# SCH_Full_BMS_2022-05-24.net
KiCad netlist of a schematic drawn in EasyEDA
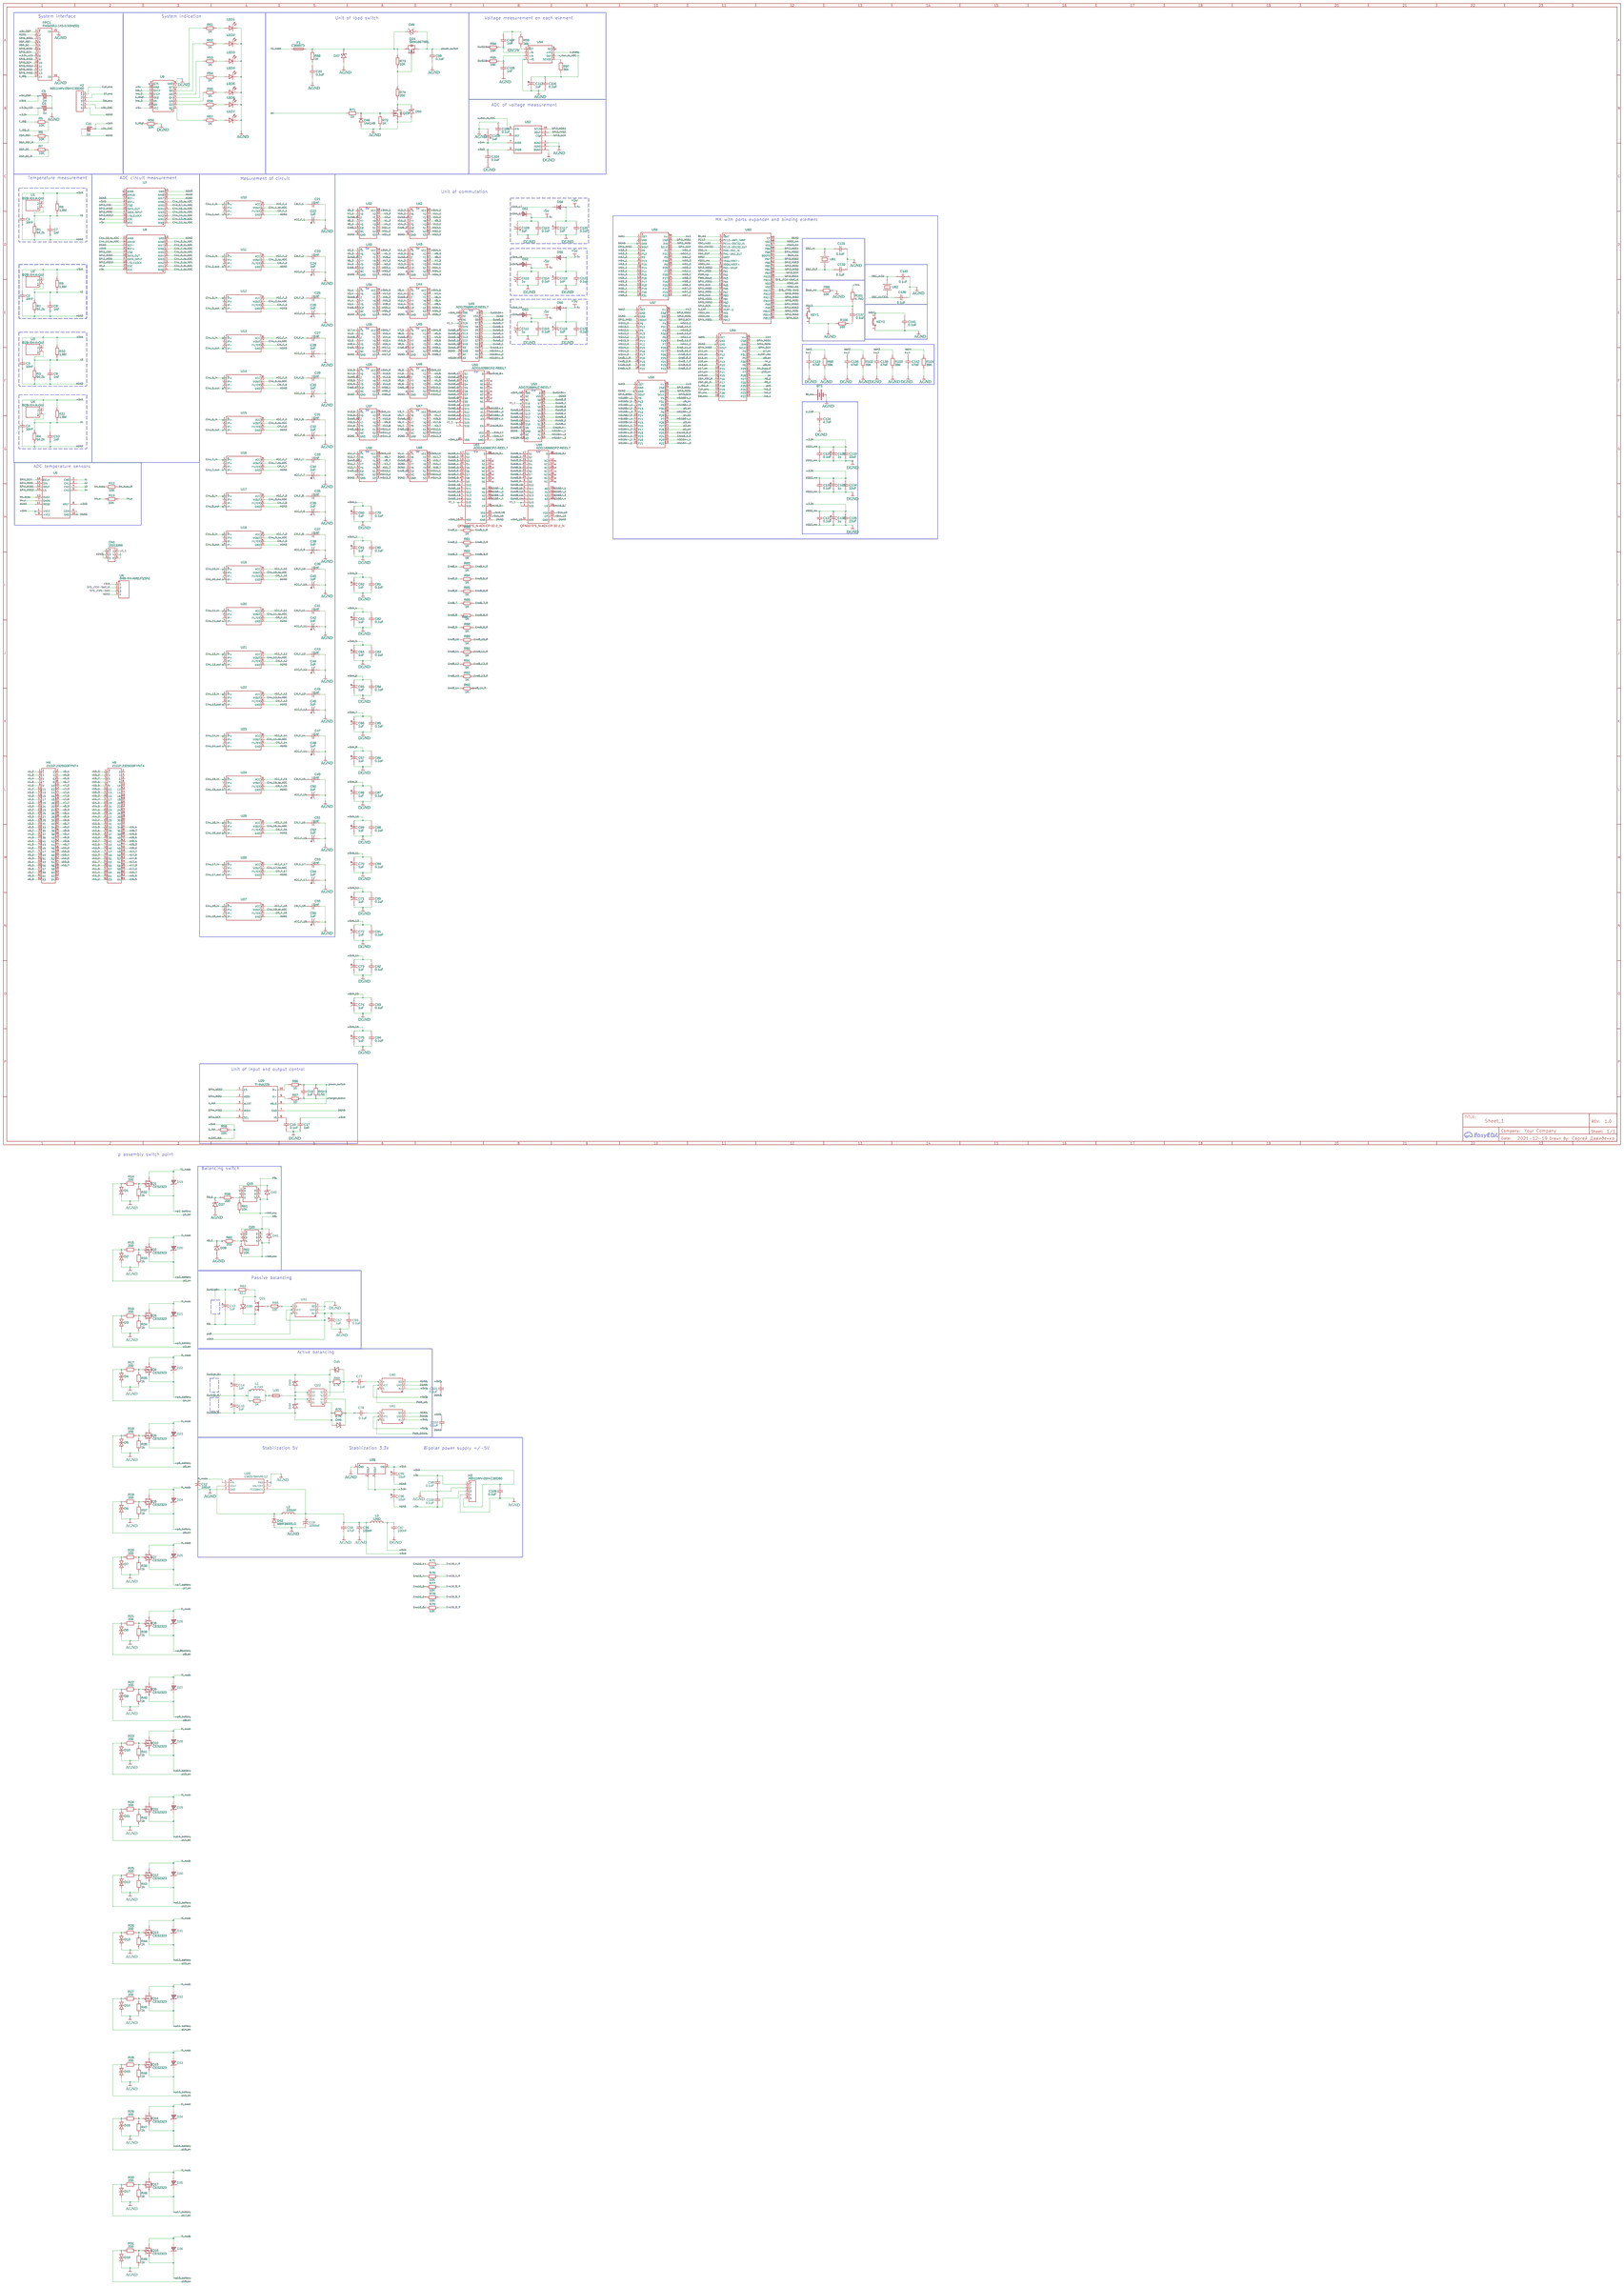
[diagram p0: schematic sheet]

(export (version "E")
  (design (tool "Eeschema 10.0.6"))
  (components
    (comp (ref "BT1")
      (value "1025")
      (fields (field (name "BOM_Supplier Part") "C238060"))
      (libsource (lib "") (part "1025"))
    )
    (comp (ref "C1")
      (value "10nF")
      (fields
        (field (name "BOM_Manufacturer Part") "GRM033R71A103KA01D")
        (field (name "BOM_Supplier Part") "C76941")
      )
      (libsource (lib "") (part "GRM033R71A103KA01D"))
    )
    (comp (ref "C2")
      (value "10nF")
      (fields
        (field (name "BOM_Manufacturer Part") "GRM033R71A103KA01D")
        (field (name "BOM_Supplier Part") "C76941")
      )
      (libsource (lib "") (part "GRM033R71A103KA01D"))
    )
    (comp (ref "C3")
      (value "10nF")
      (fields
        (field (name "BOM_Manufacturer Part") "GRM033R71A103KA01D")
        (field (name "BOM_Supplier Part") "C76941")
      )
      (libsource (lib "") (part "GRM033R71A103KA01D"))
    )
    (comp (ref "C4")
      (value "10nF")
      (fields
        (field (name "BOM_Manufacturer Part") "GRM033R71A103KA01D")
        (field (name "BOM_Supplier Part") "C76941")
      )
      (libsource (lib "") (part "GRM033R71A103KA01D"))
    )
    (comp (ref "C5") (value "1u") (libsource (lib "") (part "C_Tan_SMD_A_EU_1")))
    (comp (ref "C6") (value "1u") (libsource (lib "") (part "C_Tan_SMD_A_EU_2")))
    (comp (ref "C7")
      (value "1nF")
      (fields
        (field (name "BOM_Manufacturer Part") "GRM033R71A103KA01D")
        (field (name "BOM_Supplier Part") "C76941")
      )
      (libsource (lib "") (part "GRM033R71A103KA01D"))
    )
    (comp (ref "C8")
      (value "1nF")
      (fields
        (field (name "BOM_Manufacturer Part") "GRM033R71A103KA01D")
        (field (name "BOM_Supplier Part") "C76941")
      )
      (libsource (lib "") (part "GRM033R71A103KA01D"))
    )
    (comp (ref "C9")
      (value "1nF")
      (fields
        (field (name "BOM_Manufacturer Part") "GRM033R71A103KA01D")
        (field (name "BOM_Supplier Part") "C76941")
      )
      (libsource (lib "") (part "GRM033R71A103KA01D"))
    )
    (comp (ref "C10")
      (value "1nF")
      (fields
        (field (name "BOM_Manufacturer Part") "GRM033R71A103KA01D")
        (field (name "BOM_Supplier Part") "C76941")
      )
      (libsource (lib "") (part "GRM033R71A103KA01D"))
    )
    (comp (ref "C11") (value "1u") (libsource (lib "") (part "C_Tan_SMD_A_EU")))
    (comp (ref "C12")
      (value "100uF")
      (fields
        (field (name "BOM_Manufacturer Part") "HV101M035E077R")
        (field (name "BOM_Supplier Part") "C59934")
      )
      (libsource (lib "") (part "HV101M035E077R"))
    )
    (comp (ref "C13")
      (value "1uF")
      (fields
        (field (name "BOM_Manufacturer Part") "VE-010M1C0405-TRO")
        (field (name "BOM_Supplier Part") "C249445")
      )
      (libsource (lib "") (part "VE-010M1C0405-TRO_4"))
    )
    (comp (ref "C14")
      (value "1uF")
      (fields
        (field (name "BOM_Manufacturer Part") "VE-010M1C0405-TRO")
        (field (name "BOM_Supplier Part") "C249445")
      )
      (libsource (lib "") (part "VE-010M1C0405-TRO_4"))
    )
    (comp (ref "C15")
      (value "1uF")
      (fields
        (field (name "BOM_Manufacturer Part") "VE-010M1C0405-TRO")
        (field (name "BOM_Supplier Part") "C249445")
      )
      (libsource (lib "") (part "VE-010M1C0405-TRO_4"))
    )
    (comp (ref "C16")
      (value "0.1uF")
      (fields
        (field (name "BOM_Manufacturer Part") "0402BB104K160NGT")
        (field (name "BOM_Supplier Part") "C2173076")
      )
      (libsource (lib "") (part "0402BB104K160NGT_1"))
    )
    (comp (ref "C17")
      (value "1uF")
      (fields
        (field (name "BOM_Manufacturer Part") "CL10F105ZP8NNNC")
        (field (name "BOM_Supplier Part") "C84710")
      )
      (libsource (lib "") (part "CL10F105ZP8NNNC"))
    )
    (comp (ref "C18")
      (value "1uF")
      (fields
        (field (name "BOM_Manufacturer Part") "CL10F105ZP8NNNC")
        (field (name "BOM_Supplier Part") "C84710")
      )
      (libsource (lib "") (part "CL10F105ZP8NNNC"))
    )
    (comp (ref "C19")
      (value "1000uF")
      (fields
        (field (name "BOM_Manufacturer Part") "RVT1C102M1010")
        (field (name "BOM_Supplier Part") "C72470")
      )
      (libsource (lib "") (part "RVT1C102M1010"))
    )
    (comp (ref "C20")
      (value "0.1uF")
      (fields
        (field (name "BOM_Manufacturer Part") "0603BB104K500NGT")
        (field (name "BOM_Supplier Part") "C2168571")
      )
      (libsource (lib "") (part "0603BB104K500NGT"))
    )
    (comp (ref "C21")
      (value "1nF")
      (fields
        (field (name "BOM_Manufacturer Part") "0201B102J500CT")
        (field (name "BOM_Supplier Part") "C458605")
      )
      (libsource (lib "") (part "0201B102J500CT"))
    )
    (comp (ref "C22")
      (value "1uF")
      (fields
        (field (name "BOM_Manufacturer Part") "CA45-A-16V-1uF-K")
        (field (name "BOM_Supplier Part") "C140386")
      )
      (libsource (lib "") (part "CA45-A-16V-1UF-K"))
    )
    (comp (ref "C23")
      (value "1nF")
      (fields
        (field (name "BOM_Manufacturer Part") "0201B102J500CT")
        (field (name "BOM_Supplier Part") "C458605")
      )
      (libsource (lib "") (part "0201B102J500CT"))
    )
    (comp (ref "C24")
      (value "1uF")
      (fields
        (field (name "BOM_Manufacturer Part") "CA45-A-16V-1uF-K")
        (field (name "BOM_Supplier Part") "C140386")
      )
      (libsource (lib "") (part "CA45-A-16V-1UF-K_1"))
    )
    (comp (ref "C25")
      (value "1nF")
      (fields
        (field (name "BOM_Manufacturer Part") "0201B102J500CT")
        (field (name "BOM_Supplier Part") "C458605")
      )
      (libsource (lib "") (part "0201B102J500CT"))
    )
    (comp (ref "C26")
      (value "1uF")
      (fields
        (field (name "BOM_Manufacturer Part") "CA45-A-16V-1uF-K")
        (field (name "BOM_Supplier Part") "C140386")
      )
      (libsource (lib "") (part "CA45-A-16V-1UF-K"))
    )
    (comp (ref "C27")
      (value "1nF")
      (fields
        (field (name "BOM_Manufacturer Part") "0201B102J500CT")
        (field (name "BOM_Supplier Part") "C458605")
      )
      (libsource (lib "") (part "0201B102J500CT"))
    )
    (comp (ref "C28")
      (value "1uF")
      (fields
        (field (name "BOM_Manufacturer Part") "CA45-A-16V-1uF-K")
        (field (name "BOM_Supplier Part") "C140386")
      )
      (libsource (lib "") (part "CA45-A-16V-1UF-K"))
    )
    (comp (ref "C29")
      (value "1nF")
      (fields
        (field (name "BOM_Manufacturer Part") "0201B102J500CT")
        (field (name "BOM_Supplier Part") "C458605")
      )
      (libsource (lib "") (part "0201B102J500CT"))
    )
    (comp (ref "C30")
      (value "1uF")
      (fields
        (field (name "BOM_Manufacturer Part") "CA45-A-16V-1uF-K")
        (field (name "BOM_Supplier Part") "C140386")
      )
      (libsource (lib "") (part "CA45-A-16V-1UF-K_1"))
    )
    (comp (ref "C31")
      (value "1nF")
      (fields
        (field (name "BOM_Manufacturer Part") "0201B102J500CT")
        (field (name "BOM_Supplier Part") "C458605")
      )
      (libsource (lib "") (part "0201B102J500CT"))
    )
    (comp (ref "C32")
      (value "1uF")
      (fields
        (field (name "BOM_Manufacturer Part") "CA45-A-16V-1uF-K")
        (field (name "BOM_Supplier Part") "C140386")
      )
      (libsource (lib "") (part "CA45-A-16V-1UF-K_1"))
    )
    (comp (ref "C33")
      (value "1nF")
      (fields
        (field (name "BOM_Manufacturer Part") "0201B102J500CT")
        (field (name "BOM_Supplier Part") "C458605")
      )
      (libsource (lib "") (part "0201B102J500CT"))
    )
    (comp (ref "C34")
      (value "1uF")
      (fields
        (field (name "BOM_Manufacturer Part") "CA45-A-16V-1uF-K")
        (field (name "BOM_Supplier Part") "C140386")
      )
      (libsource (lib "") (part "CA45-A-16V-1UF-K_1"))
    )
    (comp (ref "C35")
      (value "1nF")
      (fields
        (field (name "BOM_Manufacturer Part") "0201B102J500CT")
        (field (name "BOM_Supplier Part") "C458605")
      )
      (libsource (lib "") (part "0201B102J500CT"))
    )
    (comp (ref "C36")
      (value "1uF")
      (fields
        (field (name "BOM_Manufacturer Part") "CA45-A-16V-1uF-K")
        (field (name "BOM_Supplier Part") "C140386")
      )
      (libsource (lib "") (part "CA45-A-16V-1UF-K_1"))
    )
    (comp (ref "C37")
      (value "1nF")
      (fields
        (field (name "BOM_Manufacturer Part") "0201B102J500CT")
        (field (name "BOM_Supplier Part") "C458605")
      )
      (libsource (lib "") (part "0201B102J500CT"))
    )
    (comp (ref "C38")
      (value "1uF")
      (fields
        (field (name "BOM_Manufacturer Part") "CA45-A-16V-1uF-K")
        (field (name "BOM_Supplier Part") "C140386")
      )
      (libsource (lib "") (part "CA45-A-16V-1UF-K_1"))
    )
    (comp (ref "C39")
      (value "1nF")
      (fields
        (field (name "BOM_Manufacturer Part") "0201B102J500CT")
        (field (name "BOM_Supplier Part") "C458605")
      )
      (libsource (lib "") (part "0201B102J500CT"))
    )
    (comp (ref "C40")
      (value "1uF")
      (fields
        (field (name "BOM_Manufacturer Part") "CA45-A-16V-1uF-K")
        (field (name "BOM_Supplier Part") "C140386")
      )
      (libsource (lib "") (part "CA45-A-16V-1UF-K_1"))
    )
    (comp (ref "C41")
      (value "1nF")
      (fields
        (field (name "BOM_Manufacturer Part") "0201B102J500CT")
        (field (name "BOM_Supplier Part") "C458605")
      )
      (libsource (lib "") (part "0201B102J500CT"))
    )
    (comp (ref "C42")
      (value "1uF")
      (fields
        (field (name "BOM_Manufacturer Part") "CA45-A-16V-1uF-K")
        (field (name "BOM_Supplier Part") "C140386")
      )
      (libsource (lib "") (part "CA45-A-16V-1UF-K_1"))
    )
    (comp (ref "C43")
      (value "1nF")
      (fields
        (field (name "BOM_Manufacturer Part") "0201B102J500CT")
        (field (name "BOM_Supplier Part") "C458605")
      )
      (libsource (lib "") (part "0201B102J500CT"))
    )
    (comp (ref "C44")
      (value "1uF")
      (fields
        (field (name "BOM_Manufacturer Part") "CA45-A-16V-1uF-K")
        (field (name "BOM_Supplier Part") "C140386")
      )
      (libsource (lib "") (part "CA45-A-16V-1UF-K"))
    )
    (comp (ref "C45")
      (value "1nF")
      (fields
        (field (name "BOM_Manufacturer Part") "0201B102J500CT")
        (field (name "BOM_Supplier Part") "C458605")
      )
      (libsource (lib "") (part "0201B102J500CT"))
    )
    (comp (ref "C46")
      (value "1uF")
      (fields
        (field (name "BOM_Manufacturer Part") "CA45-A-16V-1uF-K")
        (field (name "BOM_Supplier Part") "C140386")
      )
      (libsource (lib "") (part "CA45-A-16V-1UF-K"))
    )
    (comp (ref "C47")
      (value "1nF")
      (fields
        (field (name "BOM_Manufacturer Part") "0201B102J500CT")
        (field (name "BOM_Supplier Part") "C458605")
      )
      (libsource (lib "") (part "0201B102J500CT"))
    )
    (comp (ref "C48")
      (value "1uF")
      (fields
        (field (name "BOM_Manufacturer Part") "CA45-A-16V-1uF-K")
        (field (name "BOM_Supplier Part") "C140386")
      )
      (libsource (lib "") (part "CA45-A-16V-1UF-K"))
    )
    (comp (ref "C49")
      (value "1nF")
      (fields
        (field (name "BOM_Manufacturer Part") "0201B102J500CT")
        (field (name "BOM_Supplier Part") "C458605")
      )
      (libsource (lib "") (part "0201B102J500CT"))
    )
    (comp (ref "C50")
      (value "1uF")
      (fields
        (field (name "BOM_Manufacturer Part") "CA45-A-16V-1uF-K")
        (field (name "BOM_Supplier Part") "C140386")
      )
      (libsource (lib "") (part "CA45-A-16V-1UF-K"))
    )
    (comp (ref "C51")
      (value "1nF")
      (fields
        (field (name "BOM_Manufacturer Part") "0201B102J500CT")
        (field (name "BOM_Supplier Part") "C458605")
      )
      (libsource (lib "") (part "0201B102J500CT"))
    )
    (comp (ref "C52")
      (value "1uF")
      (fields
        (field (name "BOM_Manufacturer Part") "CA45-A-16V-1uF-K")
        (field (name "BOM_Supplier Part") "C140386")
      )
      (libsource (lib "") (part "CA45-A-16V-1UF-K"))
    )
    (comp (ref "C53")
      (value "1nF")
      (fields
        (field (name "BOM_Manufacturer Part") "0201B102J500CT")
        (field (name "BOM_Supplier Part") "C458605")
      )
      (libsource (lib "") (part "0201B102J500CT"))
    )
    (comp (ref "C54")
      (value "1uF")
      (fields
        (field (name "BOM_Manufacturer Part") "CA45-A-16V-1uF-K")
        (field (name "BOM_Supplier Part") "C140386")
      )
      (libsource (lib "") (part "CA45-A-16V-1UF-K"))
    )
    (comp (ref "C55")
      (value "1nF")
      (fields
        (field (name "BOM_Manufacturer Part") "0201B102J500CT")
        (field (name "BOM_Supplier Part") "C458605")
      )
      (libsource (lib "") (part "0201B102J500CT"))
    )
    (comp (ref "C56")
      (value "1uF")
      (fields
        (field (name "BOM_Manufacturer Part") "CA45-A-16V-1uF-K")
        (field (name "BOM_Supplier Part") "C140386")
      )
      (libsource (lib "") (part "CA45-A-16V-1UF-K"))
    )
    (comp (ref "C57")
      (value "1uF")
      (fields
        (field (name "BOM_Manufacturer Part") "VE-010M1C0405-TRO")
        (field (name "BOM_Supplier Part") "C249445")
      )
      (libsource (lib "") (part "VE-010M1C0405-TRO_4"))
    )
    (comp (ref "C58")
      (value "47uF")
      (fields
        (field (name "BOM_Manufacturer Part") "0805X476M6R3")
        (field (name "BOM_Supplier Part") "C98821")
      )
      (libsource (lib "") (part "0805X476M6R3"))
    )
    (comp (ref "C59")
      (value "0.1uF")
      (fields
        (field (name "BOM_Manufacturer Part") "0402BB104K160NGT")
        (field (name "BOM_Supplier Part") "C2173076")
      )
      (libsource (lib "") (part "0402BB104K160NGT_1"))
    )
    (comp (ref "C60")
      (value "1uF")
      (fields
        (field (name "BOM_Manufacturer Part") "VE-010M1C0405-TRO")
        (field (name "BOM_Supplier Part") "C249445")
      )
      (libsource (lib "") (part "VE-010M1C0405-TRO_3"))
    )
    (comp (ref "C61")
      (value "1uF")
      (fields
        (field (name "BOM_Manufacturer Part") "VE-010M1C0405-TRO")
        (field (name "BOM_Supplier Part") "C249445")
      )
      (libsource (lib "") (part "VE-010M1C0405-TRO_3"))
    )
    (comp (ref "C62")
      (value "1uF")
      (fields
        (field (name "BOM_Manufacturer Part") "VE-010M1C0405-TRO")
        (field (name "BOM_Supplier Part") "C249445")
      )
      (libsource (lib "") (part "VE-010M1C0405-TRO_3"))
    )
    (comp (ref "C63")
      (value "1uF")
      (fields
        (field (name "BOM_Manufacturer Part") "VE-010M1C0405-TRO")
        (field (name "BOM_Supplier Part") "C249445")
      )
      (libsource (lib "") (part "VE-010M1C0405-TRO_3"))
    )
    (comp (ref "C64")
      (value "1uF")
      (fields
        (field (name "BOM_Manufacturer Part") "VE-010M1C0405-TRO")
        (field (name "BOM_Supplier Part") "C249445")
      )
      (libsource (lib "") (part "VE-010M1C0405-TRO"))
    )
    (comp (ref "C65")
      (value "1uF")
      (fields
        (field (name "BOM_Manufacturer Part") "VE-010M1C0405-TRO")
        (field (name "BOM_Supplier Part") "C249445")
      )
      (libsource (lib "") (part "VE-010M1C0405-TRO"))
    )
    (comp (ref "C66")
      (value "1uF")
      (fields
        (field (name "BOM_Manufacturer Part") "VE-010M1C0405-TRO")
        (field (name "BOM_Supplier Part") "C249445")
      )
      (libsource (lib "") (part "VE-010M1C0405-TRO"))
    )
    (comp (ref "C67")
      (value "1uF")
      (fields
        (field (name "BOM_Manufacturer Part") "VE-010M1C0405-TRO")
        (field (name "BOM_Supplier Part") "C249445")
      )
      (libsource (lib "") (part "VE-010M1C0405-TRO"))
    )
    (comp (ref "C68")
      (value "1uF")
      (fields
        (field (name "BOM_Manufacturer Part") "VE-010M1C0405-TRO")
        (field (name "BOM_Supplier Part") "C249445")
      )
      (libsource (lib "") (part "VE-010M1C0405-TRO"))
    )
    (comp (ref "C69")
      (value "1uF")
      (fields
        (field (name "BOM_Manufacturer Part") "VE-010M1C0405-TRO")
        (field (name "BOM_Supplier Part") "C249445")
      )
      (libsource (lib "") (part "VE-010M1C0405-TRO"))
    )
    (comp (ref "C70")
      (value "1uF")
      (fields
        (field (name "BOM_Manufacturer Part") "VE-010M1C0405-TRO")
        (field (name "BOM_Supplier Part") "C249445")
      )
      (libsource (lib "") (part "VE-010M1C0405-TRO"))
    )
    (comp (ref "C71")
      (value "1uF")
      (fields
        (field (name "BOM_Manufacturer Part") "VE-010M1C0405-TRO")
        (field (name "BOM_Supplier Part") "C249445")
      )
      (libsource (lib "") (part "VE-010M1C0405-TRO"))
    )
    (comp (ref "C72")
      (value "1uF")
      (fields
        (field (name "BOM_Manufacturer Part") "VE-010M1C0405-TRO")
        (field (name "BOM_Supplier Part") "C249445")
      )
      (libsource (lib "") (part "VE-010M1C0405-TRO"))
    )
    (comp (ref "C73")
      (value "1uF")
      (fields
        (field (name "BOM_Manufacturer Part") "VE-010M1C0405-TRO")
        (field (name "BOM_Supplier Part") "C249445")
      )
      (libsource (lib "") (part "VE-010M1C0405-TRO"))
    )
    (comp (ref "C74")
      (value "1uF")
      (fields
        (field (name "BOM_Manufacturer Part") "VE-010M1C0405-TRO")
        (field (name "BOM_Supplier Part") "C249445")
      )
      (libsource (lib "") (part "VE-010M1C0405-TRO"))
    )
    (comp (ref "C75")
      (value "1uF")
      (fields
        (field (name "BOM_Manufacturer Part") "VE-010M1C0405-TRO")
        (field (name "BOM_Supplier Part") "C249445")
      )
      (libsource (lib "") (part "VE-010M1C0405-TRO"))
    )
    (comp (ref "C76")
      (value "100nF")
      (fields
        (field (name "BOM_Manufacturer Part") "C0201X6S104K6R3NTA")
        (field (name "BOM_Supplier Part") "C357757")
      )
      (libsource (lib "") (part "C0201X6S104K6R3NTA"))
    )
    (comp (ref "C77")
      (value "0.1uF")
      (fields
        (field (name "BOM_Manufacturer Part") "0402BB104K160NGT")
        (field (name "BOM_Supplier Part") "C2173076")
      )
      (libsource (lib "") (part "0402BB104K160NGT_2"))
    )
    (comp (ref "C78")
      (value "0.1uF")
      (fields
        (field (name "BOM_Manufacturer Part") "0402BB104K160NGT")
        (field (name "BOM_Supplier Part") "C2173076")
      )
      (libsource (lib "") (part "0402BB104K160NGT_2"))
    )
    (comp (ref "C79")
      (value "0.1uF")
      (fields
        (field (name "BOM_Manufacturer Part") "0402BB104K160NGT")
        (field (name "BOM_Supplier Part") "C2173076")
      )
      (libsource (lib "") (part "0402BB104K160NGT_1"))
    )
    (comp (ref "C80")
      (value "0.1uF")
      (fields
        (field (name "BOM_Manufacturer Part") "0402BB104K160NGT")
        (field (name "BOM_Supplier Part") "C2173076")
      )
      (libsource (lib "") (part "0402BB104K160NGT_1"))
    )
    (comp (ref "C81")
      (value "0.1uF")
      (fields
        (field (name "BOM_Manufacturer Part") "0402BB104K160NGT")
        (field (name "BOM_Supplier Part") "C2173076")
      )
      (libsource (lib "") (part "0402BB104K160NGT_1"))
    )
    (comp (ref "C82")
      (value "0.1uF")
      (fields
        (field (name "BOM_Manufacturer Part") "0402BB104K160NGT")
        (field (name "BOM_Supplier Part") "C2173076")
      )
      (libsource (lib "") (part "0402BB104K160NGT_1"))
    )
    (comp (ref "C83")
      (value "0.1uF")
      (fields
        (field (name "BOM_Manufacturer Part") "0402BB104K160NGT")
        (field (name "BOM_Supplier Part") "C2173076")
      )
      (libsource (lib "") (part "0402BB104K160NGT_1"))
    )
    (comp (ref "C84")
      (value "0.1uF")
      (fields
        (field (name "BOM_Manufacturer Part") "0402BB104K160NGT")
        (field (name "BOM_Supplier Part") "C2173076")
      )
      (libsource (lib "") (part "0402BB104K160NGT_1"))
    )
    (comp (ref "C85")
      (value "0.1uF")
      (fields
        (field (name "BOM_Manufacturer Part") "0402BB104K160NGT")
        (field (name "BOM_Supplier Part") "C2173076")
      )
      (libsource (lib "") (part "0402BB104K160NGT_1"))
    )
    (comp (ref "C86")
      (value "0.1uF")
      (fields
        (field (name "BOM_Manufacturer Part") "0402BB104K160NGT")
        (field (name "BOM_Supplier Part") "C2173076")
      )
      (libsource (lib "") (part "0402BB104K160NGT_1"))
    )
    (comp (ref "C87")
      (value "0.1uF")
      (fields
        (field (name "BOM_Manufacturer Part") "0402BB104K160NGT")
        (field (name "BOM_Supplier Part") "C2173076")
      )
      (libsource (lib "") (part "0402BB104K160NGT_1"))
    )
    (comp (ref "C88")
      (value "0.1uF")
      (fields
        (field (name "BOM_Manufacturer Part") "0402BB104K160NGT")
        (field (name "BOM_Supplier Part") "C2173076")
      )
      (libsource (lib "") (part "0402BB104K160NGT_1"))
    )
    (comp (ref "C89")
      (value "0.1uF")
      (fields
        (field (name "BOM_Manufacturer Part") "0402BB104K160NGT")
        (field (name "BOM_Supplier Part") "C2173076")
      )
      (libsource (lib "") (part "0402BB104K160NGT_1"))
    )
    (comp (ref "C90")
      (value "0.1uF")
      (fields
        (field (name "BOM_Manufacturer Part") "0402BB104K160NGT")
        (field (name "BOM_Supplier Part") "C2173076")
      )
      (libsource (lib "") (part "0402BB104K160NGT_1"))
    )
    (comp (ref "C91")
      (value "0.1uF")
      (fields
        (field (name "BOM_Manufacturer Part") "0402BB104K160NGT")
        (field (name "BOM_Supplier Part") "C2173076")
      )
      (libsource (lib "") (part "0402BB104K160NGT_1"))
    )
    (comp (ref "C92")
      (value "0.1uF")
      (fields
        (field (name "BOM_Manufacturer Part") "0402BB104K160NGT")
        (field (name "BOM_Supplier Part") "C2173076")
      )
      (libsource (lib "") (part "0402BB104K160NGT_1"))
    )
    (comp (ref "C93")
      (value "0.1uF")
      (fields
        (field (name "BOM_Manufacturer Part") "0402BB104K160NGT")
        (field (name "BOM_Supplier Part") "C2173076")
      )
      (libsource (lib "") (part "0402BB104K160NGT_1"))
    )
    (comp (ref "C94")
      (value "0.1uF")
      (fields
        (field (name "BOM_Manufacturer Part") "0402BB104K160NGT")
        (field (name "BOM_Supplier Part") "C2173076")
      )
      (libsource (lib "") (part "0402BB104K160NGT_1"))
    )
    (comp (ref "C95")
      (value "10uF")
      (fields
        (field (name "BOM_Manufacturer Part") "VE-100M0J0305-TRO")
        (field (name "BOM_Supplier Part") "C249448")
      )
      (libsource (lib "") (part "VE-100M0J0305-TRO"))
    )
    (comp (ref "C96")
      (value "10uF")
      (fields
        (field (name "BOM_Manufacturer Part") "VE-100M0J0305-TRO")
        (field (name "BOM_Supplier Part") "C249448")
      )
      (libsource (lib "") (part "VE-100M0J0305-TRO"))
    )
    (comp (ref "C97")
      (value "100nF")
      (fields
        (field (name "BOM_Manufacturer Part") "C0201X6S104K6R3NTA")
        (field (name "BOM_Supplier Part") "C357757")
      )
      (libsource (lib "") (part "C0201X6S104K6R3NTA"))
    )
    (comp (ref "C98")
      (value "0.1uF")
      (fields
        (field (name "BOM_Manufacturer Part") "0603BB104K500NGT")
        (field (name "BOM_Supplier Part") "C2168571")
      )
      (libsource (lib "") (part "0603BB104K500NGT"))
    )
    (comp (ref "C99")
      (value "0.1uF")
      (fields
        (field (name "BOM_Manufacturer Part") "0402BB104K160NGT")
        (field (name "BOM_Supplier Part") "C2173076")
      )
      (libsource (lib "") (part "0402BB104K160NGT_3"))
    )
    (comp (ref "C100")
      (value "0.1uF")
      (fields
        (field (name "BOM_Manufacturer Part") "0402BB104K160NGT")
        (field (name "BOM_Supplier Part") "C2173076")
      )
      (libsource (lib "") (part "0402BB104K160NGT_3"))
    )
    (comp (ref "C101")
      (value "0.1uF")
      (fields
        (field (name "BOM_Manufacturer Part") "0402BB104K160NGT")
        (field (name "BOM_Supplier Part") "C2173076")
      )
      (libsource (lib "") (part "0402BB104K160NGT_3"))
    )
    (comp (ref "C102")
      (value "0.1uF")
      (fields
        (field (name "BOM_Manufacturer Part") "0402BB104K160NGT")
        (field (name "BOM_Supplier Part") "C2173076")
      )
      (libsource (lib "") (part "0402BB104K160NGT_3"))
    )
    (comp (ref "C103")
      (value "1uF")
      (fields
        (field (name "BOM_Manufacturer Part") "VE-010M1C0405-TRO")
        (field (name "BOM_Supplier Part") "C249445")
      )
      (libsource (lib "") (part "VE-010M1C0405-TRO_5"))
    )
    (comp (ref "C104")
      (value "0.1uF")
      (fields
        (field (name "BOM_Manufacturer Part") "0402BB104K160NGT")
        (field (name "BOM_Supplier Part") "C2173076")
      )
      (libsource (lib "") (part "0402BB104K160NGT_1"))
    )
    (comp (ref "C105")
      (value "0.1uF")
      (fields
        (field (name "BOM_Manufacturer Part") "0402BB104K160NGT")
        (field (name "BOM_Supplier Part") "C2173076")
      )
      (libsource (lib "") (part "0402BB104K160NGT_1"))
    )
    (comp (ref "C106")
      (value "0.1uF")
      (fields
        (field (name "BOM_Manufacturer Part") "0402BB104K160NGT")
        (field (name "BOM_Supplier Part") "C2173076")
      )
      (libsource (lib "") (part "0402BB104K160NGT_3"))
    )
    (comp (ref "C107")
      (value "1nF")
      (fields
        (field (name "BOM_Manufacturer Part") "0201B102J500CT")
        (field (name "BOM_Supplier Part") "C458605")
      )
      (libsource (lib "") (part "0201B102J500CT_1"))
    )
    (comp (ref "C108")
      (value "1nF")
      (fields
        (field (name "BOM_Manufacturer Part") "0201B102J500CT")
        (field (name "BOM_Supplier Part") "C458605")
      )
      (libsource (lib "") (part "0201B102J500CT_1"))
    )
    (comp (ref "C109")
      (value "1uF")
      (fields
        (field (name "BOM_Manufacturer Part") "VE-010M1C0405-TRO")
        (field (name "BOM_Supplier Part") "C249445")
      )
      (libsource (lib "") (part "VE-010M1C0405-TRO_6"))
    )
    (comp (ref "C110") (value "1u") (libsource (lib "") (part "C_Tan_SMD_A_US")))
    (comp (ref "C111") (value "1u") (libsource (lib "") (part "C_Tan_SMD_A_US")))
    (comp (ref "C112")
      (value "1uF")
      (fields
        (field (name "BOM_Manufacturer Part") "VE-010M1C0405-TRO")
        (field (name "BOM_Supplier Part") "C249445")
      )
      (libsource (lib "") (part "VE-010M1C0405-TRO_1"))
    )
    (comp (ref "C113")
      (value "0.1uF")
      (fields
        (field (name "BOM_Manufacturer Part") "0402BB104K160NGT")
        (field (name "BOM_Supplier Part") "C2173076")
      )
      (libsource (lib "") (part "0402BB104K160NGT_1"))
    )
    (comp (ref "C114")
      (value "0.1uF")
      (fields
        (field (name "BOM_Manufacturer Part") "0402BB104K160NGT")
        (field (name "BOM_Supplier Part") "C2173076")
      )
      (libsource (lib "") (part "0402BB104K160NGT_1"))
    )
    (comp (ref "C115")
      (value "0.1uF")
      (fields
        (field (name "BOM_Manufacturer Part") "0402BB104K160NGT")
        (field (name "BOM_Supplier Part") "C2173076")
      )
      (libsource (lib "") (part "0402BB104K160NGT_1"))
    )
    (comp (ref "C116")
      (value "0.1uF")
      (fields
        (field (name "BOM_Manufacturer Part") "0402BB104K160NGT")
        (field (name "BOM_Supplier Part") "C2173076")
      )
      (libsource (lib "") (part "0402BB104K160NGT_1"))
    )
    (comp (ref "C117")
      (value "1uF")
      (fields
        (field (name "BOM_Manufacturer Part") "VE-010M1C0405-TRO")
        (field (name "BOM_Supplier Part") "C249445")
      )
      (libsource (lib "") (part "VE-010M1C0405-TRO_2"))
    )
    (comp (ref "C118")
      (value "1uF")
      (fields
        (field (name "BOM_Manufacturer Part") "VE-010M1C0405-TRO")
        (field (name "BOM_Supplier Part") "C249445")
      )
      (libsource (lib "") (part "VE-010M1C0405-TRO_1"))
    )
    (comp (ref "C119")
      (value "1uF")
      (fields
        (field (name "BOM_Manufacturer Part") "VE-010M1C0405-TRO")
        (field (name "BOM_Supplier Part") "C249445")
      )
      (libsource (lib "") (part "VE-010M1C0405-TRO_2"))
    )
    (comp (ref "C120")
      (value "0.1uF")
      (fields
        (field (name "BOM_Manufacturer Part") "0402BB104K160NGT")
        (field (name "BOM_Supplier Part") "C2173076")
      )
      (libsource (lib "") (part "0402BB104K160NGT_1"))
    )
    (comp (ref "C121")
      (value "0.1uF")
      (fields
        (field (name "BOM_Manufacturer Part") "0402BB104K160NGT")
        (field (name "BOM_Supplier Part") "C2173076")
      )
      (libsource (lib "") (part "0402BB104K160NGT_1"))
    )
    (comp (ref "C122")
      (value "0.1uF")
      (fields
        (field (name "BOM_Manufacturer Part") "0402BB104K160NGT")
        (field (name "BOM_Supplier Part") "C2173076")
      )
      (libsource (lib "") (part "0402BB104K160NGT_1"))
    )
    (comp (ref "C123")
      (value "47nF")
      (fields
        (field (name "BOM_Manufacturer Part") "GRT033R60J473KE01D")
        (field (name "BOM_Supplier Part") "C126621")
      )
      (libsource (lib "") (part "GRT033R60J473KE01D"))
    )
    (comp (ref "C124")
      (value "4.7nF")
      (fields
        (field (name "BOM_Manufacturer Part") "CC0201KRX7R5BB472")
        (field (name "BOM_Supplier Part") "C526949")
      )
      (libsource (lib "") (part "CC0201KRX7R5BB472"))
    )
    (comp (ref "C125")
      (value "0.1uF")
      (fields
        (field (name "BOM_Manufacturer Part") "0402BB104K160NGT")
        (field (name "BOM_Supplier Part") "C2173076")
      )
      (libsource (lib "") (part "0402BB104K160NGT_1"))
    )
    (comp (ref "C126")
      (value "0.1uF")
      (fields
        (field (name "BOM_Manufacturer Part") "0402BB104K160NGT")
        (field (name "BOM_Supplier Part") "C2173076")
      )
      (libsource (lib "") (part "0402BB104K160NGT_1"))
    )
    (comp (ref "C127")
      (value "0.1uF")
      (fields
        (field (name "BOM_Manufacturer Part") "0402BB104K160NGT")
        (field (name "BOM_Supplier Part") "C2173076")
      )
      (libsource (lib "") (part "0402BB104K160NGT_1"))
    )
    (comp (ref "C128")
      (value "1u")
      (fields
        (field (name "BOM_Manufacturer Part") "16SVP180MX")
        (field (name "BOM_Supplier Part") "C236288")
      )
      (libsource (lib "") (part "16SVP180MX"))
    )
    (comp (ref "C129")
      (value "1u")
      (fields
        (field (name "BOM_Manufacturer Part") "16SVP180MX")
        (field (name "BOM_Supplier Part") "C236288")
      )
      (libsource (lib "") (part "16SVP180MX"))
    )
    (comp (ref "C130")
      (value "1u")
      (fields
        (field (name "BOM_Manufacturer Part") "16SVP180MX")
        (field (name "BOM_Supplier Part") "C236288")
      )
      (libsource (lib "") (part "16SVP180MX"))
    )
    (comp (ref "C131")
      (value "0.1uF")
      (fields
        (field (name "BOM_Manufacturer Part") "0402BB104K160NGT")
        (field (name "BOM_Supplier Part") "C2173076")
      )
      (libsource (lib "") (part "0402BB104K160NGT"))
    )
    (comp (ref "C132")
      (value "0.1uF")
      (fields
        (field (name "BOM_Manufacturer Part") "0402BB104K160NGT")
        (field (name "BOM_Supplier Part") "C2173076")
      )
      (libsource (lib "") (part "0402BB104K160NGT"))
    )
    (comp (ref "C133")
      (value "22uF")
      (fields
        (field (name "BOM_Manufacturer Part") "GRM188B30J226MEA0D")
        (field (name "BOM_Supplier Part") "C15500")
      )
      (libsource (lib "") (part "GRM188B30J226MEA0D"))
    )
    (comp (ref "C134")
      (value "22uF")
      (fields
        (field (name "BOM_Manufacturer Part") "GRM188B30J226MEA0D")
        (field (name "BOM_Supplier Part") "C15500")
      )
      (libsource (lib "") (part "GRM188B30J226MEA0D"))
    )
    (comp (ref "C135")
      (value "22uF")
      (fields
        (field (name "BOM_Manufacturer Part") "GRM188B30J226MEA0D")
        (field (name "BOM_Supplier Part") "C15500")
      )
      (libsource (lib "") (part "GRM188B30J226MEA0D"))
    )
    (comp (ref "C136")
      (value "47nF")
      (fields
        (field (name "BOM_Manufacturer Part") "GRT033R60J473KE01D")
        (field (name "BOM_Supplier Part") "C126621")
      )
      (libsource (lib "") (part "GRT033R60J473KE01D"))
    )
    (comp (ref "C137")
      (value "0.1uF")
      (fields
        (field (name "BOM_Manufacturer Part") "0402BB104K160NGT")
        (field (name "BOM_Supplier Part") "C2173076")
      )
      (libsource (lib "") (part "0402BB104K160NGT_1"))
    )
    (comp (ref "C138")
      (value "47nF")
      (fields
        (field (name "BOM_Manufacturer Part") "GRT033R60J473KE01D")
        (field (name "BOM_Supplier Part") "C126621")
      )
      (libsource (lib "") (part "GRT033R60J473KE01D"))
    )
    (comp (ref "C139")
      (value "0.1uF")
      (fields
        (field (name "BOM_Manufacturer Part") "0402BB104K160NGT")
        (field (name "BOM_Supplier Part") "C2173076")
      )
      (libsource (lib "") (part "0402BB104K160NGT"))
    )
    (comp (ref "C140")
      (value "0.1uF")
      (fields
        (field (name "BOM_Manufacturer Part") "0402BB104K160NGT")
        (field (name "BOM_Supplier Part") "C2173076")
      )
      (libsource (lib "") (part "0402BB104K160NGT"))
    )
    (comp (ref "C141")
      (value "0.1uF")
      (fields
        (field (name "BOM_Manufacturer Part") "0402BB104K160NGT")
        (field (name "BOM_Supplier Part") "C2173076")
      )
      (libsource (lib "") (part "0402BB104K160NGT_1"))
    )
    (comp (ref "C142")
      (value "47nF")
      (fields
        (field (name "BOM_Manufacturer Part") "GRT033R60J473KE01D")
        (field (name "BOM_Supplier Part") "C126621")
      )
      (libsource (lib "") (part "GRT033R60J473KE01D"))
    )
    (comp (ref "CN1")
      (value "15311066")
      (fields (field (name "BOM_Supplier Part") "C585772"))
      (libsource (lib "") (part "15311066"))
    )
    (comp (ref "D1")
      (value "UCLAMP0541Z.TFT")
      (fields (field (name "BOM_Supplier Part") "C193630"))
      (libsource (lib "") (part "UCLAMP0541Z.TFT"))
    )
    (comp (ref "D2")
      (value "UCLAMP0541Z.TFT")
      (fields (field (name "BOM_Supplier Part") "C193630"))
      (libsource (lib "") (part "UCLAMP0541Z.TFT"))
    )
    (comp (ref "D3")
      (value "UCLAMP0541Z.TFT")
      (fields (field (name "BOM_Supplier Part") "C193630"))
      (libsource (lib "") (part "UCLAMP0541Z.TFT"))
    )
    (comp (ref "D4")
      (value "UCLAMP0541Z.TFT")
      (fields (field (name "BOM_Supplier Part") "C193630"))
      (libsource (lib "") (part "UCLAMP0541Z.TFT"))
    )
    (comp (ref "D5")
      (value "UCLAMP0541Z.TFT")
      (fields (field (name "BOM_Supplier Part") "C193630"))
      (libsource (lib "") (part "UCLAMP0541Z.TFT"))
    )
    (comp (ref "D6")
      (value "UCLAMP0541Z.TFT")
      (fields (field (name "BOM_Supplier Part") "C193630"))
      (libsource (lib "") (part "UCLAMP0541Z.TFT"))
    )
    (comp (ref "D7")
      (value "UCLAMP0541Z.TFT")
      (fields (field (name "BOM_Supplier Part") "C193630"))
      (libsource (lib "") (part "UCLAMP0541Z.TFT"))
    )
    (comp (ref "D8")
      (value "UCLAMP0541Z.TFT")
      (fields (field (name "BOM_Supplier Part") "C193630"))
      (libsource (lib "") (part "UCLAMP0541Z.TFT"))
    )
    (comp (ref "D9")
      (value "UCLAMP0541Z.TFT")
      (fields (field (name "BOM_Supplier Part") "C193630"))
      (libsource (lib "") (part "UCLAMP0541Z.TFT"))
    )
    (comp (ref "D10")
      (value "UCLAMP0541Z.TFT")
      (fields (field (name "BOM_Supplier Part") "C193630"))
      (libsource (lib "") (part "UCLAMP0541Z.TFT"))
    )
    (comp (ref "D11")
      (value "UCLAMP0541Z.TFT")
      (fields (field (name "BOM_Supplier Part") "C193630"))
      (libsource (lib "") (part "UCLAMP0541Z.TFT"))
    )
    (comp (ref "D12")
      (value "UCLAMP0541Z.TFT")
      (fields (field (name "BOM_Supplier Part") "C193630"))
      (libsource (lib "") (part "UCLAMP0541Z.TFT"))
    )
    (comp (ref "D13")
      (value "UCLAMP0541Z.TFT")
      (fields (field (name "BOM_Supplier Part") "C193630"))
      (libsource (lib "") (part "UCLAMP0541Z.TFT"))
    )
    (comp (ref "D14")
      (value "UCLAMP0541Z.TFT")
      (fields (field (name "BOM_Supplier Part") "C193630"))
      (libsource (lib "") (part "UCLAMP0541Z.TFT"))
    )
    (comp (ref "D15")
      (value "UCLAMP0541Z.TFT")
      (fields (field (name "BOM_Supplier Part") "C193630"))
      (libsource (lib "") (part "UCLAMP0541Z.TFT"))
    )
    (comp (ref "D16")
      (value "UCLAMP0541Z.TFT")
      (fields (field (name "BOM_Supplier Part") "C193630"))
      (libsource (lib "") (part "UCLAMP0541Z.TFT"))
    )
    (comp (ref "D17")
      (value "UCLAMP0541Z.TFT")
      (fields (field (name "BOM_Supplier Part") "C193630"))
      (libsource (lib "") (part "UCLAMP0541Z.TFT"))
    )
    (comp (ref "D18")
      (value "UCLAMP0541Z.TFT")
      (fields (field (name "BOM_Supplier Part") "C193630"))
      (libsource (lib "") (part "UCLAMP0541Z.TFT"))
    )
    (comp (ref "D19")
      (value "1.0SMBJ30A")
      (fields
        (field (name "BOM_Manufacturer Part") "1.0SMBJ20A")
        (field (name "BOM_Supplier Part") "C501367")
      )
      (libsource (lib "") (part "1.0SMBJ20A"))
    )
    (comp (ref "D20")
      (value "1.0SMBJ30A")
      (fields
        (field (name "BOM_Manufacturer Part") "1.0SMBJ20A")
        (field (name "BOM_Supplier Part") "C501367")
      )
      (libsource (lib "") (part "1.0SMBJ20A"))
    )
    (comp (ref "D21")
      (value "1.0SMBJ30A")
      (fields
        (field (name "BOM_Manufacturer Part") "1.0SMBJ20A")
        (field (name "BOM_Supplier Part") "C501367")
      )
      (libsource (lib "") (part "1.0SMBJ20A"))
    )
    (comp (ref "D22")
      (value "1.0SMBJ30A")
      (fields
        (field (name "BOM_Manufacturer Part") "1.0SMBJ20A")
        (field (name "BOM_Supplier Part") "C501367")
      )
      (libsource (lib "") (part "1.0SMBJ20A"))
    )
    (comp (ref "D23")
      (value "1.0SMBJ30A")
      (fields
        (field (name "BOM_Manufacturer Part") "1.0SMBJ20A")
        (field (name "BOM_Supplier Part") "C501367")
      )
      (libsource (lib "") (part "1.0SMBJ20A"))
    )
    (comp (ref "D24")
      (value "1.0SMBJ30A")
      (fields
        (field (name "BOM_Manufacturer Part") "1.0SMBJ20A")
        (field (name "BOM_Supplier Part") "C501367")
      )
      (libsource (lib "") (part "1.0SMBJ20A"))
    )
    (comp (ref "D25")
      (value "1.0SMBJ30A")
      (fields
        (field (name "BOM_Manufacturer Part") "1.0SMBJ20A")
        (field (name "BOM_Supplier Part") "C501367")
      )
      (libsource (lib "") (part "1.0SMBJ20A"))
    )
    (comp (ref "D26")
      (value "1.0SMBJ30A")
      (fields
        (field (name "BOM_Manufacturer Part") "1.0SMBJ20A")
        (field (name "BOM_Supplier Part") "C501367")
      )
      (libsource (lib "") (part "1.0SMBJ20A"))
    )
    (comp (ref "D27")
      (value "1.0SMBJ30A")
      (fields
        (field (name "BOM_Manufacturer Part") "1.0SMBJ20A")
        (field (name "BOM_Supplier Part") "C501367")
      )
      (libsource (lib "") (part "1.0SMBJ20A"))
    )
    (comp (ref "D28")
      (value "1.0SMBJ30A")
      (fields
        (field (name "BOM_Manufacturer Part") "1.0SMBJ20A")
        (field (name "BOM_Supplier Part") "C501367")
      )
      (libsource (lib "") (part "1.0SMBJ20A"))
    )
    (comp (ref "D29")
      (value "1.0SMBJ30A")
      (fields
        (field (name "BOM_Manufacturer Part") "1.0SMBJ20A")
        (field (name "BOM_Supplier Part") "C501367")
      )
      (libsource (lib "") (part "1.0SMBJ20A"))
    )
    (comp (ref "D30")
      (value "1.0SMBJ30A")
      (fields
        (field (name "BOM_Manufacturer Part") "1.0SMBJ20A")
        (field (name "BOM_Supplier Part") "C501367")
      )
      (libsource (lib "") (part "1.0SMBJ20A"))
    )
    (comp (ref "D31")
      (value "1.0SMBJ30A")
      (fields
        (field (name "BOM_Manufacturer Part") "1.0SMBJ20A")
        (field (name "BOM_Supplier Part") "C501367")
      )
      (libsource (lib "") (part "1.0SMBJ20A"))
    )
    (comp (ref "D32")
      (value "1.0SMBJ30A")
      (fields
        (field (name "BOM_Manufacturer Part") "1.0SMBJ20A")
        (field (name "BOM_Supplier Part") "C501367")
      )
      (libsource (lib "") (part "1.0SMBJ20A"))
    )
    (comp (ref "D33")
      (value "1.0SMBJ30A")
      (fields
        (field (name "BOM_Manufacturer Part") "1.0SMBJ20A")
        (field (name "BOM_Supplier Part") "C501367")
      )
      (libsource (lib "") (part "1.0SMBJ20A"))
    )
    (comp (ref "D34")
      (value "1.0SMBJ30A")
      (fields
        (field (name "BOM_Manufacturer Part") "1.0SMBJ20A")
        (field (name "BOM_Supplier Part") "C501367")
      )
      (libsource (lib "") (part "1.0SMBJ20A"))
    )
    (comp (ref "D35")
      (value "1.0SMBJ30A")
      (fields
        (field (name "BOM_Manufacturer Part") "1.0SMBJ20A")
        (field (name "BOM_Supplier Part") "C501367")
      )
      (libsource (lib "") (part "1.0SMBJ20A"))
    )
    (comp (ref "D36")
      (value "1.0SMBJ30A")
      (fields
        (field (name "BOM_Manufacturer Part") "1.0SMBJ20A")
        (field (name "BOM_Supplier Part") "C501367")
      )
      (libsource (lib "") (part "1.0SMBJ20A"))
    )
    (comp (ref "D37")
      (value "MMSZ5233BS-7-F")
      (fields (field (name "BOM_Supplier Part") "C508230"))
      (libsource (lib "") (part "MMSZ5233BS-7-F"))
    )
    (comp (ref "D38")
      (value "MMSZ5233BS-7-F")
      (fields (field (name "BOM_Supplier Part") "C508230"))
      (libsource (lib "") (part "MMSZ5233BS-7-F"))
    )
    (comp (ref "D39")
      (value "BZT52B10S RRG")
      (fields (field (name "BOM_Supplier Part") "C485479"))
      (libsource (lib "") (part "BZT52B10S RRG"))
    )
    (comp (ref "D40")
      (value "BZT52B10S RRG")
      (fields (field (name "BOM_Supplier Part") "C485479"))
      (libsource (lib "") (part "BZT52B10S RRG_1"))
    )
    (comp (ref "D41")
      (value "BZT52B10S RRG")
      (fields (field (name "BOM_Supplier Part") "C485479"))
      (libsource (lib "") (part "BZT52B10S RRG_1"))
    )
    (comp (ref "D42")
      (value "MBR360RLG")
      (fields (field (name "BOM_Supplier Part") "C232634"))
      (libsource (lib "") (part "MBR360RLG"))
    )
    (comp (ref "D43")
      (value "PMEG3020EGWJ")
      (fields (field (name "BOM_Supplier Part") "C552875"))
      (libsource (lib "") (part "PMEG3020EGWJ_1"))
    )
    (comp (ref "D44")
      (value "PMEG3020EGWJ")
      (fields (field (name "BOM_Supplier Part") "C552875"))
      (libsource (lib "") (part "PMEG3020EGWJ_1"))
    )
    (comp (ref "D45")
      (value "PMEG3020EGWJ")
      (fields (field (name "BOM_Supplier Part") "C552875"))
      (libsource (lib "") (part "PMEG3020EGWJ_3"))
    )
    (comp (ref "D46")
      (value "PMEG3020EGWJ")
      (fields (field (name "BOM_Supplier Part") "C552875"))
      (libsource (lib "") (part "PMEG3020EGWJ_2"))
    )
    (comp (ref "D47")
      (value "PMEG3020EGWJ")
      (fields (field (name "BOM_Supplier Part") "C552875"))
      (libsource (lib "") (part "PMEG3020EGWJ"))
    )
    (comp (ref "D48")
      (value "1N4148")
      (fields (field (name "BOM_Supplier Part") "C14516"))
      (libsource (lib "") (part "1N4148"))
    )
    (comp (ref "D49")
      (value "1SMAF4751A_C475445")
      (fields
        (field (name "BOM_Manufacturer Part") "1SMAF4751A")
        (field (name "BOM_Supplier Part") "C475445")
      )
      (libsource (lib "") (part "1SMAF4751A_C475445"))
    )
    (comp (ref "D50")
      (value "PMEG3020EGWJ")
      (fields (field (name "BOM_Supplier Part") "C552875"))
      (libsource (lib "") (part "PMEG3020EGWJ"))
    )
    (comp (ref "D51")
      (value "WSB5557Z-2/TR")
      (fields (field (name "BOM_Supplier Part") "C239812"))
      (libsource (lib "") (part "WSB5557Z-2/TR_1"))
    )
    (comp (ref "D52")
      (value "WSB5557Z-2/TR")
      (fields (field (name "BOM_Supplier Part") "C239812"))
      (libsource (lib "") (part "WSB5557Z-2/TR_1"))
    )
    (comp (ref "D53")
      (value "WSB5557Z-2/TR")
      (fields (field (name "BOM_Supplier Part") "C239812"))
      (libsource (lib "") (part "WSB5557Z-2/TR_1"))
    )
    (comp (ref "D54")
      (value "WSB5557Z-2/TR")
      (fields (field (name "BOM_Supplier Part") "C239812"))
      (libsource (lib "") (part "WSB5557Z-2/TR"))
    )
    (comp (ref "D55")
      (value "WSB5557Z-2/TR")
      (fields (field (name "BOM_Supplier Part") "C239812"))
      (libsource (lib "") (part "WSB5557Z-2/TR"))
    )
    (comp (ref "D56")
      (value "WSB5557Z-2/TR")
      (fields (field (name "BOM_Supplier Part") "C239812"))
      (libsource (lib "") (part "WSB5557Z-2/TR"))
    )
    (comp (ref "F1")
      (value "C356573")
      (fields (field (name "BOM_Manufacturer Part") "25F-100H"))
      (libsource (lib "") (part "25F-100H"))
    )
    (comp (ref "FPC1")
      (value "FH34SRJ-14S-0.5SH(50)")
      (fields (field (name "BOM_Supplier Part") "C324724"))
      (libsource (lib "") (part "FH34SRJ-14S-0.5SH(50)"))
    )
    (comp (ref "H2")
      (value "X6511WV-05H-C30D60")
      (fields (field (name "BOM_Supplier Part") "C706877"))
      (libsource (lib "") (part "X6511WV-05H-C30D60_1"))
    )
    (comp (ref "H3")
      (value "X6511WV-05H-C30D60")
      (fields (field (name "BOM_Supplier Part") "C706877"))
      (libsource (lib "") (part "X6511WV-05H-C30D60"))
    )
    (comp (ref "H4")
      (value "2111P-232SG0FYNT4")
      (fields (field (name "BOM_Supplier Part") "C721780"))
      (libsource (lib "") (part "2111P-232SG0FYNT4"))
    )
    (comp (ref "H5")
      (value "2111P-232SG0FYNT4")
      (fields (field (name "BOM_Supplier Part") "C721780"))
      (libsource (lib "") (part "2111P-232SG0FYNT4"))
    )
    (comp (ref "KEY1")
      (value "K2-3.6×6.1_SMD")
      (fields
        (field (name "BOM_Manufacturer Part") "K2-1107ST-A4SW-06")
        (field (name "BOM_Supplier Part") "C118141")
      )
      (libsource (lib "") (part "K2-3.6×6.1_SMD"))
    )
    (comp (ref "KEY2")
      (value "K2-3.6×6.1_SMD")
      (fields
        (field (name "BOM_Manufacturer Part") "K2-1107ST-A4SW-06")
        (field (name "BOM_Supplier Part") "C118141")
      )
      (libsource (lib "") (part "K2-3.6×6.1_SMD"))
    )
    (comp (ref "L1")
      (value "4.7uH")
      (fields
        (field (name "BOM_Manufacturer Part") "CKCS4030-4.7uH/M-2131")
        (field (name "BOM_Supplier Part") "C354588")
      )
      (libsource (lib "") (part "CKCS4030-4.7UH/M-2131"))
    )
    (comp (ref "L2")
      (value "100uH")
      (fields
        (field (name "BOM_Manufacturer Part") "CDRH12D77BT150NP-470MC")
        (field (name "BOM_Supplier Part") "C171600")
      )
      (libsource (lib "") (part "CDRH12D77BT150NP-470MC"))
    )
    (comp (ref "L3")
      (value "120Ω")
      (fields
        (field (name "BOM_Manufacturer Part") "BLM21PG121SZ1D")
        (field (name "BOM_Supplier Part") "C160987")
      )
      (libsource (lib "") (part "BLM21PG121SZ1D"))
    )
    (comp (ref "LED1")
      (value "LED-0603_R")
      (fields
        (field (name "BOM_Manufacturer Part") "19-217/R6C-AL1M2VY/3T")
        (field (name "BOM_Supplier Part") "C72044")
      )
      (libsource (lib "") (part "LED-0603_R"))
    )
    (comp (ref "LED2")
      (value "LED-0603_R")
      (fields
        (field (name "BOM_Manufacturer Part") "19-217/R6C-AL1M2VY/3T")
        (field (name "BOM_Supplier Part") "C72044")
      )
      (libsource (lib "") (part "LED-0603_R"))
    )
    (comp (ref "LED3")
      (value "LED-0603_R")
      (fields
        (field (name "BOM_Manufacturer Part") "19-217/R6C-AL1M2VY/3T")
        (field (name "BOM_Supplier Part") "C72044")
      )
      (libsource (lib "") (part "LED-0603_R"))
    )
    (comp (ref "LED4")
      (value "LED-0603_R")
      (fields
        (field (name "BOM_Manufacturer Part") "19-217/R6C-AL1M2VY/3T")
        (field (name "BOM_Supplier Part") "C72044")
      )
      (libsource (lib "") (part "LED-0603_R"))
    )
    (comp (ref "LED5")
      (value "LED-0603_R")
      (fields
        (field (name "BOM_Manufacturer Part") "19-217/R6C-AL1M2VY/3T")
        (field (name "BOM_Supplier Part") "C72044")
      )
      (libsource (lib "") (part "LED-0603_R"))
    )
    (comp (ref "LED6")
      (value "LED-0603_R")
      (fields
        (field (name "BOM_Manufacturer Part") "19-217/R6C-AL1M2VY/3T")
        (field (name "BOM_Supplier Part") "C72044")
      )
      (libsource (lib "") (part "LED-0603_R"))
    )
    (comp (ref "LED7")
      (value "LED-0603_R")
      (fields
        (field (name "BOM_Manufacturer Part") "19-217/R6C-AL1M2VY/3T")
        (field (name "BOM_Supplier Part") "C72044")
      )
      (libsource (lib "") (part "LED-0603_R"))
    )
    (comp (ref "Q1")
      (value "CES2323")
      (fields (field (name "BOM_Supplier Part") "C83044"))
      (libsource (lib "") (part "CES2323"))
    )
    (comp (ref "Q2")
      (value "CES2323")
      (fields (field (name "BOM_Supplier Part") "C83044"))
      (libsource (lib "") (part "CES2323"))
    )
    (comp (ref "Q3")
      (value "CES2323")
      (fields (field (name "BOM_Supplier Part") "C83044"))
      (libsource (lib "") (part "CES2323"))
    )
    (comp (ref "Q4")
      (value "CES2323")
      (fields (field (name "BOM_Supplier Part") "C83044"))
      (libsource (lib "") (part "CES2323"))
    )
    (comp (ref "Q5")
      (value "CES2323")
      (fields (field (name "BOM_Supplier Part") "C83044"))
      (libsource (lib "") (part "CES2323"))
    )
    (comp (ref "Q6")
      (value "CES2323")
      (fields (field (name "BOM_Supplier Part") "C83044"))
      (libsource (lib "") (part "CES2323"))
    )
    (comp (ref "Q7")
      (value "CES2323")
      (fields (field (name "BOM_Supplier Part") "C83044"))
      (libsource (lib "") (part "CES2323"))
    )
    (comp (ref "Q8")
      (value "CES2323")
      (fields (field (name "BOM_Supplier Part") "C83044"))
      (libsource (lib "") (part "CES2323"))
    )
    (comp (ref "Q9")
      (value "CES2323")
      (fields (field (name "BOM_Supplier Part") "C83044"))
      (libsource (lib "") (part "CES2323"))
    )
    (comp (ref "Q10")
      (value "CES2323")
      (fields (field (name "BOM_Supplier Part") "C83044"))
      (libsource (lib "") (part "CES2323"))
    )
    (comp (ref "Q11")
      (value "CES2323")
      (fields (field (name "BOM_Supplier Part") "C83044"))
      (libsource (lib "") (part "CES2323"))
    )
    (comp (ref "Q12")
      (value "CES2323")
      (fields (field (name "BOM_Supplier Part") "C83044"))
      (libsource (lib "") (part "CES2323"))
    )
    (comp (ref "Q13")
      (value "CES2323")
      (fields (field (name "BOM_Supplier Part") "C83044"))
      (libsource (lib "") (part "CES2323"))
    )
    (comp (ref "Q14")
      (value "CES2323")
      (fields (field (name "BOM_Supplier Part") "C83044"))
      (libsource (lib "") (part "CES2323"))
    )
    (comp (ref "Q15")
      (value "CES2323")
      (fields (field (name "BOM_Supplier Part") "C83044"))
      (libsource (lib "") (part "CES2323"))
    )
    (comp (ref "Q16")
      (value "CES2323")
      (fields (field (name "BOM_Supplier Part") "C83044"))
      (libsource (lib "") (part "CES2323"))
    )
    (comp (ref "Q17")
      (value "CES2323")
      (fields (field (name "BOM_Supplier Part") "C83044"))
      (libsource (lib "") (part "CES2323"))
    )
    (comp (ref "Q18")
      (value "CES2323")
      (fields (field (name "BOM_Supplier Part") "C83044"))
      (libsource (lib "") (part "CES2323"))
    )
    (comp (ref "Q19")
      (value "SI1422DH-T1-GE3")
      (fields (field (name "BOM_Supplier Part") "C144842"))
      (libsource (lib "") (part "SI1422DH-T1-GE3"))
    )
    (comp (ref "Q20")
      (value "SI1422DH-T1-GE3")
      (fields (field (name "BOM_Supplier Part") "C144842"))
      (libsource (lib "") (part "SI1422DH-T1-GE3"))
    )
    (comp (ref "Q21") (value "MTN003N02Y3") (libsource (lib "") (part "SLS2302")))
    (comp (ref "Q22")
      (value "FDS4897A")
      (fields (field (name "BOM_Supplier Part") "C693180"))
      (libsource (lib "") (part "FDS4897A"))
    )
    (comp (ref "Q23")
      (value "SM2326NSANC-TRG")
      (fields (field (name "BOM_Supplier Part") "C368561"))
      (libsource (lib "") (part "SM2326NSANC-TRG"))
    )
    (comp (ref "Q24")
      (value "SM4186T9RL")
      (fields (field (name "BOM_Supplier Part") "C496601"))
      (libsource (lib "") (part "SM4186T9RL"))
    )
    (comp (ref "R1")
      (value "94,2k")
      (fields
        (field (name "BOM_Manufacturer Part") "WR02X1873FAL")
        (field (name "BOM_Supplier Part") "C171920")
      )
      (libsource (lib "") (part "WR02X1873FAL"))
    )
    (comp (ref "R2")
      (value "94,2k")
      (fields
        (field (name "BOM_Manufacturer Part") "WR02X1873FAL")
        (field (name "BOM_Supplier Part") "C171920")
      )
      (libsource (lib "") (part "WR02X1873FAL"))
    )
    (comp (ref "R3")
      (value "94,2k")
      (fields
        (field (name "BOM_Manufacturer Part") "WR02X1873FAL")
        (field (name "BOM_Supplier Part") "C171920")
      )
      (libsource (lib "") (part "WR02X1873FAL"))
    )
    (comp (ref "R4")
      (value "94,2k")
      (fields
        (field (name "BOM_Manufacturer Part") "WR02X1873FAL")
        (field (name "BOM_Supplier Part") "C171920")
      )
      (libsource (lib "") (part "WR02X1873FAL"))
    )
    (comp (ref "R5")
      (value "10K")
      (fields
        (field (name "BOM_Manufacturer Part") "0603WAF1002T5E")
        (field (name "BOM_Supplier Part") "C25804")
      )
      (libsource (lib "") (part "0603WAF1002T5E"))
    )
    (comp (ref "R6")
      (value "10K")
      (fields
        (field (name "BOM_Manufacturer Part") "0603WAF1002T5E")
        (field (name "BOM_Supplier Part") "C25804")
      )
      (libsource (lib "") (part "0603WAF1002T5E"))
    )
    (comp (ref "R7")
      (value "10K")
      (fields
        (field (name "BOM_Manufacturer Part") "0603WAF1002T5E")
        (field (name "BOM_Supplier Part") "C25804")
      )
      (libsource (lib "") (part "0603WAF1002T5E"))
    )
    (comp (ref "R8")
      (value "1,6M")
      (fields
        (field (name "BOM_Manufacturer Part") "CR1206-FX-1603ELF")
        (field (name "BOM_Supplier Part") "C204681")
      )
      (libsource (lib "") (part "CR1206-FX-1603ELF"))
    )
    (comp (ref "R9")
      (value "1,6M")
      (fields
        (field (name "BOM_Manufacturer Part") "CR1206-FX-1603ELF")
        (field (name "BOM_Supplier Part") "C204681")
      )
      (libsource (lib "") (part "CR1206-FX-1603ELF"))
    )
    (comp (ref "R10")
      (value "1,6M")
      (fields
        (field (name "BOM_Manufacturer Part") "CR1206-FX-1603ELF")
        (field (name "BOM_Supplier Part") "C204681")
      )
      (libsource (lib "") (part "CR1206-FX-1603ELF"))
    )
    (comp (ref "R11")
      (value "1,6M")
      (fields
        (field (name "BOM_Manufacturer Part") "CR1206-FX-1603ELF")
        (field (name "BOM_Supplier Part") "C204681")
      )
      (libsource (lib "") (part "CR1206-FX-1603ELF"))
    )
    (comp (ref "R12")
      (value "10K")
      (fields
        (field (name "BOM_Manufacturer Part") "0603WAF1002T5E")
        (field (name "BOM_Supplier Part") "C25804")
      )
      (libsource (lib "") (part "0603WAF1002T5E"))
    )
    (comp (ref "R13")
      (value "10K")
      (fields
        (field (name "BOM_Manufacturer Part") "0603WAF1002T5E")
        (field (name "BOM_Supplier Part") "C25804")
      )
      (libsource (lib "") (part "0603WAF1002T5E"))
    )
    (comp (ref "R14") (value "200") (libsource (lib "") (part "R_0603_EU_1")))
    (comp (ref "R15") (value "200") (libsource (lib "") (part "R_0603_EU_1")))
    (comp (ref "R16") (value "200") (libsource (lib "") (part "R_0603_EU_1")))
    (comp (ref "R17") (value "200") (libsource (lib "") (part "R_0603_EU_1")))
    (comp (ref "R18") (value "200") (libsource (lib "") (part "R_0603_EU_1")))
    (comp (ref "R19") (value "200") (libsource (lib "") (part "R_0603_EU_1")))
    (comp (ref "R20") (value "200") (libsource (lib "") (part "R_0603_EU_1")))
    (comp (ref "R21") (value "200") (libsource (lib "") (part "R_0603_EU_1")))
    (comp (ref "R22") (value "200") (libsource (lib "") (part "R_0603_EU_1")))
    (comp (ref "R23") (value "200") (libsource (lib "") (part "R_0603_EU_1")))
    (comp (ref "R24") (value "200") (libsource (lib "") (part "R_0603_EU_1")))
    (comp (ref "R25") (value "200") (libsource (lib "") (part "R_0603_EU_1")))
    (comp (ref "R26") (value "200") (libsource (lib "") (part "R_0603_EU_1")))
    (comp (ref "R27") (value "200") (libsource (lib "") (part "R_0603_EU_1")))
    (comp (ref "R28") (value "200") (libsource (lib "") (part "R_0603_EU_1")))
    (comp (ref "R29") (value "200") (libsource (lib "") (part "R_0603_EU_1")))
    (comp (ref "R30") (value "200") (libsource (lib "") (part "R_0603_EU_1")))
    (comp (ref "R31") (value "200") (libsource (lib "") (part "R_0603_EU_1")))
    (comp (ref "R32") (value "1k") (libsource (lib "") (part "R_0603_EU")))
    (comp (ref "R33") (value "1k") (libsource (lib "") (part "R_0603_EU")))
    (comp (ref "R34") (value "1k") (libsource (lib "") (part "R_0603_EU")))
    (comp (ref "R35") (value "1k") (libsource (lib "") (part "R_0603_EU")))
    (comp (ref "R36") (value "1k") (libsource (lib "") (part "R_0603_EU")))
    (comp (ref "R37") (value "1k") (libsource (lib "") (part "R_0603_EU")))
    (comp (ref "R38") (value "1k") (libsource (lib "") (part "R_0603_EU")))
    (comp (ref "R39") (value "1k") (libsource (lib "") (part "R_0603_EU")))
    (comp (ref "R40") (value "1k") (libsource (lib "") (part "R_0603_EU")))
    (comp (ref "R41") (value "1k") (libsource (lib "") (part "R_0603_EU")))
    (comp (ref "R42") (value "1k") (libsource (lib "") (part "R_0603_EU")))
    (comp (ref "R43") (value "1k") (libsource (lib "") (part "R_0603_EU")))
    (comp (ref "R44") (value "1k") (libsource (lib "") (part "R_0603_EU")))
    (comp (ref "R45") (value "1k") (libsource (lib "") (part "R_0603_EU")))
    (comp (ref "R46") (value "1k") (libsource (lib "") (part "R_0603_EU")))
    (comp (ref "R47") (value "1k") (libsource (lib "") (part "R_0603_EU")))
    (comp (ref "R48") (value "1k") (libsource (lib "") (part "R_0603_EU")))
    (comp (ref "R49") (value "1k") (libsource (lib "") (part "R_0603_EU")))
    (comp (ref "R50")
      (value "10K")
      (fields
        (field (name "BOM_Manufacturer Part") "0603WAF1002T5E")
        (field (name "BOM_Supplier Part") "C25804")
      )
      (libsource (lib "") (part "0603WAF1002T5E"))
    )
    (comp (ref "R51")
      (value "1K")
      (fields
        (field (name "BOM_Manufacturer Part") "CR1206F41001G")
        (field (name "BOM_Supplier Part") "C102060")
      )
      (libsource (lib "") (part "CR1206F41001G"))
    )
    (comp (ref "R52")
      (value "1K")
      (fields
        (field (name "BOM_Manufacturer Part") "CR1206F41001G")
        (field (name "BOM_Supplier Part") "C102060")
      )
      (libsource (lib "") (part "CR1206F41001G"))
    )
    (comp (ref "R53")
      (value "1K")
      (fields
        (field (name "BOM_Manufacturer Part") "CR1206F41001G")
        (field (name "BOM_Supplier Part") "C102060")
      )
      (libsource (lib "") (part "CR1206F41001G"))
    )
    (comp (ref "R54")
      (value "1K")
      (fields
        (field (name "BOM_Manufacturer Part") "CR1206F41001G")
        (field (name "BOM_Supplier Part") "C102060")
      )
      (libsource (lib "") (part "CR1206F41001G"))
    )
    (comp (ref "R55")
      (value "1K")
      (fields
        (field (name "BOM_Manufacturer Part") "CR1206F41001G")
        (field (name "BOM_Supplier Part") "C102060")
      )
      (libsource (lib "") (part "CR1206F41001G"))
    )
    (comp (ref "R56")
      (value "1K")
      (fields
        (field (name "BOM_Manufacturer Part") "CR1206F41001G")
        (field (name "BOM_Supplier Part") "C102060")
      )
      (libsource (lib "") (part "CR1206F41001G"))
    )
    (comp (ref "R57")
      (value "1K")
      (fields
        (field (name "BOM_Manufacturer Part") "CR1206F41001G")
        (field (name "BOM_Supplier Part") "C102060")
      )
      (libsource (lib "") (part "CR1206F41001G"))
    )
    (comp (ref "R58")
      (value "10K")
      (fields
        (field (name "BOM_Manufacturer Part") "RNCF0402BTE10K0")
        (field (name "BOM_Supplier Part") "C346559")
      )
      (libsource (lib "") (part "RNCF0402BTE10K0"))
    )
    (comp (ref "R59")
      (value "200")
      (fields
        (field (name "BOM_Manufacturer Part") "RMC12062005%N")
        (field (name "BOM_Supplier Part") "C269602")
      )
      (libsource (lib "") (part "RMC12062005%N"))
    )
    (comp (ref "R60")
      (value "200")
      (fields
        (field (name "BOM_Manufacturer Part") "RMC12062005%N")
        (field (name "BOM_Supplier Part") "C269602")
      )
      (libsource (lib "") (part "RMC12062005%N"))
    )
    (comp (ref "R61")
      (value "10K")
      (fields
        (field (name "BOM_Manufacturer Part") "RC-01W103JT")
        (field (name "BOM_Supplier Part") "C304504")
      )
      (libsource (lib "") (part "RC-01W103JT_1"))
    )
    (comp (ref "R62")
      (value "10K")
      (fields
        (field (name "BOM_Manufacturer Part") "RC-01W103JT")
        (field (name "BOM_Supplier Part") "C304504")
      )
      (libsource (lib "") (part "RC-01W103JT_1"))
    )
    (comp (ref "R63")
      (value "42.2")
      (fields
        (field (name "BOM_Manufacturer Part") "RC-12K42R2FT")
        (field (name "BOM_Supplier Part") "C454007")
      )
      (libsource (lib "") (part "RC-12K42R2FT"))
    )
    (comp (ref "R64")
      (value "1K")
      (fields
        (field (name "BOM_Manufacturer Part") "TR1218F1KE0450")
        (field (name "BOM_Supplier Part") "C175641")
      )
      (libsource (lib "") (part "TR1218F1KE0450"))
    )
    (comp (ref "R65")
      (value "100")
      (fields
        (field (name "BOM_Manufacturer Part") "FCR1206J100RP055W")
        (field (name "BOM_Supplier Part") "C153338")
      )
      (libsource (lib "") (part "FCR1206J100RP055W"))
    )
    (comp (ref "R66")
      (value "10")
      (fields
        (field (name "BOM_Manufacturer Part") "RMC1206101%N")
        (field (name "BOM_Supplier Part") "C269633")
      )
      (libsource (lib "") (part "RMC1206101%N"))
    )
    (comp (ref "R67")
      (value "10")
      (fields
        (field (name "BOM_Manufacturer Part") "RMC1206101%N")
        (field (name "BOM_Supplier Part") "C269633")
      )
      (libsource (lib "") (part "RMC1206101%N"))
    )
    (comp (ref "R68")
      (value "1K")
      (fields
        (field (name "BOM_Manufacturer Part") "CR1206F41001G")
        (field (name "BOM_Supplier Part") "C102060")
      )
      (libsource (lib "") (part "CR1206F41001G_1"))
    )
    (comp (ref "R69")
      (value "4.7K")
      (fields
        (field (name "BOM_Manufacturer Part") "ERJPA2J472X")
        (field (name "BOM_Supplier Part") "C427213")
      )
      (libsource (lib "") (part "ERJPA2J472X"))
    )
    (comp (ref "R70")
      (value "4.7K")
      (fields
        (field (name "BOM_Manufacturer Part") "ERJPA2J472X")
        (field (name "BOM_Supplier Part") "C427213")
      )
      (libsource (lib "") (part "ERJPA2J472X"))
    )
    (comp (ref "R71")
      (value "1K")
      (fields
        (field (name "BOM_Manufacturer Part") "RMC12061K5%N")
        (field (name "BOM_Supplier Part") "C269755")
      )
      (libsource (lib "") (part "RMC12061K5%N_1"))
    )
    (comp (ref "R72")
      (value "1K")
      (fields
        (field (name "BOM_Manufacturer Part") "RMC12061K5%N")
        (field (name "BOM_Supplier Part") "C269755")
      )
      (libsource (lib "") (part "RMC12061K5%N"))
    )
    (comp (ref "R73")
      (value "10K")
      (fields
        (field (name "BOM_Manufacturer Part") "0603WAF1002T5E")
        (field (name "BOM_Supplier Part") "C25804")
      )
      (libsource (lib "") (part "0603WAF1002T5E_1"))
    )
    (comp (ref "R74")
      (value "200")
      (fields
        (field (name "BOM_Manufacturer Part") "RMC12062005%N")
        (field (name "BOM_Supplier Part") "C269602")
      )
      (libsource (lib "") (part "RMC12062005%N_1"))
    )
    (comp (ref "R75")
      (value "10K")
      (fields
        (field (name "BOM_Manufacturer Part") "RC-01W103JT")
        (field (name "BOM_Supplier Part") "C304504")
      )
      (libsource (lib "") (part "RC-01W103JT"))
    )
    (comp (ref "R76")
      (value "10K")
      (fields
        (field (name "BOM_Manufacturer Part") "RC-01W103JT")
        (field (name "BOM_Supplier Part") "C304504")
      )
      (libsource (lib "") (part "RC-01W103JT"))
    )
    (comp (ref "R77")
      (value "10K")
      (fields
        (field (name "BOM_Manufacturer Part") "RC-01W103JT")
        (field (name "BOM_Supplier Part") "C304504")
      )
      (libsource (lib "") (part "RC-01W103JT"))
    )
    (comp (ref "R78")
      (value "10K")
      (fields
        (field (name "BOM_Manufacturer Part") "RC-01W103JT")
        (field (name "BOM_Supplier Part") "C304504")
      )
      (libsource (lib "") (part "RC-01W103JT"))
    )
    (comp (ref "R79")
      (value "10K")
      (fields
        (field (name "BOM_Manufacturer Part") "RC-01W103JT")
        (field (name "BOM_Supplier Part") "C304504")
      )
      (libsource (lib "") (part "RC-01W103JT"))
    )
    (comp (ref "R80")
      (value "1K")
      (fields
        (field (name "BOM_Manufacturer Part") "RC-01W103JT")
        (field (name "BOM_Supplier Part") "C304504")
      )
      (libsource (lib "") (part "RC-01W103JT"))
    )
    (comp (ref "R81")
      (value "1K")
      (fields
        (field (name "BOM_Manufacturer Part") "RC-01W103JT")
        (field (name "BOM_Supplier Part") "C304504")
      )
      (libsource (lib "") (part "RC-01W103JT"))
    )
    (comp (ref "R82")
      (value "1K")
      (fields
        (field (name "BOM_Manufacturer Part") "RC-01W103JT")
        (field (name "BOM_Supplier Part") "C304504")
      )
      (libsource (lib "") (part "RC-01W103JT"))
    )
    (comp (ref "R83")
      (value "1K")
      (fields
        (field (name "BOM_Manufacturer Part") "RC-01W103JT")
        (field (name "BOM_Supplier Part") "C304504")
      )
      (libsource (lib "") (part "RC-01W103JT"))
    )
    (comp (ref "R84")
      (value "1K")
      (fields
        (field (name "BOM_Manufacturer Part") "RC-01W103JT")
        (field (name "BOM_Supplier Part") "C304504")
      )
      (libsource (lib "") (part "RC-01W103JT"))
    )
    (comp (ref "R85")
      (value "1K")
      (fields
        (field (name "BOM_Manufacturer Part") "RC-01W103JT")
        (field (name "BOM_Supplier Part") "C304504")
      )
      (libsource (lib "") (part "RC-01W103JT"))
    )
    (comp (ref "R86")
      (value "1K")
      (fields
        (field (name "BOM_Manufacturer Part") "RC-01W103JT")
        (field (name "BOM_Supplier Part") "C304504")
      )
      (libsource (lib "") (part "RC-01W103JT"))
    )
    (comp (ref "R87")
      (value "1K")
      (fields
        (field (name "BOM_Manufacturer Part") "RC-01W103JT")
        (field (name "BOM_Supplier Part") "C304504")
      )
      (libsource (lib "") (part "RC-01W103JT"))
    )
    (comp (ref "R88")
      (value "1K")
      (fields
        (field (name "BOM_Manufacturer Part") "RC-01W103JT")
        (field (name "BOM_Supplier Part") "C304504")
      )
      (libsource (lib "") (part "RC-01W103JT"))
    )
    (comp (ref "R89")
      (value "1K")
      (fields
        (field (name "BOM_Manufacturer Part") "RC-01W103JT")
        (field (name "BOM_Supplier Part") "C304504")
      )
      (libsource (lib "") (part "RC-01W103JT"))
    )
    (comp (ref "R90")
      (value "1K")
      (fields
        (field (name "BOM_Manufacturer Part") "RC-01W103JT")
        (field (name "BOM_Supplier Part") "C304504")
      )
      (libsource (lib "") (part "RC-01W103JT"))
    )
    (comp (ref "R91")
      (value "1K")
      (fields
        (field (name "BOM_Manufacturer Part") "RC-01W103JT")
        (field (name "BOM_Supplier Part") "C304504")
      )
      (libsource (lib "") (part "RC-01W103JT"))
    )
    (comp (ref "R92")
      (value "1K")
      (fields
        (field (name "BOM_Manufacturer Part") "RC-01W103JT")
        (field (name "BOM_Supplier Part") "C304504")
      )
      (libsource (lib "") (part "RC-01W103JT"))
    )
    (comp (ref "R93")
      (value "1K")
      (fields
        (field (name "BOM_Manufacturer Part") "RC-01W103JT")
        (field (name "BOM_Supplier Part") "C304504")
      )
      (libsource (lib "") (part "RC-01W103JT"))
    )
    (comp (ref "R94")
      (value "16K")
      (fields
        (field (name "BOM_Manufacturer Part") "CR1206-FX-1602ELF")
        (field (name "BOM_Supplier Part") "C204680")
      )
      (libsource (lib "") (part "CR1206-FX-1602ELF"))
    )
    (comp (ref "R95")
      (value "16K")
      (fields
        (field (name "BOM_Manufacturer Part") "CR1206-FX-1602ELF")
        (field (name "BOM_Supplier Part") "C204680")
      )
      (libsource (lib "") (part "CR1206-FX-1602ELF"))
    )
    (comp (ref "R96")
      (value "36k")
      (fields
        (field (name "BOM_Manufacturer Part") "RK73H2BTTD3602F")
        (field (name "BOM_Supplier Part") "C880208")
      )
      (libsource (lib "") (part "RK73H2BTTD3602F"))
    )
    (comp (ref "R97")
      (value "36k")
      (fields
        (field (name "BOM_Manufacturer Part") "RK73H2BTTD3602F")
        (field (name "BOM_Supplier Part") "C880208")
      )
      (libsource (lib "") (part "RK73H2BTTD3602F"))
    )
    (comp (ref "R98")
      (value "39K")
      (fields
        (field (name "BOM_Manufacturer Part") "ERJ6ENF3902V")
        (field (name "BOM_Supplier Part") "C413307")
      )
      (libsource (lib "") (part "ERJ6ENF3902V"))
    )
    (comp (ref "R99")
      (value "10K")
      (fields
        (field (name "BOM_Manufacturer Part") "0603WAF1002T5E")
        (field (name "BOM_Supplier Part") "C25804")
      )
      (libsource (lib "") (part "0603WAF1002T5E"))
    )
    (comp (ref "R100")
      (value "100")
      (fields
        (field (name "BOM_Manufacturer Part") "CR1206F100RP05")
        (field (name "BOM_Supplier Part") "C245445")
      )
      (libsource (lib "") (part "CR1206F100RP05"))
    )
    (comp (ref "R101")
      (value "4.7kΩ")
      (fields
        (field (name "BOM_Manufacturer Part") "RK73G2ATTD4701F")
        (field (name "BOM_Supplier Part") "C516091")
      )
      (libsource (lib "") (part "RK73G2ATTD4701F"))
    )
    (comp (ref "R102")
      (value "39K")
      (fields
        (field (name "BOM_Manufacturer Part") "ERJ6ENF3902V")
        (field (name "BOM_Supplier Part") "C413307")
      )
      (libsource (lib "") (part "ERJ6ENF3902V"))
    )
    (comp (ref "R103")
      (value "39K")
      (fields
        (field (name "BOM_Manufacturer Part") "ERJ6ENF3902V")
        (field (name "BOM_Supplier Part") "C413307")
      )
      (libsource (lib "") (part "ERJ6ENF3902V"))
    )
    (comp (ref "R104")
      (value "39K")
      (fields
        (field (name "BOM_Manufacturer Part") "ERJ6ENF3902V")
        (field (name "BOM_Supplier Part") "C413307")
      )
      (libsource (lib "") (part "ERJ6ENF3902V"))
    )
    (comp (ref "RSH1") (value "0.55") (libsource (lib "") (part "R_0603_EU_2")))
    (comp (ref "U1")
      (value "B2B-XH-A-GU")
      (fields (field (name "BOM_Supplier Part") "C265283"))
      (libsource (lib "") (part "B2B-XH-A-GU"))
    )
    (comp (ref "U2")
      (value "B2B-XH-A-GU")
      (fields (field (name "BOM_Supplier Part") "C265283"))
      (libsource (lib "") (part "B2B-XH-A-GU"))
    )
    (comp (ref "U3")
      (value "B2B-XH-A-GU")
      (fields (field (name "BOM_Supplier Part") "C265283"))
      (libsource (lib "") (part "B2B-XH-A-GU"))
    )
    (comp (ref "U4")
      (value "B2B-XH-A-GU")
      (fields (field (name "BOM_Supplier Part") "C265283"))
      (libsource (lib "") (part "B2B-XH-A-GU"))
    )
    (comp (ref "U5")
      (value "ADS7841E/2K5")
      (fields (field (name "BOM_Supplier Part") "C41778"))
      (libsource (lib "") (part "ADS7841E/2K5"))
    )
    (comp (ref "U6")
      (value "B4B-XH-AM(LF)(SN)")
      (fields (field (name "BOM_Supplier Part") "C161871"))
      (libsource (lib "") (part "B4B-XH-AM(LF)(SN)"))
    )
    (comp (ref "U7")
      (value "TLC2543N")
      (fields (field (name "BOM_Supplier Part") "C398066"))
      (libsource (lib "") (part "TLC2543N"))
    )
    (comp (ref "U8")
      (value "TLC2543N")
      (fields (field (name "BOM_Supplier Part") "C398066"))
      (libsource (lib "") (part "TLC2543N"))
    )
    (comp (ref "U9")
      (value "74HC595PW,112")
      (fields (field (name "BOM_Supplier Part") "C547128"))
      (libsource (lib "") (part "74HC595PW,112"))
    )
    (comp (ref "U10")
      (value "ACS714LLCTR-50A-T")
      (fields (field (name "BOM_Supplier Part") "C163302"))
      (libsource (lib "") (part "ACS714LLCTR-50A-T"))
    )
    (comp (ref "U11")
      (value "ACS714LLCTR-50A-T")
      (fields (field (name "BOM_Supplier Part") "C163302"))
      (libsource (lib "") (part "ACS714LLCTR-50A-T"))
    )
    (comp (ref "U12")
      (value "ACS714LLCTR-50A-T")
      (fields (field (name "BOM_Supplier Part") "C163302"))
      (libsource (lib "") (part "ACS714LLCTR-50A-T"))
    )
    (comp (ref "U13")
      (value "ACS714LLCTR-50A-T")
      (fields (field (name "BOM_Supplier Part") "C163302"))
      (libsource (lib "") (part "ACS714LLCTR-50A-T"))
    )
    (comp (ref "U14")
      (value "ACS714LLCTR-50A-T")
      (fields (field (name "BOM_Supplier Part") "C163302"))
      (libsource (lib "") (part "ACS714LLCTR-50A-T"))
    )
    (comp (ref "U15")
      (value "ACS714LLCTR-50A-T")
      (fields (field (name "BOM_Supplier Part") "C163302"))
      (libsource (lib "") (part "ACS714LLCTR-50A-T"))
    )
    (comp (ref "U16")
      (value "ACS714LLCTR-50A-T")
      (fields (field (name "BOM_Supplier Part") "C163302"))
      (libsource (lib "") (part "ACS714LLCTR-50A-T"))
    )
    (comp (ref "U17")
      (value "ACS714LLCTR-50A-T")
      (fields (field (name "BOM_Supplier Part") "C163302"))
      (libsource (lib "") (part "ACS714LLCTR-50A-T"))
    )
    (comp (ref "U18")
      (value "ACS714LLCTR-50A-T")
      (fields (field (name "BOM_Supplier Part") "C163302"))
      (libsource (lib "") (part "ACS714LLCTR-50A-T"))
    )
    (comp (ref "U19")
      (value "ACS714LLCTR-50A-T")
      (fields (field (name "BOM_Supplier Part") "C163302"))
      (libsource (lib "") (part "ACS714LLCTR-50A-T"))
    )
    (comp (ref "U20")
      (value "ACS714LLCTR-50A-T")
      (fields (field (name "BOM_Supplier Part") "C163302"))
      (libsource (lib "") (part "ACS714LLCTR-50A-T"))
    )
    (comp (ref "U21")
      (value "ACS714LLCTR-50A-T")
      (fields (field (name "BOM_Supplier Part") "C163302"))
      (libsource (lib "") (part "ACS714LLCTR-50A-T"))
    )
    (comp (ref "U22")
      (value "ACS714LLCTR-50A-T")
      (fields (field (name "BOM_Supplier Part") "C163302"))
      (libsource (lib "") (part "ACS714LLCTR-50A-T"))
    )
    (comp (ref "U23")
      (value "ACS714LLCTR-50A-T")
      (fields (field (name "BOM_Supplier Part") "C163302"))
      (libsource (lib "") (part "ACS714LLCTR-50A-T"))
    )
    (comp (ref "U24")
      (value "ACS714LLCTR-50A-T")
      (fields (field (name "BOM_Supplier Part") "C163302"))
      (libsource (lib "") (part "ACS714LLCTR-50A-T"))
    )
    (comp (ref "U25")
      (value "ACS714LLCTR-50A-T")
      (fields (field (name "BOM_Supplier Part") "C163302"))
      (libsource (lib "") (part "ACS714LLCTR-50A-T"))
    )
    (comp (ref "U26")
      (value "ACS714LLCTR-50A-T")
      (fields (field (name "BOM_Supplier Part") "C163302"))
      (libsource (lib "") (part "ACS714LLCTR-50A-T"))
    )
    (comp (ref "U27")
      (value "ACS714LLCTR-50A-T")
      (fields (field (name "BOM_Supplier Part") "C163302"))
      (libsource (lib "") (part "ACS714LLCTR-50A-T"))
    )
    (comp (ref "U28")
      (value "LM2576HVR-12")
      (fields (field (name "BOM_Supplier Part") "C126036"))
      (libsource (lib "") (part "LM2576HVR-12"))
    )
    (comp (ref "U29")
      (value "TI INA229")
      (fields (field (name "BOM_Manufacturer Part") "INA229"))
      (libsource (lib "") (part "TI INA229"))
    )
    (comp (ref "U30")
      (value "0435002.KR")
      (fields (field (name "BOM_Supplier Part") "C206948"))
      (libsource (lib "") (part "0435002.KR"))
    )
    (comp (ref "U31")
      (value "NLAS4157DFT2G")
      (fields (field (name "BOM_Supplier Part") "C106912"))
      (libsource (lib "") (part "NLAS4157DFT2G"))
    )
    (comp (ref "U32")
      (value "NX3L4051PW,118")
      (fields (field (name "BOM_Supplier Part") "C2673441"))
      (libsource (lib "") (part "NX3L4051PW,118"))
    )
    (comp (ref "U33")
      (value "NX3L4051PW,118")
      (fields (field (name "BOM_Supplier Part") "C2673441"))
      (libsource (lib "") (part "NX3L4051PW,118"))
    )
    (comp (ref "U34")
      (value "NX3L4051PW,118")
      (fields (field (name "BOM_Supplier Part") "C2673441"))
      (libsource (lib "") (part "NX3L4051PW,118"))
    )
    (comp (ref "U35")
      (value "NX3L4051PW,118")
      (fields (field (name "BOM_Supplier Part") "C2673441"))
      (libsource (lib "") (part "NX3L4051PW,118"))
    )
    (comp (ref "U36")
      (value "NX3L4051PW,118")
      (fields (field (name "BOM_Supplier Part") "C2673441"))
      (libsource (lib "") (part "NX3L4051PW,118"))
    )
    (comp (ref "U37")
      (value "NX3L4051PW,118")
      (fields (field (name "BOM_Supplier Part") "C2673441"))
      (libsource (lib "") (part "NX3L4051PW,118"))
    )
    (comp (ref "U38")
      (value "NX3L4051PW,118")
      (fields (field (name "BOM_Supplier Part") "C2673441"))
      (libsource (lib "") (part "NX3L4051PW,118"))
    )
    (comp (ref "U39")
      (value "AIC1117A-25GYTR")
      (fields (field (name "BOM_Supplier Part") "C238209"))
      (libsource (lib "") (part "AIC1117A-25GYTR"))
    )
    (comp (ref "U40")
      (value "NLAS4157DFT2G")
      (fields (field (name "BOM_Supplier Part") "C106912"))
      (libsource (lib "") (part "NLAS4157DFT2G"))
    )
    (comp (ref "U41")
      (value "NLAS4157DFT2G")
      (fields (field (name "BOM_Supplier Part") "C106912"))
      (libsource (lib "") (part "NLAS4157DFT2G"))
    )
    (comp (ref "U42")
      (value "NX3L4051PW,118")
      (fields (field (name "BOM_Supplier Part") "C2673441"))
      (libsource (lib "") (part "NX3L4051PW,118"))
    )
    (comp (ref "U43")
      (value "NX3L4051PW,118")
      (fields (field (name "BOM_Supplier Part") "C2673441"))
      (libsource (lib "") (part "NX3L4051PW,118"))
    )
    (comp (ref "U44")
      (value "NX3L4051PW,118")
      (fields (field (name "BOM_Supplier Part") "C2673441"))
      (libsource (lib "") (part "NX3L4051PW,118"))
    )
    (comp (ref "U45")
      (value "NX3L4051PW,118")
      (fields (field (name "BOM_Supplier Part") "C2673441"))
      (libsource (lib "") (part "NX3L4051PW,118"))
    )
    (comp (ref "U46")
      (value "NX3L4051PW,118")
      (fields (field (name "BOM_Supplier Part") "C2673441"))
      (libsource (lib "") (part "NX3L4051PW,118"))
    )
    (comp (ref "U47")
      (value "NX3L4051PW,118")
      (fields (field (name "BOM_Supplier Part") "C2673441"))
      (libsource (lib "") (part "NX3L4051PW,118"))
    )
    (comp (ref "U48")
      (value "NX3L4051PW,118")
      (fields (field (name "BOM_Supplier Part") "C2673441"))
      (libsource (lib "") (part "NX3L4051PW,118"))
    )
    (comp (ref "U49")
      (value "ADG706BRUZ-REEL7")
      (fields (field (name "BOM_Supplier Part") "C408400"))
      (libsource (lib "") (part "ADG706BRUZ-REEL7"))
    )
    (comp (ref "U50") (value "ADG1406BCPZ-REEL7") (libsource (lib "") (part "ADG1406BCPZ-REEL7_1")))
    (comp (ref "U51") (value "ADG1406BCPZ-REEL7") (libsource (lib "") (part "ADG1406BCPZ-REEL7")))
    (comp (ref "U52")
      (value "MAX11100EUB+")
      (fields (field (name "BOM_Supplier Part") "C143329"))
      (libsource (lib "") (part "MAX11100EUB+"))
    )
    (comp (ref "U53")
      (value "ADG706BRUZ-REEL7")
      (fields (field (name "BOM_Supplier Part") "C408400"))
      (libsource (lib "") (part "ADG706BRUZ-REEL7"))
    )
    (comp (ref "U54")
      (value "AD8278ARZ-R7")
      (fields (field (name "BOM_Supplier Part") "C652635"))
      (libsource (lib "") (part "AD8278ARZ-R7"))
    )
    (comp (ref "U55") (value "ADG1406BCPZ-REEL7") (libsource (lib "") (part "ADG1406BCPZ-REEL7")))
    (comp (ref "U56")
      (value "MAX7301AAX+")
      (fields (field (name "BOM_Supplier Part") "C143583"))
      (libsource (lib "") (part "MAX7301AAX+"))
    )
    (comp (ref "U57")
      (value "MAX7301AAX+")
      (fields (field (name "BOM_Supplier Part") "C143583"))
      (libsource (lib "") (part "MAX7301AAX+"))
    )
    (comp (ref "U58")
      (value "MAX7301AAX+")
      (fields (field (name "BOM_Supplier Part") "C143583"))
      (libsource (lib "") (part "MAX7301AAX+"))
    )
    (comp (ref "U59")
      (value "MAX7301AAX+")
      (fields (field (name "BOM_Supplier Part") "C143583"))
      (libsource (lib "") (part "MAX7301AAX+"))
    )
    (comp (ref "U60")
      (value "STM32F411CCU6TR")
      (fields (field (name "BOM_Supplier Part") "C190642"))
      (libsource (lib "") (part "STM32F411CCU6TR"))
    )
    (comp (ref "U61") (value "SMAQ-7050A") (libsource (lib "") (part "SMAQ-7050A")))
    (comp (ref "U62") (value "SMAQ-7050A") (libsource (lib "") (part "SMAQ-7050A")))
  )
  (nets
    (net (code "1") (name "+5v") (class "Default")
      (node (ref "C117") (pin "1") (pinfunction "1_1") (pintype "unspecified"))
      (node (ref "C118") (pin "1") (pinfunction "1_1") (pintype "unspecified"))
      (node (ref "C119") (pin "1") (pinfunction "1_1") (pintype "unspecified"))
      (node (ref "C120") (pin "2") (pinfunction "2_2") (pintype "unspecified"))
      (node (ref "C121") (pin "2") (pinfunction "2_2") (pintype "unspecified"))
      (node (ref "C122") (pin "2") (pinfunction "2_2") (pintype "unspecified"))
      (node (ref "C99") (pin "2") (pinfunction "2_2") (pintype "unspecified"))
      (node (ref "D54") (pin "2") (pinfunction "A_2") (pintype "unspecified"))
      (node (ref "D55") (pin "2") (pinfunction "A_2") (pintype "unspecified"))
      (node (ref "D56") (pin "2") (pinfunction "A_2") (pintype "unspecified"))
      (node (ref "H3") (pin "1") (pinfunction "1_1") (pintype "unspecified"))
      (node (ref "U7") (pin "20") (pinfunction "VCC_20") (pintype "unspecified"))
      (node (ref "U8") (pin "20") (pinfunction "VCC_20") (pintype "unspecified"))
      (node (ref "U9") (pin "10") (pinfunction "MR#_10") (pintype "unspecified"))
      (node (ref "U9") (pin "16") (pinfunction "VCC_16") (pintype "unspecified"))
    )
    (net (code "2") (name "-5v") (class "Default")
      (node (ref "C100") (pin "1") (pinfunction "1_1") (pintype "unspecified"))
      (node (ref "C109") (pin "2") (pinfunction "2_2") (pintype "unspecified"))
      (node (ref "C110") (pin "2") (pinfunction "2_2") (pintype "unspecified"))
      (node (ref "C111") (pin "2") (pinfunction "2_2") (pintype "unspecified"))
      (node (ref "C113") (pin "2") (pinfunction "2_2") (pintype "unspecified"))
      (node (ref "C114") (pin "2") (pinfunction "2_2") (pintype "unspecified"))
      (node (ref "C115") (pin "2") (pinfunction "2_2") (pintype "unspecified"))
      (node (ref "D51") (pin "1") (pinfunction "K_1") (pintype "unspecified"))
      (node (ref "D52") (pin "1") (pinfunction "K_1") (pintype "unspecified"))
      (node (ref "D53") (pin "1") (pinfunction "K_1") (pintype "unspecified"))
      (node (ref "H3") (pin "3") (pinfunction "3_3") (pintype "unspecified"))
    )
    (net (code "3") (name "/+3.3V") (class "Default")
      (node (ref "C125") (pin "2") (pinfunction "2_2") (pintype "unspecified"))
      (node (ref "C126") (pin "2") (pinfunction "2_2") (pintype "unspecified"))
      (node (ref "C127") (pin "2") (pinfunction "2_2") (pintype "unspecified"))
      (node (ref "C128") (pin "1") (pinfunction "1_1") (pintype "unspecified"))
      (node (ref "C129") (pin "1") (pinfunction "1_1") (pintype "unspecified"))
      (node (ref "C130") (pin "1") (pinfunction "1_1") (pintype "unspecified"))
      (node (ref "C133") (pin "2") (pinfunction "2_2") (pintype "input"))
      (node (ref "C134") (pin "2") (pinfunction "2_2") (pintype "input"))
      (node (ref "C135") (pin "2") (pinfunction "2_2") (pintype "input"))
      (node (ref "C96") (pin "1") (pinfunction "1_1") (pintype "unspecified"))
      (node (ref "U39") (pin "2") (pinfunction "VOUT_2") (pintype "unspecified"))
      (node (ref "U39") (pin "4") (pinfunction "VOUT_4") (pintype "unspecified"))
      (node (ref "U60") (pin "24") (pinfunction "VDD_24") (pintype "unspecified"))
      (node (ref "U60") (pin "36") (pinfunction "VDD_36") (pintype "unspecified"))
      (node (ref "U60") (pin "48") (pinfunction "VDD_48") (pintype "unspecified"))
      (node (ref "U60") (pin "9") (pinfunction "VDDA/VREF+_9") (pintype "unspecified"))
    )
    (net (code "4") (name "/+3.3v") (class "Default")
      (node (ref "C6") (pin "1") (pinfunction "1_1") (pintype "unspecified"))
      (node (ref "FPC1") (pin "8") (pinfunction "8_8") (pintype "unspecified"))
    )
    (net (code "5") (name "/+5VA") (class "Default")
      (node (ref "C1") (pin "1") (pinfunction "1_1") (pintype "input"))
      (node (ref "C103") (pin "1") (pinfunction "1_1") (pintype "unspecified"))
      (node (ref "C106") (pin "2") (pinfunction "2_2") (pintype "unspecified"))
      (node (ref "C11") (pin "1") (pinfunction "1_1") (pintype "unspecified"))
      (node (ref "C17") (pin "2") (pinfunction "2_2") (pintype "unspecified"))
      (node (ref "C19") (pin "1") (pinfunction "1_1") (pintype "input"))
      (node (ref "C2") (pin "1") (pinfunction "1_1") (pintype "input"))
      (node (ref "C3") (pin "1") (pinfunction "1_1") (pintype "input"))
      (node (ref "C4") (pin "1") (pinfunction "1_1") (pintype "input"))
      (node (ref "C5") (pin "1") (pinfunction "1_1") (pintype "unspecified"))
      (node (ref "C57") (pin "1") (pinfunction "1_1") (pintype "unspecified"))
      (node (ref "C58") (pin "2") (pinfunction "2_2") (pintype "input"))
      (node (ref "C59") (pin "2") (pinfunction "2_2") (pintype "unspecified"))
      (node (ref "C76") (pin "1") (pinfunction "1_1") (pintype "input"))
      (node (ref "C95") (pin "1") (pinfunction "1_1") (pintype "unspecified"))
      (node (ref "FPC1") (pin "1") (pinfunction "1_1") (pintype "unspecified"))
      (node (ref "H2") (pin "4") (pinfunction "4_4") (pintype "unspecified"))
      (node (ref "H3") (pin "5") (pinfunction "5_5") (pintype "unspecified"))
      (node (ref "L2") (pin "2") (pinfunction "2_2") (pintype "unspecified"))
      (node (ref "L3") (pin "1") (pinfunction "1_1") (pintype "unspecified"))
      (node (ref "R10") (pin "2") (pinfunction "2_2") (pintype "unspecified"))
      (node (ref "R101") (pin "2") (pinfunction "2_2") (pintype "unspecified"))
      (node (ref "R11") (pin "2") (pinfunction "2_2") (pintype "unspecified"))
      (node (ref "R58") (pin "1") (pinfunction "1_1") (pintype "unspecified"))
      (node (ref "R8") (pin "2") (pinfunction "2_2") (pintype "unspecified"))
      (node (ref "R9") (pin "2") (pinfunction "2_2") (pintype "unspecified"))
      (node (ref "U1") (pin "2") (pinfunction "2_2") (pintype "unspecified"))
      (node (ref "U2") (pin "2") (pinfunction "2_2") (pintype "unspecified"))
      (node (ref "U28") (pin "4") (pinfunction "FEEDBACK_4") (pintype "unspecified"))
      (node (ref "U3") (pin "2") (pinfunction "2_2") (pintype "unspecified"))
      (node (ref "U31") (pin "1") (pinfunction "B1_1") (pintype "unspecified"))
      (node (ref "U31") (pin "5") (pinfunction "VCC_5") (pintype "unspecified"))
      (node (ref "U39") (pin "3") (pinfunction "VIN_3") (pintype "unspecified"))
      (node (ref "U4") (pin "2") (pinfunction "2_2") (pintype "unspecified"))
      (node (ref "U40") (pin "1") (pinfunction "B1_1") (pintype "unspecified"))
      (node (ref "U41") (pin "1") (pinfunction "B1_1") (pintype "unspecified"))
      (node (ref "U5") (pin "1") (pinfunction "+VCC_1") (pintype "passive"))
      (node (ref "U5") (pin "9") (pinfunction "+VCC_9") (pintype "passive"))
      (node (ref "U52") (pin "7") (pinfunction "AVDD_7") (pintype "passive"))
      (node (ref "U59") (pin "31") (pinfunction "P31_31") (pintype "unspecified"))
      (node (ref "U6") (pin "1") (pinfunction "1_1") (pintype "unspecified"))
    )
    (net (code "6") (name "/+5VA_1") (class "Default")
      (node (ref "C60") (pin "1") (pinfunction "1_1") (pintype "unspecified"))
      (node (ref "C79") (pin "2") (pinfunction "2_2") (pintype "unspecified"))
      (node (ref "U32") (pin "16") (pinfunction "VCC_16") (pintype "unspecified"))
    )
    (net (code "7") (name "/+5VA_2") (class "Default")
      (node (ref "C61") (pin "1") (pinfunction "1_1") (pintype "unspecified"))
      (node (ref "C80") (pin "2") (pinfunction "2_2") (pintype "unspecified"))
      (node (ref "U42") (pin "16") (pinfunction "VCC_16") (pintype "unspecified"))
    )
    (net (code "8") (name "/+5VA_3") (class "Default")
      (node (ref "C62") (pin "1") (pinfunction "1_1") (pintype "unspecified"))
      (node (ref "C81") (pin "2") (pinfunction "2_2") (pintype "unspecified"))
      (node (ref "U33") (pin "16") (pinfunction "VCC_16") (pintype "unspecified"))
    )
    (net (code "9") (name "/+5VA_4") (class "Default")
      (node (ref "C63") (pin "1") (pinfunction "1_1") (pintype "unspecified"))
      (node (ref "C82") (pin "2") (pinfunction "2_2") (pintype "unspecified"))
      (node (ref "U43") (pin "16") (pinfunction "VCC_16") (pintype "unspecified"))
    )
    (net (code "10") (name "/+5VA_5") (class "Default")
      (node (ref "C64") (pin "1") (pinfunction "1_1") (pintype "unspecified"))
      (node (ref "C83") (pin "2") (pinfunction "2_2") (pintype "unspecified"))
      (node (ref "U34") (pin "16") (pinfunction "VCC_16") (pintype "unspecified"))
    )
    (net (code "11") (name "/+5VA_6") (class "Default")
      (node (ref "C65") (pin "1") (pinfunction "1_1") (pintype "unspecified"))
      (node (ref "C84") (pin "2") (pinfunction "2_2") (pintype "unspecified"))
      (node (ref "U44") (pin "16") (pinfunction "VCC_16") (pintype "unspecified"))
    )
    (net (code "12") (name "/+5VA_7") (class "Default")
      (node (ref "C66") (pin "1") (pinfunction "1_1") (pintype "unspecified"))
      (node (ref "C85") (pin "2") (pinfunction "2_2") (pintype "unspecified"))
      (node (ref "U35") (pin "16") (pinfunction "VCC_16") (pintype "unspecified"))
    )
    (net (code "13") (name "/+5VA_8") (class "Default")
      (node (ref "C67") (pin "1") (pinfunction "1_1") (pintype "unspecified"))
      (node (ref "C86") (pin "2") (pinfunction "2_2") (pintype "unspecified"))
      (node (ref "U45") (pin "16") (pinfunction "VCC_16") (pintype "unspecified"))
    )
    (net (code "14") (name "/+5VA_9") (class "Default")
      (node (ref "C68") (pin "1") (pinfunction "1_1") (pintype "unspecified"))
      (node (ref "C87") (pin "2") (pinfunction "2_2") (pintype "unspecified"))
      (node (ref "U36") (pin "16") (pinfunction "VCC_16") (pintype "unspecified"))
    )
    (net (code "15") (name "/+5VA_10") (class "Default")
      (node (ref "C69") (pin "1") (pinfunction "1_1") (pintype "unspecified"))
      (node (ref "C88") (pin "2") (pinfunction "2_2") (pintype "unspecified"))
      (node (ref "U46") (pin "16") (pinfunction "VCC_16") (pintype "unspecified"))
    )
    (net (code "16") (name "/+5VA_11") (class "Default")
      (node (ref "C70") (pin "1") (pinfunction "1_1") (pintype "unspecified"))
      (node (ref "C89") (pin "2") (pinfunction "2_2") (pintype "unspecified"))
      (node (ref "U37") (pin "16") (pinfunction "VCC_16") (pintype "unspecified"))
    )
    (net (code "17") (name "/+5VA_12") (class "Default")
      (node (ref "C71") (pin "1") (pinfunction "1_1") (pintype "unspecified"))
      (node (ref "C90") (pin "2") (pinfunction "2_2") (pintype "unspecified"))
      (node (ref "U47") (pin "16") (pinfunction "VCC_16") (pintype "unspecified"))
    )
    (net (code "18") (name "/+5VA_13") (class "Default")
      (node (ref "C72") (pin "1") (pinfunction "1_1") (pintype "unspecified"))
      (node (ref "C91") (pin "2") (pinfunction "2_2") (pintype "unspecified"))
      (node (ref "U38") (pin "16") (pinfunction "VCC_16") (pintype "unspecified"))
    )
    (net (code "19") (name "/+5VA_14") (class "Default")
      (node (ref "C73") (pin "1") (pinfunction "1_1") (pintype "unspecified"))
      (node (ref "C92") (pin "2") (pinfunction "2_2") (pintype "unspecified"))
      (node (ref "U48") (pin "16") (pinfunction "VCC_16") (pintype "unspecified"))
    )
    (net (code "20") (name "/+5VA_15") (class "Default")
      (node (ref "C74") (pin "1") (pinfunction "1_1") (pintype "unspecified"))
      (node (ref "C93") (pin "2") (pinfunction "2_2") (pintype "unspecified"))
      (node (ref "U49") (pin "1") (pinfunction "VDD_1") (pintype "unspecified"))
    )
    (net (code "21") (name "/+5VA_16") (class "Default")
      (node (ref "C75") (pin "1") (pinfunction "1_1") (pintype "unspecified"))
      (node (ref "C94") (pin "2") (pinfunction "2_2") (pintype "unspecified"))
      (node (ref "U53") (pin "1") (pinfunction "VDD_1") (pintype "unspecified"))
    )
    (net (code "22") (name "/+5VA_17") (class "Default")
      (node (ref "D54") (pin "1") (pinfunction "K_1") (pintype "unspecified"))
      (node (ref "U50") (pin "31") (pinfunction "VDD_31") (pintype "passive"))
    )
    (net (code "23") (name "/+5VA_18") (class "Default")
      (node (ref "D55") (pin "1") (pinfunction "K_1") (pintype "unspecified"))
      (node (ref "U51") (pin "31") (pinfunction "VDD_31") (pintype "passive"))
    )
    (net (code "24") (name "/+5VA_19") (class "Default")
      (node (ref "D56") (pin "1") (pinfunction "K_1") (pintype "unspecified"))
      (node (ref "U55") (pin "31") (pinfunction "VDD_31") (pintype "passive"))
    )
    (net (code "25") (name "/+5VD") (class "Default")
      (node (ref "C101") (pin "2") (pinfunction "2_2") (pintype "unspecified"))
      (node (ref "C102") (pin "2") (pinfunction "2_2") (pintype "unspecified"))
      (node (ref "C104") (pin "2") (pinfunction "2_2") (pintype "unspecified"))
      (node (ref "C97") (pin "1") (pinfunction "1_1") (pintype "input"))
      (node (ref "L3") (pin "2") (pinfunction "2_2") (pintype "unspecified"))
      (node (ref "U40") (pin "5") (pinfunction "VCC_5") (pintype "unspecified"))
      (node (ref "U41") (pin "5") (pinfunction "VCC_5") (pintype "unspecified"))
      (node (ref "U5") (pin "8") (pinfunction "VREF_8") (pintype "unspecified"))
      (node (ref "U52") (pin "3") (pinfunction "DVDD_3") (pintype "passive"))
      (node (ref "U7") (pin "14") (pinfunction "REF+_14") (pintype "unspecified"))
      (node (ref "U8") (pin "14") (pinfunction "REF+_14") (pintype "unspecified"))
    )
    (net (code "26") (name "/+p1 battery") (class "Default")
      (node (ref "D19") (pin "1") (pinfunction "K_1") (pintype "unspecified"))
      (node (ref "Q1") (pin "2") (pinfunction "S_2") (pintype "unspecified"))
    )
    (net (code "27") (name "/+p2_battery") (class "Default")
      (node (ref "D20") (pin "1") (pinfunction "K_1") (pintype "unspecified"))
      (node (ref "Q2") (pin "2") (pinfunction "S_2") (pintype "unspecified"))
    )
    (net (code "28") (name "/+p3_battery") (class "Default")
      (node (ref "D21") (pin "1") (pinfunction "K_1") (pintype "unspecified"))
      (node (ref "Q3") (pin "2") (pinfunction "S_2") (pintype "unspecified"))
    )
    (net (code "29") (name "/+p4_battery") (class "Default")
      (node (ref "D22") (pin "1") (pinfunction "K_1") (pintype "unspecified"))
      (node (ref "Q4") (pin "2") (pinfunction "S_2") (pintype "unspecified"))
    )
    (net (code "30") (name "/+p5_battery") (class "Default")
      (node (ref "D23") (pin "1") (pinfunction "K_1") (pintype "unspecified"))
      (node (ref "Q5") (pin "2") (pinfunction "S_2") (pintype "unspecified"))
    )
    (net (code "31") (name "/+p6_battery") (class "Default")
      (node (ref "D24") (pin "1") (pinfunction "K_1") (pintype "unspecified"))
      (node (ref "Q6") (pin "2") (pinfunction "S_2") (pintype "unspecified"))
    )
    (net (code "32") (name "/+p7_battery") (class "Default")
      (node (ref "D25") (pin "1") (pinfunction "K_1") (pintype "unspecified"))
      (node (ref "Q7") (pin "2") (pinfunction "S_2") (pintype "unspecified"))
    )
    (net (code "33") (name "/+p9_battery") (class "Default")
      (node (ref "D27") (pin "1") (pinfunction "K_1") (pintype "unspecified"))
      (node (ref "Q9") (pin "2") (pinfunction "S_2") (pintype "unspecified"))
    )
    (net (code "34") (name "/+p10_battery") (class "Default")
      (node (ref "D28") (pin "1") (pinfunction "K_1") (pintype "unspecified"))
      (node (ref "Q10") (pin "2") (pinfunction "S_2") (pintype "unspecified"))
    )
    (net (code "35") (name "/+p11_battery") (class "Default")
      (node (ref "D29") (pin "1") (pinfunction "K_1") (pintype "unspecified"))
      (node (ref "Q11") (pin "2") (pinfunction "S_2") (pintype "unspecified"))
    )
    (net (code "36") (name "/+p12_battery") (class "Default")
      (node (ref "D30") (pin "1") (pinfunction "K_1") (pintype "unspecified"))
      (node (ref "Q12") (pin "2") (pinfunction "S_2") (pintype "unspecified"))
    )
    (net (code "37") (name "/+p13_battery") (class "Default")
      (node (ref "D31") (pin "1") (pinfunction "K_1") (pintype "unspecified"))
      (node (ref "Q13") (pin "2") (pinfunction "S_2") (pintype "unspecified"))
    )
    (net (code "38") (name "/+p14 battery") (class "Default")
      (node (ref "D32") (pin "1") (pinfunction "K_1") (pintype "unspecified"))
      (node (ref "Q14") (pin "2") (pinfunction "S_2") (pintype "unspecified"))
    )
    (net (code "39") (name "/+p15_battery") (class "Default")
      (node (ref "D33") (pin "1") (pinfunction "K_1") (pintype "unspecified"))
      (node (ref "Q15") (pin "2") (pinfunction "S_2") (pintype "unspecified"))
    )
    (net (code "40") (name "/+p16_battery") (class "Default")
      (node (ref "D34") (pin "1") (pinfunction "K_1") (pintype "unspecified"))
      (node (ref "Q16") (pin "2") (pinfunction "S_2") (pintype "unspecified"))
    )
    (net (code "41") (name "/+p17_battery") (class "Default")
      (node (ref "D35") (pin "1") (pinfunction "K_1") (pintype "unspecified"))
      (node (ref "Q17") (pin "2") (pinfunction "S_2") (pintype "unspecified"))
    )
    (net (code "42") (name "/+p18_battery") (class "Default")
      (node (ref "D36") (pin "1") (pinfunction "K_1") (pintype "unspecified"))
      (node (ref "Q18") (pin "2") (pinfunction "S_2") (pintype "unspecified"))
    )
    (net (code "43") (name "/+p_8battery") (class "Default")
      (node (ref "D26") (pin "1") (pinfunction "K_1") (pintype "unspecified"))
      (node (ref "Q8") (pin "2") (pinfunction "S_2") (pintype "unspecified"))
    )
    (net (code "44") (name "/-5VA_17") (class "Default")
      (node (ref "D51") (pin "2") (pinfunction "A_2") (pintype "unspecified"))
      (node (ref "U50") (pin "25") (pinfunction "VSS_25") (pintype "passive"))
      (node (ref "U50") (pin "33") (pinfunction "EP_33") (pintype "passive"))
    )
    (net (code "45") (name "/-5VA_18") (class "Default")
      (node (ref "D52") (pin "2") (pinfunction "A_2") (pintype "unspecified"))
      (node (ref "U51") (pin "25") (pinfunction "VSS_25") (pintype "passive"))
      (node (ref "U51") (pin "33") (pinfunction "EP_33") (pintype "passive"))
    )
    (net (code "46") (name "/-5VA_19") (class "Default")
      (node (ref "D53") (pin "2") (pinfunction "A_2") (pintype "unspecified"))
      (node (ref "U55") (pin "25") (pinfunction "VSS_25") (pintype "passive"))
      (node (ref "U55") (pin "33") (pinfunction "EP_33") (pintype "passive"))
    )
    (net (code "47") (name "/-bat_sw") (class "Default")
      (node (ref "D40") (pin "2") (pinfunction "A_2") (pintype "unspecified"))
      (node (ref "D41") (pin "2") (pinfunction "A_2") (pintype "unspecified"))
      (node (ref "Q19") (pin "4") (pinfunction "S_4") (pintype "unspecified"))
      (node (ref "Q20") (pin "4") (pinfunction "S_4") (pintype "unspecified"))
      (node (ref "R61") (pin "1") (pinfunction "1_1") (pintype "unspecified"))
      (node (ref "R62") (pin "1") (pinfunction "1_1") (pintype "unspecified"))
    )
    (net (code "48") (name "/AB") (class "Default")
      (node (ref "D41") (pin "1") (pinfunction "K_1") (pintype "unspecified"))
      (node (ref "Q20") (pin "1") (pinfunction "D_1") (pintype "unspecified"))
      (node (ref "Q20") (pin "2") (pinfunction "D_2") (pintype "unspecified"))
      (node (ref "Q20") (pin "5") (pinfunction "D_5") (pintype "unspecified"))
      (node (ref "Q20") (pin "6") (pinfunction "D_6") (pintype "unspecified"))
    )
    (net (code "49") (name "/AB_E") (class "Default")
      (node (ref "D38") (pin "1") (pinfunction "K_1") (pintype "unspecified"))
      (node (ref "R60") (pin "2") (pinfunction "2_2") (pintype "unspecified"))
      (node (ref "U59") (pin "24") (pinfunction "P27_24") (pintype "unspecified"))
    )
    (net (code "50") (name "/A_INA") (class "Default")
      (node (ref "R58") (pin "2") (pinfunction "2_2") (pintype "unspecified"))
      (node (ref "U29") (pin "3") (pinfunction "ALERT_3") (pintype "unspecified"))
    )
    (net (code "51") (name "/Boot_mk") (class "Default")
      (node (ref "R99") (pin "1") (pinfunction "1_1") (pintype "input"))
      (node (ref "U60") (pin "44") (pinfunction "BOOT0_44") (pintype "unspecified"))
    )
    (net (code "52") (name "/Bt_mk") (class "Default")
      (node (ref "BT1") (pin "1") (pinfunction "+_1") (pintype "passive"))
      (node (ref "U60") (pin "1") (pinfunction "VBAT_1") (pintype "unspecified"))
    )
    (net (code "53") (name "/CLK_enc") (class "Default")
      (node (ref "H2") (pin "1") (pinfunction "1_1") (pintype "unspecified"))
      (node (ref "U59") (pin "16") (pinfunction "P19_16") (pintype "unspecified"))
    )
    (net (code "54") (name "/CM_F_1") (class "Default")
      (node (ref "C21") (pin "1") (pinfunction "1_1") (pintype "unspecified"))
      (node (ref "U10") (pin "6") (pinfunction "FILTER_6") (pintype "unspecified"))
    )
    (net (code "55") (name "/CM_F_2") (class "Default")
      (node (ref "C23") (pin "1") (pinfunction "1_1") (pintype "unspecified"))
      (node (ref "U11") (pin "6") (pinfunction "FILTER_6") (pintype "unspecified"))
    )
    (net (code "56") (name "/CM_F_3") (class "Default")
      (node (ref "C25") (pin "1") (pinfunction "1_1") (pintype "unspecified"))
      (node (ref "U12") (pin "6") (pinfunction "FILTER_6") (pintype "unspecified"))
    )
    (net (code "57") (name "/CM_F_4") (class "Default")
      (node (ref "C27") (pin "1") (pinfunction "1_1") (pintype "unspecified"))
      (node (ref "U13") (pin "6") (pinfunction "FILTER_6") (pintype "unspecified"))
    )
    (net (code "58") (name "/CM_F_5") (class "Default")
      (node (ref "C29") (pin "1") (pinfunction "1_1") (pintype "unspecified"))
      (node (ref "U14") (pin "6") (pinfunction "FILTER_6") (pintype "unspecified"))
    )
    (net (code "59") (name "/CM_F_6") (class "Default")
      (node (ref "C31") (pin "1") (pinfunction "1_1") (pintype "unspecified"))
      (node (ref "U15") (pin "6") (pinfunction "FILTER_6") (pintype "unspecified"))
    )
    (net (code "60") (name "/CM_F_7") (class "Default")
      (node (ref "C33") (pin "1") (pinfunction "1_1") (pintype "unspecified"))
      (node (ref "U16") (pin "6") (pinfunction "FILTER_6") (pintype "unspecified"))
    )
    (net (code "61") (name "/CM_F_8") (class "Default")
      (node (ref "C35") (pin "1") (pinfunction "1_1") (pintype "unspecified"))
      (node (ref "U17") (pin "6") (pinfunction "FILTER_6") (pintype "unspecified"))
    )
    (net (code "62") (name "/CM_F_9") (class "Default")
      (node (ref "C37") (pin "1") (pinfunction "1_1") (pintype "unspecified"))
      (node (ref "U18") (pin "6") (pinfunction "FILTER_6") (pintype "unspecified"))
    )
    (net (code "63") (name "/CM_F_10") (class "Default")
      (node (ref "C39") (pin "1") (pinfunction "1_1") (pintype "unspecified"))
      (node (ref "U19") (pin "6") (pinfunction "FILTER_6") (pintype "unspecified"))
    )
    (net (code "64") (name "/CM_F_11") (class "Default")
      (node (ref "C41") (pin "1") (pinfunction "1_1") (pintype "unspecified"))
      (node (ref "U20") (pin "6") (pinfunction "FILTER_6") (pintype "unspecified"))
    )
    (net (code "65") (name "/CM_F_12") (class "Default")
      (node (ref "C43") (pin "1") (pinfunction "1_1") (pintype "unspecified"))
      (node (ref "U21") (pin "6") (pinfunction "FILTER_6") (pintype "unspecified"))
    )
    (net (code "66") (name "/CM_F_13") (class "Default")
      (node (ref "C45") (pin "1") (pinfunction "1_1") (pintype "unspecified"))
      (node (ref "U22") (pin "6") (pinfunction "FILTER_6") (pintype "unspecified"))
    )
    (net (code "67") (name "/CM_F_14") (class "Default")
      (node (ref "C47") (pin "1") (pinfunction "1_1") (pintype "unspecified"))
      (node (ref "U23") (pin "6") (pinfunction "FILTER_6") (pintype "unspecified"))
    )
    (net (code "68") (name "/CM_F_15") (class "Default")
      (node (ref "C49") (pin "1") (pinfunction "1_1") (pintype "unspecified"))
      (node (ref "U24") (pin "6") (pinfunction "FILTER_6") (pintype "unspecified"))
    )
    (net (code "69") (name "/CM_F_16") (class "Default")
      (node (ref "C51") (pin "1") (pinfunction "1_1") (pintype "unspecified"))
      (node (ref "U25") (pin "6") (pinfunction "FILTER_6") (pintype "unspecified"))
    )
    (net (code "70") (name "/CM_F_17") (class "Default")
      (node (ref "C53") (pin "1") (pinfunction "1_1") (pintype "unspecified"))
      (node (ref "U26") (pin "6") (pinfunction "FILTER_6") (pintype "unspecified"))
    )
    (net (code "71") (name "/CM_F_18") (class "Default")
      (node (ref "C55") (pin "1") (pinfunction "1_1") (pintype "unspecified"))
      (node (ref "U27") (pin "6") (pinfunction "FILTER_6") (pintype "unspecified"))
    )
    (net (code "72") (name "/Circ_1_in") (class "Default")
      (node (ref "U10") (pin "1") (pinfunction "IP+_1") (pintype "unspecified"))
      (node (ref "U10") (pin "2") (pinfunction "IP+_2") (pintype "unspecified"))
    )
    (net (code "73") (name "/Circ_1_out") (class "Default")
      (node (ref "U10") (pin "3") (pinfunction "IP-_3") (pintype "unspecified"))
      (node (ref "U10") (pin "4") (pinfunction "IP-_4") (pintype "unspecified"))
    )
    (net (code "74") (name "/Circ_1_to_ADC") (class "Default")
      (node (ref "U10") (pin "7") (pinfunction "VIOUT_7") (pintype "unspecified"))
      (node (ref "U8") (pin "1") (pinfunction "AIN0_1") (pintype "unspecified"))
    )
    (net (code "75") (name "/Circ_2_in") (class "Default")
      (node (ref "U11") (pin "1") (pinfunction "IP+_1") (pintype "unspecified"))
      (node (ref "U11") (pin "2") (pinfunction "IP+_2") (pintype "unspecified"))
    )
    (net (code "76") (name "/Circ_2_out") (class "Default")
      (node (ref "U11") (pin "3") (pinfunction "IP-_3") (pintype "unspecified"))
      (node (ref "U11") (pin "4") (pinfunction "IP-_4") (pintype "unspecified"))
    )
    (net (code "77") (name "/Circ_2_to_ADC") (class "Default")
      (node (ref "U11") (pin "7") (pinfunction "VIOUT_7") (pintype "unspecified"))
      (node (ref "U8") (pin "2") (pinfunction "AIN1_2") (pintype "unspecified"))
    )
    (net (code "78") (name "/Circ_3_in") (class "Default")
      (node (ref "U12") (pin "1") (pinfunction "IP+_1") (pintype "unspecified"))
      (node (ref "U12") (pin "2") (pinfunction "IP+_2") (pintype "unspecified"))
    )
    (net (code "79") (name "/Circ_3_out") (class "Default")
      (node (ref "U12") (pin "3") (pinfunction "IP-_3") (pintype "unspecified"))
      (node (ref "U12") (pin "4") (pinfunction "IP-_4") (pintype "unspecified"))
    )
    (net (code "80") (name "/Circ_3_to_ADC") (class "Default")
      (node (ref "U12") (pin "7") (pinfunction "VIOUT_7") (pintype "unspecified"))
      (node (ref "U8") (pin "3") (pinfunction "AIN2_3") (pintype "unspecified"))
    )
    (net (code "81") (name "/Circ_4_in") (class "Default")
      (node (ref "U13") (pin "1") (pinfunction "IP+_1") (pintype "unspecified"))
      (node (ref "U13") (pin "2") (pinfunction "IP+_2") (pintype "unspecified"))
    )
    (net (code "82") (name "/Circ_4_out") (class "Default")
      (node (ref "U13") (pin "3") (pinfunction "IP-_3") (pintype "unspecified"))
      (node (ref "U13") (pin "4") (pinfunction "IP-_4") (pintype "unspecified"))
    )
    (net (code "83") (name "/Circ_4_to_ADC") (class "Default")
      (node (ref "U13") (pin "7") (pinfunction "VIOUT_7") (pintype "unspecified"))
      (node (ref "U8") (pin "4") (pinfunction "AIN3_4") (pintype "unspecified"))
    )
    (net (code "84") (name "/Circ_5_in") (class "Default")
      (node (ref "U14") (pin "1") (pinfunction "IP+_1") (pintype "unspecified"))
      (node (ref "U14") (pin "2") (pinfunction "IP+_2") (pintype "unspecified"))
    )
    (net (code "85") (name "/Circ_5_out") (class "Default")
      (node (ref "U14") (pin "3") (pinfunction "IP-_3") (pintype "unspecified"))
      (node (ref "U14") (pin "4") (pinfunction "IP-_4") (pintype "unspecified"))
    )
    (net (code "86") (name "/Circ_5_to_ADC") (class "Default")
      (node (ref "U14") (pin "7") (pinfunction "VIOUT_7") (pintype "unspecified"))
      (node (ref "U8") (pin "5") (pinfunction "AIN4_5") (pintype "unspecified"))
    )
    (net (code "87") (name "/Circ_6_in") (class "Default")
      (node (ref "U15") (pin "1") (pinfunction "IP+_1") (pintype "unspecified"))
      (node (ref "U15") (pin "2") (pinfunction "IP+_2") (pintype "unspecified"))
    )
    (net (code "88") (name "/Circ_6_out") (class "Default")
      (node (ref "U15") (pin "3") (pinfunction "IP-_3") (pintype "unspecified"))
      (node (ref "U15") (pin "4") (pinfunction "IP-_4") (pintype "unspecified"))
    )
    (net (code "89") (name "/Circ_6_to_ADC") (class "Default")
      (node (ref "U15") (pin "7") (pinfunction "VIOUT_7") (pintype "unspecified"))
      (node (ref "U8") (pin "6") (pinfunction "AIN5_6") (pintype "unspecified"))
    )
    (net (code "90") (name "/Circ_7_in") (class "Default")
      (node (ref "U16") (pin "1") (pinfunction "IP+_1") (pintype "unspecified"))
      (node (ref "U16") (pin "2") (pinfunction "IP+_2") (pintype "unspecified"))
    )
    (net (code "91") (name "/Circ_7_out") (class "Default")
      (node (ref "U16") (pin "3") (pinfunction "IP-_3") (pintype "unspecified"))
      (node (ref "U16") (pin "4") (pinfunction "IP-_4") (pintype "unspecified"))
    )
    (net (code "92") (name "/Circ_7_to_ADC") (class "Default")
      (node (ref "U16") (pin "7") (pinfunction "VIOUT_7") (pintype "unspecified"))
      (node (ref "U8") (pin "7") (pinfunction "AIN6_7") (pintype "unspecified"))
    )
    (net (code "93") (name "/Circ_8_in") (class "Default")
      (node (ref "U17") (pin "1") (pinfunction "IP+_1") (pintype "unspecified"))
      (node (ref "U17") (pin "2") (pinfunction "IP+_2") (pintype "unspecified"))
    )
    (net (code "94") (name "/Circ_8_out") (class "Default")
      (node (ref "U17") (pin "3") (pinfunction "IP-_3") (pintype "unspecified"))
      (node (ref "U17") (pin "4") (pinfunction "IP-_4") (pintype "unspecified"))
    )
    (net (code "95") (name "/Circ_8_to_ADC") (class "Default")
      (node (ref "U17") (pin "7") (pinfunction "VIOUT_7") (pintype "unspecified"))
      (node (ref "U8") (pin "8") (pinfunction "AIN7_8") (pintype "unspecified"))
    )
    (net (code "96") (name "/Circ_9_in") (class "Default")
      (node (ref "U18") (pin "1") (pinfunction "IP+_1") (pintype "unspecified"))
      (node (ref "U18") (pin "2") (pinfunction "IP+_2") (pintype "unspecified"))
    )
    (net (code "97") (name "/Circ_9_out") (class "Default")
      (node (ref "U18") (pin "3") (pinfunction "IP-_3") (pintype "unspecified"))
      (node (ref "U18") (pin "4") (pinfunction "IP-_4") (pintype "unspecified"))
    )
    (net (code "98") (name "/Circ_9_to_ADC") (class "Default")
      (node (ref "U18") (pin "7") (pinfunction "VIOUT_7") (pintype "unspecified"))
      (node (ref "U8") (pin "9") (pinfunction "AIN8_9") (pintype "unspecified"))
    )
    (net (code "99") (name "/Circ_10_in") (class "Default")
      (node (ref "U19") (pin "1") (pinfunction "IP+_1") (pintype "unspecified"))
      (node (ref "U19") (pin "2") (pinfunction "IP+_2") (pintype "unspecified"))
    )
    (net (code "100") (name "/Circ_10_out") (class "Default")
      (node (ref "U19") (pin "3") (pinfunction "IP-_3") (pintype "unspecified"))
      (node (ref "U19") (pin "4") (pinfunction "IP-_4") (pintype "unspecified"))
    )
    (net (code "101") (name "/Circ_10_to_ADC") (class "Default")
      (node (ref "U19") (pin "7") (pinfunction "VIOUT_7") (pintype "unspecified"))
      (node (ref "U8") (pin "11") (pinfunction "AIN9_11") (pintype "unspecified"))
    )
    (net (code "102") (name "/Circ_11_in") (class "Default")
      (node (ref "U20") (pin "1") (pinfunction "IP+_1") (pintype "unspecified"))
      (node (ref "U20") (pin "2") (pinfunction "IP+_2") (pintype "unspecified"))
    )
    (net (code "103") (name "/Circ_11_out") (class "Default")
      (node (ref "U20") (pin "3") (pinfunction "IP-_3") (pintype "unspecified"))
      (node (ref "U20") (pin "4") (pinfunction "IP-_4") (pintype "unspecified"))
    )
    (net (code "104") (name "/Circ_11_to_ADC") (class "Default")
      (node (ref "U20") (pin "7") (pinfunction "VIOUT_7") (pintype "unspecified"))
      (node (ref "U8") (pin "12") (pinfunction "AIN10_12") (pintype "unspecified"))
    )
    (net (code "105") (name "/Circ_12_in") (class "Default")
      (node (ref "U21") (pin "1") (pinfunction "IP+_1") (pintype "unspecified"))
      (node (ref "U21") (pin "2") (pinfunction "IP+_2") (pintype "unspecified"))
    )
    (net (code "106") (name "/Circ_12_out") (class "Default")
      (node (ref "U21") (pin "3") (pinfunction "IP-_3") (pintype "unspecified"))
      (node (ref "U21") (pin "4") (pinfunction "IP-_4") (pintype "unspecified"))
    )
    (net (code "107") (name "/Circ_12_to_ADC") (class "Default")
      (node (ref "U21") (pin "7") (pinfunction "VIOUT_7") (pintype "unspecified"))
      (node (ref "U7") (pin "1") (pinfunction "AIN0_1") (pintype "unspecified"))
    )
    (net (code "108") (name "/Circ_13_in") (class "Default")
      (node (ref "U22") (pin "1") (pinfunction "IP+_1") (pintype "unspecified"))
      (node (ref "U22") (pin "2") (pinfunction "IP+_2") (pintype "unspecified"))
    )
    (net (code "109") (name "/Circ_13_out") (class "Default")
      (node (ref "U22") (pin "3") (pinfunction "IP-_3") (pintype "unspecified"))
      (node (ref "U22") (pin "4") (pinfunction "IP-_4") (pintype "unspecified"))
    )
    (net (code "110") (name "/Circ_13_to_ADC") (class "Default")
      (node (ref "U22") (pin "7") (pinfunction "VIOUT_7") (pintype "unspecified"))
      (node (ref "U7") (pin "2") (pinfunction "AIN1_2") (pintype "unspecified"))
    )
    (net (code "111") (name "/Circ_14_in") (class "Default")
      (node (ref "U23") (pin "1") (pinfunction "IP+_1") (pintype "unspecified"))
      (node (ref "U23") (pin "2") (pinfunction "IP+_2") (pintype "unspecified"))
    )
    (net (code "112") (name "/Circ_14_out") (class "Default")
      (node (ref "U23") (pin "3") (pinfunction "IP-_3") (pintype "unspecified"))
      (node (ref "U23") (pin "4") (pinfunction "IP-_4") (pintype "unspecified"))
    )
    (net (code "113") (name "/Circ_14_to_ADC") (class "Default")
      (node (ref "U23") (pin "7") (pinfunction "VIOUT_7") (pintype "unspecified"))
      (node (ref "U7") (pin "3") (pinfunction "AIN2_3") (pintype "unspecified"))
    )
    (net (code "114") (name "/Circ_15_in") (class "Default")
      (node (ref "U24") (pin "1") (pinfunction "IP+_1") (pintype "unspecified"))
      (node (ref "U24") (pin "2") (pinfunction "IP+_2") (pintype "unspecified"))
    )
    (net (code "115") (name "/Circ_15_out") (class "Default")
      (node (ref "U24") (pin "3") (pinfunction "IP-_3") (pintype "unspecified"))
      (node (ref "U24") (pin "4") (pinfunction "IP-_4") (pintype "unspecified"))
    )
    (net (code "116") (name "/Circ_15_to_ADC") (class "Default")
      (node (ref "U24") (pin "7") (pinfunction "VIOUT_7") (pintype "unspecified"))
      (node (ref "U7") (pin "4") (pinfunction "AIN3_4") (pintype "unspecified"))
    )
    (net (code "117") (name "/Circ_16_in") (class "Default")
      (node (ref "U25") (pin "1") (pinfunction "IP+_1") (pintype "unspecified"))
      (node (ref "U25") (pin "2") (pinfunction "IP+_2") (pintype "unspecified"))
    )
    (net (code "118") (name "/Circ_16_out") (class "Default")
      (node (ref "U25") (pin "3") (pinfunction "IP-_3") (pintype "unspecified"))
      (node (ref "U25") (pin "4") (pinfunction "IP-_4") (pintype "unspecified"))
    )
    (net (code "119") (name "/Circ_16_to_ADC") (class "Default")
      (node (ref "U25") (pin "7") (pinfunction "VIOUT_7") (pintype "unspecified"))
      (node (ref "U7") (pin "5") (pinfunction "AIN4_5") (pintype "unspecified"))
    )
    (net (code "120") (name "/Circ_17_in") (class "Default")
      (node (ref "U26") (pin "1") (pinfunction "IP+_1") (pintype "unspecified"))
      (node (ref "U26") (pin "2") (pinfunction "IP+_2") (pintype "unspecified"))
    )
    (net (code "121") (name "/Circ_17_out") (class "Default")
      (node (ref "U26") (pin "3") (pinfunction "IP-_3") (pintype "unspecified"))
      (node (ref "U26") (pin "4") (pinfunction "IP-_4") (pintype "unspecified"))
    )
    (net (code "122") (name "/Circ_17_to_ADC") (class "Default")
      (node (ref "U26") (pin "7") (pinfunction "VIOUT_7") (pintype "unspecified"))
      (node (ref "U7") (pin "6") (pinfunction "AIN5_6") (pintype "unspecified"))
    )
    (net (code "123") (name "/Circ_18_in") (class "Default")
      (node (ref "U27") (pin "1") (pinfunction "IP+_1") (pintype "unspecified"))
      (node (ref "U27") (pin "2") (pinfunction "IP+_2") (pintype "unspecified"))
    )
    (net (code "124") (name "/Circ_18_out") (class "Default")
      (node (ref "U27") (pin "3") (pinfunction "IP-_3") (pintype "unspecified"))
      (node (ref "U27") (pin "4") (pinfunction "IP-_4") (pintype "unspecified"))
    )
    (net (code "125") (name "/Circ_18_to_ADC") (class "Default")
      (node (ref "U27") (pin "7") (pinfunction "VIOUT_7") (pintype "unspecified"))
      (node (ref "U7") (pin "7") (pinfunction "AIN6_7") (pintype "unspecified"))
    )
    (net (code "126") (name "/DSP_DC") (class "Default")
      (node (ref "FPC1") (pin "5") (pinfunction "5_5") (pintype "unspecified"))
      (node (ref "R7") (pin "1") (pinfunction "1_1") (pintype "input"))
    )
    (net (code "127") (name "/DSP_DC_R") (class "Default")
      (node (ref "R7") (pin "2") (pinfunction "2_2") (pintype "input"))
      (node (ref "U59") (pin "14") (pinfunction "P17_14") (pintype "unspecified"))
    )
    (net (code "128") (name "/DSP_RST") (class "Default")
      (node (ref "FPC1") (pin "4") (pinfunction "4_4") (pintype "unspecified"))
      (node (ref "R6") (pin "1") (pinfunction "1_1") (pintype "input"))
    )
    (net (code "129") (name "/DSP_RST_R") (class "Default")
      (node (ref "R6") (pin "2") (pinfunction "2_2") (pintype "input"))
      (node (ref "U59") (pin "13") (pinfunction "P16_13") (pintype "unspecified"))
    )
    (net (code "130") (name "/DT_enc") (class "Default")
      (node (ref "H2") (pin "2") (pinfunction "2_2") (pintype "unspecified"))
      (node (ref "U59") (pin "17") (pinfunction "P20_17") (pintype "unspecified"))
    )
    (net (code "131") (name "/E_RG#") (class "Default")
      (node (ref "R50") (pin "1") (pinfunction "1_1") (pintype "input"))
      (node (ref "U9") (pin "13") (pinfunction "OE#_13") (pintype "unspecified"))
    )
    (net (code "132") (name "/Ens8_1") (class "Default")
      (node (ref "R80") (pin "1") (pinfunction "1_1") (pintype "unspecified"))
      (node (ref "U32") (pin "6") (pinfunction "E#_6") (pintype "unspecified"))
    )
    (net (code "133") (name "/Ens8_1_R") (class "Default")
      (node (ref "R80") (pin "2") (pinfunction "2_2") (pintype "unspecified"))
      (node (ref "U57") (pin "15") (pinfunction "P18_15") (pintype "unspecified"))
    )
    (net (code "134") (name "/Ens8_2") (class "Default")
      (node (ref "R81") (pin "1") (pinfunction "1_1") (pintype "unspecified"))
      (node (ref "U42") (pin "6") (pinfunction "E#_6") (pintype "unspecified"))
    )
    (net (code "135") (name "/Ens8_2_R") (class "Default")
      (node (ref "R81") (pin "2") (pinfunction "2_2") (pintype "unspecified"))
      (node (ref "U57") (pin "16") (pinfunction "P19_16") (pintype "unspecified"))
    )
    (net (code "136") (name "/Ens8_3") (class "Default")
      (node (ref "R82") (pin "1") (pinfunction "1_1") (pintype "unspecified"))
      (node (ref "U33") (pin "6") (pinfunction "E#_6") (pintype "unspecified"))
    )
    (net (code "137") (name "/Ens8_3_R") (class "Default")
      (node (ref "R82") (pin "2") (pinfunction "2_2") (pintype "unspecified"))
      (node (ref "U57") (pin "17") (pinfunction "P20_17") (pintype "unspecified"))
    )
    (net (code "138") (name "/Ens8_4") (class "Default")
      (node (ref "R83") (pin "1") (pinfunction "1_1") (pintype "unspecified"))
      (node (ref "U43") (pin "6") (pinfunction "E#_6") (pintype "unspecified"))
    )
    (net (code "139") (name "/Ens8_4_R") (class "Default")
      (node (ref "R83") (pin "2") (pinfunction "2_2") (pintype "unspecified"))
      (node (ref "U57") (pin "18") (pinfunction "P21_18") (pintype "unspecified"))
    )
    (net (code "140") (name "/Ens8_5") (class "Default")
      (node (ref "R84") (pin "1") (pinfunction "1_1") (pintype "unspecified"))
      (node (ref "U34") (pin "6") (pinfunction "E#_6") (pintype "unspecified"))
    )
    (net (code "141") (name "/Ens8_5_R") (class "Default")
      (node (ref "R84") (pin "2") (pinfunction "2_2") (pintype "unspecified"))
      (node (ref "U57") (pin "19") (pinfunction "P22_19") (pintype "unspecified"))
    )
    (net (code "142") (name "/Ens8_6") (class "Default")
      (node (ref "R85") (pin "1") (pinfunction "1_1") (pintype "unspecified"))
      (node (ref "U44") (pin "6") (pinfunction "E#_6") (pintype "unspecified"))
    )
    (net (code "143") (name "/Ens8_6_R") (class "Default")
      (node (ref "R85") (pin "2") (pinfunction "2_2") (pintype "unspecified"))
      (node (ref "U57") (pin "20") (pinfunction "P23_20") (pintype "unspecified"))
    )
    (net (code "144") (name "/Ens8_7") (class "Default")
      (node (ref "R86") (pin "1") (pinfunction "1_1") (pintype "unspecified"))
      (node (ref "U35") (pin "6") (pinfunction "E#_6") (pintype "unspecified"))
    )
    (net (code "145") (name "/Ens8_7_R") (class "Default")
      (node (ref "R86") (pin "2") (pinfunction "2_2") (pintype "unspecified"))
      (node (ref "U57") (pin "21") (pinfunction "P24_21") (pintype "unspecified"))
    )
    (net (code "146") (name "/Ens8_8") (class "Default")
      (node (ref "R87") (pin "1") (pinfunction "1_1") (pintype "unspecified"))
      (node (ref "U45") (pin "6") (pinfunction "E#_6") (pintype "unspecified"))
    )
    (net (code "147") (name "/Ens8_8_R") (class "Default")
      (node (ref "R87") (pin "2") (pinfunction "2_2") (pintype "unspecified"))
      (node (ref "U57") (pin "22") (pinfunction "P25_22") (pintype "unspecified"))
    )
    (net (code "148") (name "/Ens8_9") (class "Default")
      (node (ref "R88") (pin "1") (pinfunction "1_1") (pintype "unspecified"))
      (node (ref "U36") (pin "6") (pinfunction "E#_6") (pintype "unspecified"))
    )
    (net (code "149") (name "/Ens8_9_R") (class "Default")
      (node (ref "R88") (pin "2") (pinfunction "2_2") (pintype "unspecified"))
      (node (ref "U57") (pin "23") (pinfunction "P26_23") (pintype "unspecified"))
    )
    (net (code "150") (name "/Ens8_10") (class "Default")
      (node (ref "R89") (pin "1") (pinfunction "1_1") (pintype "unspecified"))
      (node (ref "U46") (pin "6") (pinfunction "E#_6") (pintype "unspecified"))
    )
    (net (code "151") (name "/Ens8_10_R") (class "Default")
      (node (ref "R89") (pin "2") (pinfunction "2_2") (pintype "unspecified"))
      (node (ref "U57") (pin "24") (pinfunction "P27_24") (pintype "unspecified"))
    )
    (net (code "152") (name "/Ens8_11") (class "Default")
      (node (ref "R90") (pin "1") (pinfunction "1_1") (pintype "unspecified"))
      (node (ref "U37") (pin "6") (pinfunction "E#_6") (pintype "unspecified"))
    )
    (net (code "153") (name "/Ens8_11_R") (class "Default")
      (node (ref "R90") (pin "2") (pinfunction "2_2") (pintype "unspecified"))
      (node (ref "U57") (pin "25") (pinfunction "P28_25") (pintype "unspecified"))
    )
    (net (code "154") (name "/Ens8_12") (class "Default")
      (node (ref "R91") (pin "1") (pinfunction "1_1") (pintype "unspecified"))
      (node (ref "U47") (pin "6") (pinfunction "E#_6") (pintype "unspecified"))
    )
    (net (code "155") (name "/Ens8_12_R") (class "Default")
      (node (ref "R91") (pin "2") (pinfunction "2_2") (pintype "unspecified"))
      (node (ref "U57") (pin "27") (pinfunction "P29_27") (pintype "unspecified"))
    )
    (net (code "156") (name "/Ens8_13") (class "Default")
      (node (ref "R92") (pin "1") (pinfunction "1_1") (pintype "unspecified"))
      (node (ref "U38") (pin "6") (pinfunction "E#_6") (pintype "unspecified"))
    )
    (net (code "157") (name "/Ens8_13_R") (class "Default")
      (node (ref "R92") (pin "2") (pinfunction "2_2") (pintype "unspecified"))
      (node (ref "U57") (pin "29") (pinfunction "P30_29") (pintype "unspecified"))
    )
    (net (code "158") (name "/Ens8_14") (class "Default")
      (node (ref "R93") (pin "1") (pinfunction "1_1") (pintype "unspecified"))
      (node (ref "U48") (pin "6") (pinfunction "E#_6") (pintype "unspecified"))
    )
    (net (code "159") (name "/Ens8_14_R") (class "Default")
      (node (ref "R93") (pin "2") (pinfunction "2_2") (pintype "unspecified"))
      (node (ref "U57") (pin "31") (pinfunction "P31_31") (pintype "unspecified"))
    )
    (net (code "160") (name "/Ens16_B+") (class "Default")
      (node (ref "R78") (pin "1") (pinfunction "1_1") (pintype "unspecified"))
      (node (ref "U50") (pin "16") (pinfunction "EN_16") (pintype "unspecified"))
    )
    (net (code "161") (name "/Ens16_B-") (class "Default")
      (node (ref "R77") (pin "1") (pinfunction "1_1") (pintype "unspecified"))
      (node (ref "U51") (pin "16") (pinfunction "EN_16") (pintype "unspecified"))
    )
    (net (code "162") (name "/Ens16_B_R") (class "Default")
      (node (ref "R77") (pin "2") (pinfunction "2_2") (pintype "unspecified"))
      (node (ref "R78") (pin "2") (pinfunction "2_2") (pintype "unspecified"))
      (node (ref "R79") (pin "2") (pinfunction "2_2") (pintype "unspecified"))
      (node (ref "U56") (pin "22") (pinfunction "P25_22") (pintype "unspecified"))
    )
    (net (code "163") (name "/Ens16_B{slash}") (class "Default")
      (node (ref "R79") (pin "1") (pinfunction "1_1") (pintype "unspecified"))
      (node (ref "U55") (pin "16") (pinfunction "EN_16") (pintype "unspecified"))
    )
    (net (code "164") (name "/Ens16_V+") (class "Default")
      (node (ref "R75") (pin "1") (pinfunction "1_1") (pintype "unspecified"))
      (node (ref "U49") (pin "18") (pinfunction "EN_18") (pintype "unspecified"))
    )
    (net (code "165") (name "/Ens16_V-") (class "Default")
      (node (ref "R76") (pin "1") (pinfunction "1_1") (pintype "unspecified"))
      (node (ref "U53") (pin "18") (pinfunction "EN_18") (pintype "unspecified"))
    )
    (net (code "166") (name "/Ens16_V_R") (class "Default")
      (node (ref "R75") (pin "2") (pinfunction "2_2") (pintype "unspecified"))
      (node (ref "R76") (pin "2") (pinfunction "2_2") (pintype "unspecified"))
      (node (ref "U56") (pin "21") (pinfunction "P24_21") (pintype "unspecified"))
    )
    (net (code "167") (name "/InS1_1") (class "Default")
      (node (ref "U32") (pin "11") (pinfunction "S1_11") (pintype "unspecified"))
      (node (ref "U58") (pin "32") (pinfunction "P4_32") (pintype "unspecified"))
    )
    (net (code "168") (name "/InS1_2") (class "Default")
      (node (ref "U32") (pin "10") (pinfunction "S2_10") (pintype "unspecified"))
      (node (ref "U58") (pin "30") (pinfunction "P5_30") (pintype "unspecified"))
    )
    (net (code "169") (name "/InS1_3") (class "Default")
      (node (ref "U32") (pin "9") (pinfunction "S3_9") (pintype "unspecified"))
      (node (ref "U58") (pin "28") (pinfunction "P6_28") (pintype "unspecified"))
    )
    (net (code "170") (name "/InS2_1") (class "Default")
      (node (ref "U42") (pin "11") (pinfunction "S1_11") (pintype "unspecified"))
      (node (ref "U58") (pin "26") (pinfunction "P7_26") (pintype "unspecified"))
    )
    (net (code "171") (name "/InS2_2") (class "Default")
      (node (ref "U42") (pin "10") (pinfunction "S2_10") (pintype "unspecified"))
      (node (ref "U58") (pin "5") (pinfunction "P8_5") (pintype "unspecified"))
    )
    (net (code "172") (name "/InS2_3") (class "Default")
      (node (ref "U42") (pin "9") (pinfunction "S3_9") (pintype "unspecified"))
      (node (ref "U58") (pin "7") (pinfunction "P9_7") (pintype "unspecified"))
    )
    (net (code "173") (name "/InS3_1") (class "Default")
      (node (ref "U33") (pin "11") (pinfunction "S1_11") (pintype "unspecified"))
      (node (ref "U58") (pin "9") (pinfunction "P10_9") (pintype "unspecified"))
    )
    (net (code "174") (name "/InS3_2") (class "Default")
      (node (ref "U33") (pin "10") (pinfunction "S2_10") (pintype "unspecified"))
      (node (ref "U58") (pin "11") (pinfunction "P11_11") (pintype "unspecified"))
    )
    (net (code "175") (name "/InS3_3") (class "Default")
      (node (ref "U33") (pin "9") (pinfunction "S3_9") (pintype "unspecified"))
      (node (ref "U58") (pin "6") (pinfunction "P12_6") (pintype "unspecified"))
    )
    (net (code "176") (name "/InS4_1") (class "Default")
      (node (ref "U43") (pin "11") (pinfunction "S1_11") (pintype "unspecified"))
      (node (ref "U58") (pin "8") (pinfunction "P13_8") (pintype "unspecified"))
    )
    (net (code "177") (name "/InS4_2") (class "Default")
      (node (ref "U43") (pin "10") (pinfunction "S2_10") (pintype "unspecified"))
      (node (ref "U58") (pin "10") (pinfunction "P14_10") (pintype "unspecified"))
    )
    (net (code "178") (name "/InS4_3") (class "Default")
      (node (ref "U43") (pin "9") (pinfunction "S3_9") (pintype "unspecified"))
      (node (ref "U58") (pin "12") (pinfunction "P15_12") (pintype "unspecified"))
    )
    (net (code "179") (name "/InS5_1") (class "Default")
      (node (ref "U34") (pin "11") (pinfunction "S1_11") (pintype "unspecified"))
      (node (ref "U58") (pin "13") (pinfunction "P16_13") (pintype "unspecified"))
    )
    (net (code "180") (name "/InS5_2") (class "Default")
      (node (ref "U34") (pin "10") (pinfunction "S2_10") (pintype "unspecified"))
      (node (ref "U58") (pin "14") (pinfunction "P17_14") (pintype "unspecified"))
    )
    (net (code "181") (name "/InS5_3") (class "Default")
      (node (ref "U34") (pin "9") (pinfunction "S3_9") (pintype "unspecified"))
      (node (ref "U58") (pin "15") (pinfunction "P18_15") (pintype "unspecified"))
    )
    (net (code "182") (name "/InS6_1") (class "Default")
      (node (ref "U44") (pin "11") (pinfunction "S1_11") (pintype "unspecified"))
      (node (ref "U58") (pin "16") (pinfunction "P19_16") (pintype "unspecified"))
    )
    (net (code "183") (name "/InS6_2") (class "Default")
      (node (ref "U44") (pin "10") (pinfunction "S2_10") (pintype "unspecified"))
      (node (ref "U58") (pin "17") (pinfunction "P20_17") (pintype "unspecified"))
    )
    (net (code "184") (name "/InS6_3") (class "Default")
      (node (ref "U44") (pin "9") (pinfunction "S3_9") (pintype "unspecified"))
      (node (ref "U58") (pin "18") (pinfunction "P21_18") (pintype "unspecified"))
    )
    (net (code "185") (name "/InS7_1") (class "Default")
      (node (ref "U35") (pin "11") (pinfunction "S1_11") (pintype "unspecified"))
      (node (ref "U58") (pin "19") (pinfunction "P22_19") (pintype "unspecified"))
    )
    (net (code "186") (name "/InS7_2") (class "Default")
      (node (ref "U35") (pin "10") (pinfunction "S2_10") (pintype "unspecified"))
      (node (ref "U58") (pin "20") (pinfunction "P23_20") (pintype "unspecified"))
    )
    (net (code "187") (name "/InS7_3") (class "Default")
      (node (ref "U35") (pin "9") (pinfunction "S3_9") (pintype "unspecified"))
      (node (ref "U58") (pin "21") (pinfunction "P24_21") (pintype "unspecified"))
    )
    (net (code "188") (name "/InS8_1") (class "Default")
      (node (ref "U45") (pin "11") (pinfunction "S1_11") (pintype "unspecified"))
      (node (ref "U58") (pin "22") (pinfunction "P25_22") (pintype "unspecified"))
    )
    (net (code "189") (name "/InS8_2") (class "Default")
      (node (ref "U45") (pin "10") (pinfunction "S2_10") (pintype "unspecified"))
      (node (ref "U58") (pin "23") (pinfunction "P26_23") (pintype "unspecified"))
    )
    (net (code "190") (name "/InS8_3") (class "Default")
      (node (ref "U45") (pin "9") (pinfunction "S3_9") (pintype "unspecified"))
      (node (ref "U58") (pin "24") (pinfunction "P27_24") (pintype "unspecified"))
    )
    (net (code "191") (name "/InS9_1") (class "Default")
      (node (ref "U36") (pin "11") (pinfunction "S1_11") (pintype "unspecified"))
      (node (ref "U58") (pin "25") (pinfunction "P28_25") (pintype "unspecified"))
    )
    (net (code "192") (name "/InS9_2") (class "Default")
      (node (ref "U36") (pin "10") (pinfunction "S2_10") (pintype "unspecified"))
      (node (ref "U58") (pin "27") (pinfunction "P29_27") (pintype "unspecified"))
    )
    (net (code "193") (name "/InS9_3") (class "Default")
      (node (ref "U36") (pin "9") (pinfunction "S3_9") (pintype "unspecified"))
      (node (ref "U58") (pin "29") (pinfunction "P30_29") (pintype "unspecified"))
    )
    (net (code "194") (name "/InS10_1") (class "Default")
      (node (ref "U46") (pin "11") (pinfunction "S1_11") (pintype "unspecified"))
      (node (ref "U58") (pin "31") (pinfunction "P31_31") (pintype "unspecified"))
    )
    (net (code "195") (name "/InS10_2") (class "Default")
      (node (ref "U46") (pin "10") (pinfunction "S2_10") (pintype "unspecified"))
      (node (ref "U57") (pin "32") (pinfunction "P4_32") (pintype "unspecified"))
    )
    (net (code "196") (name "/InS10_3") (class "Default")
      (node (ref "U46") (pin "9") (pinfunction "S3_9") (pintype "unspecified"))
      (node (ref "U57") (pin "30") (pinfunction "P5_30") (pintype "unspecified"))
    )
    (net (code "197") (name "/InS11_1") (class "Default")
      (node (ref "U37") (pin "11") (pinfunction "S1_11") (pintype "unspecified"))
      (node (ref "U57") (pin "28") (pinfunction "P6_28") (pintype "unspecified"))
    )
    (net (code "198") (name "/InS11_2") (class "Default")
      (node (ref "U37") (pin "10") (pinfunction "S2_10") (pintype "unspecified"))
      (node (ref "U57") (pin "26") (pinfunction "P7_26") (pintype "unspecified"))
    )
    (net (code "199") (name "/InS11_3") (class "Default")
      (node (ref "U37") (pin "9") (pinfunction "S3_9") (pintype "unspecified"))
      (node (ref "U57") (pin "5") (pinfunction "P8_5") (pintype "unspecified"))
    )
    (net (code "200") (name "/InS12_1") (class "Default")
      (node (ref "U47") (pin "11") (pinfunction "S1_11") (pintype "unspecified"))
      (node (ref "U57") (pin "7") (pinfunction "P9_7") (pintype "unspecified"))
    )
    (net (code "201") (name "/InS12_2") (class "Default")
      (node (ref "U47") (pin "10") (pinfunction "S2_10") (pintype "unspecified"))
      (node (ref "U57") (pin "9") (pinfunction "P10_9") (pintype "unspecified"))
    )
    (net (code "202") (name "/InS12_3") (class "Default")
      (node (ref "U47") (pin "9") (pinfunction "S3_9") (pintype "unspecified"))
      (node (ref "U57") (pin "11") (pinfunction "P11_11") (pintype "unspecified"))
    )
    (net (code "203") (name "/InS13_1") (class "Default")
      (node (ref "U38") (pin "11") (pinfunction "S1_11") (pintype "unspecified"))
      (node (ref "U57") (pin "6") (pinfunction "P12_6") (pintype "unspecified"))
    )
    (net (code "204") (name "/InS13_2") (class "Default")
      (node (ref "U38") (pin "10") (pinfunction "S2_10") (pintype "unspecified"))
      (node (ref "U57") (pin "8") (pinfunction "P13_8") (pintype "unspecified"))
    )
    (net (code "205") (name "/InS13_3") (class "Default")
      (node (ref "U38") (pin "9") (pinfunction "S3_9") (pintype "unspecified"))
      (node (ref "U57") (pin "10") (pinfunction "P14_10") (pintype "unspecified"))
    )
    (net (code "206") (name "/InS14_1") (class "Default")
      (node (ref "U48") (pin "11") (pinfunction "S1_11") (pintype "unspecified"))
      (node (ref "U57") (pin "12") (pinfunction "P15_12") (pintype "unspecified"))
    )
    (net (code "207") (name "/InS14_2") (class "Default")
      (node (ref "U48") (pin "10") (pinfunction "S2_10") (pintype "unspecified"))
      (node (ref "U57") (pin "13") (pinfunction "P16_13") (pintype "unspecified"))
    )
    (net (code "208") (name "/InS14_3") (class "Default")
      (node (ref "U48") (pin "9") (pinfunction "S3_9") (pintype "unspecified"))
      (node (ref "U57") (pin "14") (pinfunction "P17_14") (pintype "unspecified"))
    )
    (net (code "209") (name "/InS16B+_1") (class "Default")
      (node (ref "U50") (pin "15") (pinfunction "A0_15") (pintype "unspecified"))
      (node (ref "U56") (pin "32") (pinfunction "P4_32") (pintype "unspecified"))
    )
    (net (code "210") (name "/InS16B+_2") (class "Default")
      (node (ref "U50") (pin "14") (pinfunction "A1_14") (pintype "unspecified"))
      (node (ref "U56") (pin "30") (pinfunction "P5_30") (pintype "unspecified"))
    )
    (net (code "211") (name "/InS16B+_3") (class "Default")
      (node (ref "U50") (pin "11") (pinfunction "A2_11") (pintype "unspecified"))
      (node (ref "U56") (pin "28") (pinfunction "P6_28") (pintype "unspecified"))
    )
    (net (code "212") (name "/InS16B+_4") (class "Default")
      (node (ref "U50") (pin "10") (pinfunction "A3_10") (pintype "unspecified"))
      (node (ref "U56") (pin "26") (pinfunction "P7_26") (pintype "unspecified"))
    )
    (net (code "213") (name "/InS16B-_1") (class "Default")
      (node (ref "U51") (pin "15") (pinfunction "A0_15") (pintype "unspecified"))
      (node (ref "U56") (pin "5") (pinfunction "P8_5") (pintype "unspecified"))
    )
    (net (code "214") (name "/InS16B-_2") (class "Default")
      (node (ref "U51") (pin "14") (pinfunction "A1_14") (pintype "unspecified"))
      (node (ref "U56") (pin "7") (pinfunction "P9_7") (pintype "unspecified"))
    )
    (net (code "215") (name "/InS16B-_3") (class "Default")
      (node (ref "U51") (pin "11") (pinfunction "A2_11") (pintype "unspecified"))
      (node (ref "U56") (pin "9") (pinfunction "P10_9") (pintype "unspecified"))
    )
    (net (code "216") (name "/InS16B-_4") (class "Default")
      (node (ref "U51") (pin "10") (pinfunction "A3_10") (pintype "unspecified"))
      (node (ref "U56") (pin "11") (pinfunction "P11_11") (pintype "unspecified"))
    )
    (net (code "217") (name "/InS16B{slash}_1") (class "Default")
      (node (ref "U55") (pin "15") (pinfunction "A0_15") (pintype "unspecified"))
      (node (ref "U56") (pin "6") (pinfunction "P12_6") (pintype "unspecified"))
    )
    (net (code "218") (name "/InS16B{slash}_2") (class "Default")
      (node (ref "U55") (pin "14") (pinfunction "A1_14") (pintype "unspecified"))
      (node (ref "U56") (pin "8") (pinfunction "P13_8") (pintype "unspecified"))
    )
    (net (code "219") (name "/InS16B{slash}_3") (class "Default")
      (node (ref "U55") (pin "11") (pinfunction "A2_11") (pintype "unspecified"))
      (node (ref "U56") (pin "10") (pinfunction "P14_10") (pintype "unspecified"))
    )
    (net (code "220") (name "/InS16B{slash}_4") (class "Default")
      (node (ref "U55") (pin "10") (pinfunction "A3_10") (pintype "unspecified"))
      (node (ref "U56") (pin "12") (pinfunction "P15_12") (pintype "unspecified"))
    )
    (net (code "221") (name "/InS16V+_1") (class "Default")
      (node (ref "U49") (pin "17") (pinfunction "A0_17") (pintype "unspecified"))
      (node (ref "U56") (pin "13") (pinfunction "P16_13") (pintype "unspecified"))
    )
    (net (code "222") (name "/InS16V+_2") (class "Default")
      (node (ref "U49") (pin "16") (pinfunction "A1_16") (pintype "unspecified"))
      (node (ref "U56") (pin "14") (pinfunction "P17_14") (pintype "unspecified"))
    )
    (net (code "223") (name "/InS16V+_3") (class "Default")
      (node (ref "U49") (pin "15") (pinfunction "A2_15") (pintype "unspecified"))
      (node (ref "U56") (pin "15") (pinfunction "P18_15") (pintype "unspecified"))
    )
    (net (code "224") (name "/InS16V+_4") (class "Default")
      (node (ref "U49") (pin "14") (pinfunction "A3_14") (pintype "unspecified"))
      (node (ref "U56") (pin "16") (pinfunction "P19_16") (pintype "unspecified"))
    )
    (net (code "225") (name "/InS16V-_1") (class "Default")
      (node (ref "U53") (pin "17") (pinfunction "A0_17") (pintype "unspecified"))
      (node (ref "U56") (pin "17") (pinfunction "P20_17") (pintype "unspecified"))
    )
    (net (code "226") (name "/InS16V-_2") (class "Default")
      (node (ref "U53") (pin "16") (pinfunction "A1_16") (pintype "unspecified"))
      (node (ref "U56") (pin "18") (pinfunction "P21_18") (pintype "unspecified"))
    )
    (net (code "227") (name "/InS16V-_3") (class "Default")
      (node (ref "U53") (pin "15") (pinfunction "A2_15") (pintype "unspecified"))
      (node (ref "U56") (pin "19") (pinfunction "P22_19") (pintype "unspecified"))
    )
    (net (code "228") (name "/InS16V-_4") (class "Default")
      (node (ref "U53") (pin "14") (pinfunction "A3_14") (pintype "unspecified"))
      (node (ref "U56") (pin "20") (pinfunction "P23_20") (pintype "unspecified"))
    )
    (net (code "229") (name "/Iset1") (class "Default")
      (node (ref "R98") (pin "2") (pinfunction "2_2") (pintype "unspecified"))
      (node (ref "U58") (pin "1") (pinfunction "ISET_1") (pintype "unspecified"))
    )
    (net (code "230") (name "/Iset2") (class "Default")
      (node (ref "R102") (pin "2") (pinfunction "2_2") (pintype "unspecified"))
      (node (ref "U57") (pin "1") (pinfunction "ISET_1") (pintype "unspecified"))
    )
    (net (code "231") (name "/Iset3") (class "Default")
      (node (ref "R103") (pin "2") (pinfunction "2_2") (pintype "unspecified"))
      (node (ref "U56") (pin "1") (pinfunction "ISET_1") (pintype "unspecified"))
    )
    (net (code "232") (name "/Iset4") (class "Default")
      (node (ref "R104") (pin "2") (pinfunction "2_2") (pintype "unspecified"))
      (node (ref "U59") (pin "1") (pinfunction "ISET_1") (pintype "unspecified"))
    )
    (net (code "233") (name "/NRST") (class "Default")
      (node (ref "C141") (pin "2") (pinfunction "2_2") (pintype "unspecified"))
      (node (ref "KEY2") (pin "2") (pinfunction "2_2") (pintype "unspecified"))
      (node (ref "U60") (pin "7") (pinfunction "NRST_7") (pintype "unspecified"))
    )
    (net (code "234") (name "/OSC_In") (class "Default")
      (node (ref "C131") (pin "1") (pinfunction "1_1") (pintype "unspecified"))
      (node (ref "U60") (pin "5") (pinfunction "PH0-OSC_IN_5") (pintype "unspecified"))
      (node (ref "U61") (pin "P$1") (pinfunction "PIN1_P$1") (pintype "unspecified"))
    )
    (net (code "235") (name "/OSC_In32") (class "Default")
      (node (ref "C140") (pin "1") (pinfunction "1_1") (pintype "unspecified"))
      (node (ref "U60") (pin "3") (pinfunction "PC14-OSC32_IN_3") (pintype "unspecified"))
      (node (ref "U62") (pin "P$1") (pinfunction "PIN1_P$1") (pintype "unspecified"))
    )
    (net (code "236") (name "/OSC_OUT") (class "Default")
      (node (ref "C132") (pin "1") (pinfunction "1_1") (pintype "unspecified"))
      (node (ref "U60") (pin "6") (pinfunction "PH1-OSC_OUT_6") (pintype "unspecified"))
      (node (ref "U61") (pin "P$2") (pinfunction "PIN2_P$2") (pintype "unspecified"))
    )
    (net (code "237") (name "/OSC_OUT32") (class "Default")
      (node (ref "C139") (pin "1") (pinfunction "1_1") (pintype "unspecified"))
      (node (ref "U60") (pin "4") (pinfunction "PC15-OSC32_OUT_4") (pintype "unspecified"))
      (node (ref "U62") (pin "P$2") (pinfunction "PIN2_P$2") (pintype "unspecified"))
    )
    (net (code "238") (name "/OutS16B+") (class "Default")
      (node (ref "C13") (pin "1") (pinfunction "1_1") (pintype "unspecified"))
      (node (ref "R63") (pin "1") (pinfunction "1_1") (pintype "unspecified"))
    )
    (net (code "239") (name "/OutS16V+") (class "Default")
      (node (ref "R95") (pin "1") (pinfunction "1_1") (pintype "unspecified"))
      (node (ref "U49") (pin "28") (pinfunction "D_28") (pintype "unspecified"))
    )
    (net (code "240") (name "/OutS16V-") (class "Default")
      (node (ref "R94") (pin "1") (pinfunction "1_1") (pintype "unspecified"))
      (node (ref "U53") (pin "28") (pinfunction "D_28") (pintype "unspecified"))
    )
    (net (code "241") (name "/OutS16_B+") (class "Default")
      (node (ref "C14") (pin "1") (pinfunction "1_1") (pintype "unspecified"))
      (node (ref "D43") (pin "1") (pinfunction "C_1") (pintype "unspecified"))
      (node (ref "D45") (pin "1") (pinfunction "C_1") (pintype "unspecified"))
      (node (ref "Q22") (pin "3") (pinfunction "S2_3") (pintype "unspecified"))
      (node (ref "R69") (pin "1") (pinfunction "1_1") (pintype "unspecified"))
      (node (ref "U50") (pin "29") (pinfunction "D_29") (pintype "unspecified"))
    )
    (net (code "242") (name "/OutS16_B-") (class "Default")
      (node (ref "C15") (pin "2") (pinfunction "2_2") (pintype "unspecified"))
      (node (ref "D44") (pin "2") (pinfunction "A_2") (pintype "unspecified"))
      (node (ref "D46") (pin "2") (pinfunction "A_2") (pintype "unspecified"))
      (node (ref "Q22") (pin "1") (pinfunction "S1_1") (pintype "unspecified"))
      (node (ref "R70") (pin "1") (pinfunction "1_1") (pintype "unspecified"))
      (node (ref "U51") (pin "29") (pinfunction "D_29") (pintype "unspecified"))
    )
    (net (code "243") (name "/OutS16_B{slash}") (class "Default")
      (node (ref "C14") (pin "2") (pinfunction "2_2") (pintype "unspecified"))
      (node (ref "C15") (pin "1") (pinfunction "1_1") (pintype "unspecified"))
      (node (ref "L1") (pin "1") (pinfunction "1_1") (pintype "unspecified"))
      (node (ref "R64") (pin "1") (pinfunction "1_1") (pintype "unspecified"))
      (node (ref "U55") (pin "29") (pinfunction "D_29") (pintype "unspecified"))
    )
    (net (code "244") (name "/Outs8_1") (class "Default")
      (node (ref "U32") (pin "3") (pinfunction "Z_3") (pintype "unspecified"))
      (node (ref "U49") (pin "19") (pinfunction "S1_19") (pintype "unspecified"))
      (node (ref "U50") (pin "17") (pinfunction "S1_17") (pintype "unspecified"))
      (node (ref "U51") (pin "17") (pinfunction "S1_17") (pintype "unspecified"))
      (node (ref "U53") (pin "19") (pinfunction "S1_19") (pintype "unspecified"))
      (node (ref "U55") (pin "17") (pinfunction "S1_17") (pintype "unspecified"))
    )
    (net (code "245") (name "/Outs8_2") (class "Default")
      (node (ref "U42") (pin "3") (pinfunction "Z_3") (pintype "unspecified"))
      (node (ref "U49") (pin "20") (pinfunction "S2_20") (pintype "unspecified"))
      (node (ref "U50") (pin "18") (pinfunction "S2_18") (pintype "unspecified"))
      (node (ref "U51") (pin "18") (pinfunction "S2_18") (pintype "unspecified"))
      (node (ref "U53") (pin "20") (pinfunction "S2_20") (pintype "unspecified"))
      (node (ref "U55") (pin "18") (pinfunction "S2_18") (pintype "unspecified"))
    )
    (net (code "246") (name "/Outs8_3") (class "Default")
      (node (ref "U33") (pin "3") (pinfunction "Z_3") (pintype "unspecified"))
      (node (ref "U49") (pin "21") (pinfunction "S3_21") (pintype "unspecified"))
      (node (ref "U50") (pin "19") (pinfunction "S3_19") (pintype "unspecified"))
      (node (ref "U51") (pin "19") (pinfunction "S3_19") (pintype "unspecified"))
      (node (ref "U53") (pin "21") (pinfunction "S3_21") (pintype "unspecified"))
      (node (ref "U55") (pin "19") (pinfunction "S3_19") (pintype "unspecified"))
    )
    (net (code "247") (name "/Outs8_4") (class "Default")
      (node (ref "U43") (pin "3") (pinfunction "Z_3") (pintype "unspecified"))
      (node (ref "U49") (pin "22") (pinfunction "S4_22") (pintype "unspecified"))
      (node (ref "U50") (pin "20") (pinfunction "S4_20") (pintype "unspecified"))
      (node (ref "U51") (pin "20") (pinfunction "S4_20") (pintype "unspecified"))
      (node (ref "U53") (pin "22") (pinfunction "S4_22") (pintype "unspecified"))
      (node (ref "U55") (pin "20") (pinfunction "S4_20") (pintype "unspecified"))
    )
    (net (code "248") (name "/Outs8_5") (class "Default")
      (node (ref "U34") (pin "3") (pinfunction "Z_3") (pintype "unspecified"))
      (node (ref "U49") (pin "23") (pinfunction "S5_23") (pintype "unspecified"))
      (node (ref "U50") (pin "21") (pinfunction "S5_21") (pintype "unspecified"))
      (node (ref "U51") (pin "21") (pinfunction "S5_21") (pintype "unspecified"))
      (node (ref "U53") (pin "23") (pinfunction "S5_23") (pintype "unspecified"))
      (node (ref "U55") (pin "21") (pinfunction "S5_21") (pintype "unspecified"))
    )
    (net (code "249") (name "/Outs8_6") (class "Default")
      (node (ref "U44") (pin "3") (pinfunction "Z_3") (pintype "unspecified"))
      (node (ref "U49") (pin "24") (pinfunction "S6_24") (pintype "unspecified"))
      (node (ref "U50") (pin "22") (pinfunction "S6_22") (pintype "unspecified"))
      (node (ref "U51") (pin "22") (pinfunction "S6_22") (pintype "unspecified"))
      (node (ref "U53") (pin "24") (pinfunction "S6_24") (pintype "unspecified"))
      (node (ref "U55") (pin "22") (pinfunction "S6_22") (pintype "unspecified"))
    )
    (net (code "250") (name "/Outs8_7") (class "Default")
      (node (ref "U35") (pin "3") (pinfunction "Z_3") (pintype "unspecified"))
      (node (ref "U49") (pin "25") (pinfunction "S7_25") (pintype "unspecified"))
      (node (ref "U50") (pin "23") (pinfunction "S7_23") (pintype "unspecified"))
      (node (ref "U51") (pin "23") (pinfunction "S7_23") (pintype "unspecified"))
      (node (ref "U53") (pin "25") (pinfunction "S7_25") (pintype "unspecified"))
      (node (ref "U55") (pin "23") (pinfunction "S7_23") (pintype "unspecified"))
    )
    (net (code "251") (name "/Outs8_8") (class "Default")
      (node (ref "U45") (pin "3") (pinfunction "Z_3") (pintype "unspecified"))
      (node (ref "U49") (pin "26") (pinfunction "S8_26") (pintype "unspecified"))
      (node (ref "U50") (pin "24") (pinfunction "S8_24") (pintype "unspecified"))
      (node (ref "U51") (pin "24") (pinfunction "S8_24") (pintype "unspecified"))
      (node (ref "U53") (pin "26") (pinfunction "S8_26") (pintype "unspecified"))
      (node (ref "U55") (pin "24") (pinfunction "S8_24") (pintype "unspecified"))
    )
    (net (code "252") (name "/Outs8_9") (class "Default")
      (node (ref "U36") (pin "3") (pinfunction "Z_3") (pintype "unspecified"))
      (node (ref "U49") (pin "11") (pinfunction "S9_11") (pintype "unspecified"))
      (node (ref "U50") (pin "8") (pinfunction "S9_8") (pintype "unspecified"))
      (node (ref "U51") (pin "8") (pinfunction "S9_8") (pintype "unspecified"))
      (node (ref "U53") (pin "11") (pinfunction "S9_11") (pintype "unspecified"))
      (node (ref "U55") (pin "8") (pinfunction "S9_8") (pintype "unspecified"))
    )
    (net (code "253") (name "/Outs8_10") (class "Default")
      (node (ref "U46") (pin "3") (pinfunction "Z_3") (pintype "unspecified"))
      (node (ref "U49") (pin "10") (pinfunction "S10_10") (pintype "unspecified"))
      (node (ref "U50") (pin "7") (pinfunction "S10_7") (pintype "unspecified"))
      (node (ref "U51") (pin "7") (pinfunction "S10_7") (pintype "unspecified"))
      (node (ref "U53") (pin "10") (pinfunction "S10_10") (pintype "unspecified"))
      (node (ref "U55") (pin "7") (pinfunction "S10_7") (pintype "unspecified"))
    )
    (net (code "254") (name "/Outs8_11") (class "Default")
      (node (ref "U37") (pin "3") (pinfunction "Z_3") (pintype "unspecified"))
      (node (ref "U49") (pin "9") (pinfunction "S11_9") (pintype "unspecified"))
      (node (ref "U50") (pin "6") (pinfunction "S11_6") (pintype "unspecified"))
      (node (ref "U51") (pin "6") (pinfunction "S11_6") (pintype "unspecified"))
      (node (ref "U53") (pin "9") (pinfunction "S11_9") (pintype "unspecified"))
      (node (ref "U55") (pin "6") (pinfunction "S11_6") (pintype "unspecified"))
    )
    (net (code "255") (name "/Outs8_12") (class "Default")
      (node (ref "U47") (pin "3") (pinfunction "Z_3") (pintype "unspecified"))
      (node (ref "U49") (pin "8") (pinfunction "S12_8") (pintype "unspecified"))
      (node (ref "U50") (pin "5") (pinfunction "S12_5") (pintype "unspecified"))
      (node (ref "U51") (pin "5") (pinfunction "S12_5") (pintype "unspecified"))
      (node (ref "U53") (pin "8") (pinfunction "S12_8") (pintype "unspecified"))
      (node (ref "U55") (pin "5") (pinfunction "S12_5") (pintype "unspecified"))
    )
    (net (code "256") (name "/Outs8_13") (class "Default")
      (node (ref "U38") (pin "3") (pinfunction "Z_3") (pintype "unspecified"))
      (node (ref "U49") (pin "7") (pinfunction "S13_7") (pintype "unspecified"))
      (node (ref "U50") (pin "4") (pinfunction "S13_4") (pintype "unspecified"))
      (node (ref "U51") (pin "4") (pinfunction "S13_4") (pintype "unspecified"))
      (node (ref "U53") (pin "7") (pinfunction "S13_7") (pintype "unspecified"))
      (node (ref "U55") (pin "4") (pinfunction "S13_4") (pintype "unspecified"))
    )
    (net (code "257") (name "/Outs8_14") (class "Default")
      (node (ref "U48") (pin "3") (pinfunction "Z_3") (pintype "unspecified"))
      (node (ref "U49") (pin "6") (pinfunction "S14_6") (pintype "unspecified"))
      (node (ref "U50") (pin "3") (pinfunction "S14_3") (pintype "unspecified"))
      (node (ref "U51") (pin "3") (pinfunction "S14_3") (pintype "unspecified"))
      (node (ref "U53") (pin "6") (pinfunction "S14_6") (pintype "unspecified"))
      (node (ref "U55") (pin "3") (pinfunction "S14_3") (pintype "unspecified"))
    )
    (net (code "258") (name "/PB") (class "Default")
      (node (ref "C13") (pin "2") (pinfunction "2_2") (pintype "unspecified"))
      (node (ref "D39") (pin "1") (pinfunction "K_1") (pintype "unspecified"))
      (node (ref "D40") (pin "1") (pinfunction "K_1") (pintype "unspecified"))
      (node (ref "Q19") (pin "1") (pinfunction "D_1") (pintype "unspecified"))
      (node (ref "Q19") (pin "2") (pinfunction "D_2") (pintype "unspecified"))
      (node (ref "Q19") (pin "5") (pinfunction "D_5") (pintype "unspecified"))
      (node (ref "Q19") (pin "6") (pinfunction "D_6") (pintype "unspecified"))
      (node (ref "Q21") (pin "3") (pinfunction "D_3") (pintype "unspecified"))
    )
    (net (code "259") (name "/PB_E") (class "Default")
      (node (ref "D37") (pin "1") (pinfunction "K_1") (pintype "unspecified"))
      (node (ref "R59") (pin "2") (pinfunction "2_2") (pintype "unspecified"))
      (node (ref "U59") (pin "23") (pinfunction "P26_23") (pintype "unspecified"))
    )
    (net (code "260") (name "/PC13") (class "Default")
      (node (ref "C137") (pin "2") (pinfunction "2_2") (pintype "unspecified"))
      (node (ref "KEY1") (pin "2") (pinfunction "2_2") (pintype "unspecified"))
      (node (ref "R101") (pin "1") (pinfunction "1_1") (pintype "unspecified"))
      (node (ref "U60") (pin "2") (pinfunction "PC13-ANTI_TAMP_2") (pintype "unspecified"))
    )
    (net (code "261") (name "/PWM_DOWN") (class "Default")
      (node (ref "U41") (pin "6") (pinfunction "S_6") (pintype "unspecified"))
    )
    (net (code "262") (name "/PWM_Down") (class "Default")
      (node (ref "U60") (pin "13") (pinfunction "PA3_13") (pintype "unspecified"))
    )
    (net (code "263") (name "/PWM_UP") (class "Default")
      (node (ref "U40") (pin "6") (pinfunction "S_6") (pintype "unspecified"))
    )
    (net (code "264") (name "/PWM_Up") (class "Default")
      (node (ref "U60") (pin "12") (pinfunction "PA2_12") (pintype "unspecified"))
    )
    (net (code "265") (name "/SPI1_MISO") (class "Default")
      (node (ref "U5") (pin "12") (pinfunction "DOUT_12") (pintype "unspecified"))
      (node (ref "U58") (pin "4") (pinfunction "DOUT_4") (pintype "unspecified"))
      (node (ref "U60") (pin "16") (pinfunction "PA6_16") (pintype "unspecified"))
    )
    (net (code "266") (name "/SPI1_MOSI") (class "Default")
      (node (ref "U5") (pin "14") (pinfunction "DIN_14") (pintype "unspecified"))
      (node (ref "U58") (pin "34") (pinfunction "DIN_34") (pintype "unspecified"))
      (node (ref "U60") (pin "17") (pinfunction "PA7_17") (pintype "unspecified"))
    )
    (net (code "267") (name "/SPI1_NSS1") (class "Default")
      (node (ref "U58") (pin "35") (pinfunction "CS#_35") (pintype "unspecified"))
      (node (ref "U60") (pin "14") (pinfunction "PA4_14") (pintype "unspecified"))
    )
    (net (code "268") (name "/SPI1_NSS2") (class "Default")
      (node (ref "U5") (pin "15") (pinfunction "CS_15") (pintype "unspecified"))
      (node (ref "U60") (pin "30") (pinfunction "PA9_30") (pintype "unspecified"))
    )
    (net (code "269") (name "/SPI1_SCK") (class "Default")
      (node (ref "U5") (pin "16") (pinfunction "DCLK_16") (pintype "unspecified"))
      (node (ref "U58") (pin "33") (pinfunction "SCLK_33") (pintype "unspecified"))
      (node (ref "U60") (pin "15") (pinfunction "PA5_15") (pintype "unspecified"))
    )
    (net (code "270") (name "/SPI2_CSK") (class "Default")
      (node (ref "U7") (pin "15") (pinfunction "CS#_15") (pintype "unspecified"))
      (node (ref "U8") (pin "15") (pinfunction "CS#_15") (pintype "unspecified"))
    )
    (net (code "271") (name "/SPI2_MISO") (class "Default")
      (node (ref "U57") (pin "4") (pinfunction "DOUT_4") (pintype "unspecified"))
      (node (ref "U60") (pin "27") (pinfunction "PB14_27") (pintype "unspecified"))
      (node (ref "U7") (pin "16") (pinfunction "DATA_OUT_16") (pintype "unspecified"))
      (node (ref "U8") (pin "16") (pinfunction "DATA_OUT_16") (pintype "unspecified"))
    )
    (net (code "272") (name "/SPI2_MOSI") (class "Default")
      (node (ref "U57") (pin "34") (pinfunction "DIN_34") (pintype "unspecified"))
      (node (ref "U60") (pin "28") (pinfunction "PB15_28") (pintype "unspecified"))
      (node (ref "U7") (pin "17") (pinfunction "DATA_INPUT_17") (pintype "unspecified"))
      (node (ref "U8") (pin "17") (pinfunction "DATA_INPUT_17") (pintype "unspecified"))
    )
    (net (code "273") (name "/SPI2_NSS1") (class "Default")
      (node (ref "U57") (pin "35") (pinfunction "CS#_35") (pintype "unspecified"))
      (node (ref "U60") (pin "46") (pinfunction "PB9_46") (pintype "unspecified"))
    )
    (net (code "274") (name "/SPI2_NSS2") (class "Default")
      (node (ref "U60") (pin "29") (pinfunction "PA8_29") (pintype "unspecified"))
      (node (ref "U7") (pin "18") (pinfunction "I/O_CLOCK_18") (pintype "unspecified"))
    )
    (net (code "275") (name "/SPI2_NSS3") (class "Default")
      (node (ref "U60") (pin "42") (pinfunction "PB6_42") (pintype "unspecified"))
      (node (ref "U8") (pin "18") (pinfunction "I/O_CLOCK_18") (pintype "unspecified"))
    )
    (net (code "276") (name "/SPI2_SCK") (class "Default")
      (node (ref "U57") (pin "33") (pinfunction "SCLK_33") (pintype "unspecified"))
      (node (ref "U60") (pin "21") (pinfunction "PB10_21") (pintype "unspecified"))
    )
    (net (code "277") (name "/SPI3_MISO") (class "Default")
      (node (ref "U52") (pin "1") (pinfunction "DOUT_1") (pintype "unspecified"))
      (node (ref "U56") (pin "4") (pinfunction "DOUT_4") (pintype "unspecified"))
      (node (ref "U60") (pin "40") (pinfunction "PB4_40") (pintype "unspecified"))
    )
    (net (code "278") (name "/SPI3_MOSI") (class "Default")
      (node (ref "U56") (pin "34") (pinfunction "DIN_34") (pintype "unspecified"))
      (node (ref "U60") (pin "41") (pinfunction "PB5_41") (pintype "unspecified"))
    )
    (net (code "279") (name "/SPI3_NSS1") (class "Default")
      (node (ref "U56") (pin "35") (pinfunction "CS#_35") (pintype "unspecified"))
      (node (ref "U60") (pin "38") (pinfunction "PA15_38") (pintype "unspecified"))
    )
    (net (code "280") (name "/SPI3_NSS2") (class "Default")
      (node (ref "U52") (pin "10") (pinfunction "SCLK_10") (pintype "unspecified"))
      (node (ref "U60") (pin "10") (pinfunction "PA0-WKUP_10") (pintype "unspecified"))
      (node (ref "U60") (pin "43") (pinfunction "PB7_43") (pintype "unspecified"))
    )
    (net (code "281") (name "/SPI3_SCK") (class "Default")
      (node (ref "U52") (pin "9") (pinfunction "CS#_9") (pintype "unspecified"))
      (node (ref "U56") (pin "33") (pinfunction "SCLK_33") (pintype "unspecified"))
      (node (ref "U60") (pin "39") (pinfunction "PB3_39") (pintype "unspecified"))
    )
    (net (code "282") (name "/SPI4_MISO") (class "Default")
      (node (ref "U29") (pin "4") (pinfunction "MISO_4") (pintype "unspecified"))
      (node (ref "U59") (pin "4") (pinfunction "DOUT_4") (pintype "unspecified"))
      (node (ref "U60") (pin "32") (pinfunction "PA11_32") (pintype "unspecified"))
    )
    (net (code "283") (name "/SPI4_MOSI") (class "Default")
      (node (ref "U29") (pin "2") (pinfunction "MOSI_2") (pintype "unspecified"))
      (node (ref "U59") (pin "34") (pinfunction "DIN_34") (pintype "unspecified"))
      (node (ref "U60") (pin "11") (pinfunction "PA1_11") (pintype "unspecified"))
    )
    (net (code "284") (name "/SPI4_NSS1") (class "Default")
      (node (ref "U59") (pin "35") (pinfunction "CS#_35") (pintype "unspecified"))
      (node (ref "U60") (pin "25") (pinfunction "PB12_25") (pintype "unspecified"))
    )
    (net (code "285") (name "/SPI4_NSS2") (class "Default")
      (node (ref "U29") (pin "1") (pinfunction "CS_1") (pintype "unspecified"))
      (node (ref "U60") (pin "45") (pinfunction "PB8_45") (pintype "unspecified"))
    )
    (net (code "286") (name "/SPI4_SCK") (class "Default")
      (node (ref "U29") (pin "5") (pinfunction "SCL_5") (pintype "unspecified"))
      (node (ref "U59") (pin "33") (pinfunction "SCLK_33") (pintype "unspecified"))
      (node (ref "U60") (pin "26") (pinfunction "PB13_26") (pintype "unspecified"))
    )
    (net (code "287") (name "/SPI5_MISO") (class "Default")
      (node (ref "FPC1") (pin "13") (pinfunction "13_13") (pintype "unspecified"))
      (node (ref "FPC1") (pin "9") (pinfunction "9_9") (pintype "unspecified"))
      (node (ref "U60") (pin "33") (pinfunction "PA12_33") (pintype "unspecified"))
    )
    (net (code "288") (name "/SPI5_MOSI") (class "Default")
      (node (ref "FPC1") (pin "12") (pinfunction "12_12") (pintype "unspecified"))
      (node (ref "FPC1") (pin "6") (pinfunction "6_6") (pintype "unspecified"))
      (node (ref "U60") (pin "31") (pinfunction "PA10_31") (pintype "unspecified"))
    )
    (net (code "289") (name "/SPI5_NSS1") (class "Default")
      (node (ref "FPC1") (pin "3") (pinfunction "3_3") (pintype "unspecified"))
      (node (ref "U60") (pin "19") (pinfunction "PB1_19") (pintype "unspecified"))
    )
    (net (code "290") (name "/SPI5_NSS2") (class "Default")
      (node (ref "FPC1") (pin "11") (pinfunction "11_11") (pintype "unspecified"))
      (node (ref "U60") (pin "20") (pinfunction "PB2_20") (pintype "unspecified"))
    )
    (net (code "291") (name "/SPI5_SCK") (class "Default")
      (node (ref "FPC1") (pin "10") (pinfunction "10_10") (pintype "unspecified"))
      (node (ref "FPC1") (pin "7") (pinfunction "7_7") (pintype "unspecified"))
      (node (ref "U60") (pin "18") (pinfunction "PB0_18") (pintype "unspecified"))
    )
    (net (code "292") (name "/SW_enc") (class "Default")
      (node (ref "H2") (pin "3") (pinfunction "3_3") (pintype "unspecified"))
      (node (ref "U59") (pin "18") (pinfunction "P21_18") (pintype "unspecified"))
    )
    (net (code "293") (name "/SYS_JTCK-SWCLK") (class "Default")
      (node (ref "U6") (pin "2") (pinfunction "2_2") (pintype "unspecified"))
      (node (ref "U60") (pin "37") (pinfunction "PA14_37") (pintype "unspecified"))
    )
    (net (code "294") (name "/SYS_JTMS-SWD") (class "Default")
      (node (ref "U6") (pin "3") (pinfunction "3_3") (pintype "unspecified"))
      (node (ref "U60") (pin "34") (pinfunction "PA13_34") (pintype "unspecified"))
    )
    (net (code "295") (name "/T_IRQ") (class "Default")
      (node (ref "FPC1") (pin "14") (pinfunction "14_14") (pintype "unspecified"))
      (node (ref "R5") (pin "1") (pinfunction "1_1") (pintype "input"))
    )
    (net (code "296") (name "/T_IRQ_R") (class "Default")
      (node (ref "R5") (pin "2") (pinfunction "2_2") (pintype "input"))
      (node (ref "U59") (pin "15") (pinfunction "P18_15") (pintype "unspecified"))
    )
    (net (code "297") (name "/V+1") (class "Default")
      (node (ref "C123") (pin "2") (pinfunction "2_2") (pintype "unspecified"))
      (node (ref "U58") (pin "36") (pinfunction "V+_36") (pintype "unspecified"))
    )
    (net (code "298") (name "/V+2") (class "Default")
      (node (ref "C136") (pin "2") (pinfunction "2_2") (pintype "unspecified"))
      (node (ref "U57") (pin "36") (pinfunction "V+_36") (pintype "unspecified"))
    )
    (net (code "299") (name "/V+3") (class "Default")
      (node (ref "C138") (pin "2") (pinfunction "2_2") (pintype "unspecified"))
      (node (ref "U56") (pin "36") (pinfunction "V+_36") (pintype "unspecified"))
    )
    (net (code "300") (name "/V+4") (class "Default")
      (node (ref "C142") (pin "2") (pinfunction "2_2") (pintype "unspecified"))
      (node (ref "U59") (pin "36") (pinfunction "V+_36") (pintype "unspecified"))
    )
    (net (code "301") (name "/V1_1") (class "Default")
      (node (ref "U48") (pin "1") (pinfunction "Y4_1") (pintype "unspecified"))
      (node (ref "U49") (pin "4") (pinfunction "S16_4") (pintype "unspecified"))
      (node (ref "U49") (pin "5") (pinfunction "S15_5") (pintype "unspecified"))
      (node (ref "U50") (pin "1") (pinfunction "S16_1") (pintype "unspecified"))
      (node (ref "U50") (pin "2") (pinfunction "S15_2") (pintype "unspecified"))
      (node (ref "U51") (pin "1") (pinfunction "S16_1") (pintype "unspecified"))
      (node (ref "U51") (pin "2") (pinfunction "S15_2") (pintype "unspecified"))
      (node (ref "U53") (pin "4") (pinfunction "S16_4") (pintype "unspecified"))
      (node (ref "U53") (pin "5") (pinfunction "S15_5") (pintype "unspecified"))
      (node (ref "U55") (pin "1") (pinfunction "S16_1") (pintype "unspecified"))
      (node (ref "U55") (pin "2") (pinfunction "S15_2") (pintype "unspecified"))
    )
    (net (code "302") (name "/V1_2") (class "Default")
      (node (ref "U32") (pin "13") (pinfunction "Y0_13") (pintype "unspecified"))
    )
    (net (code "303") (name "/V1_3") (class "Default")
      (node (ref "U33") (pin "15") (pinfunction "Y2_15") (pintype "unspecified"))
    )
    (net (code "304") (name "/V1_4") (class "Default")
      (node (ref "U34") (pin "1") (pinfunction "Y4_1") (pintype "unspecified"))
    )
    (net (code "305") (name "/V1_5") (class "Default")
      (node (ref "U35") (pin "2") (pinfunction "Y6_2") (pintype "unspecified"))
    )
    (net (code "306") (name "/V1_6") (class "Default")
      (node (ref "U46") (pin "13") (pinfunction "Y0_13") (pintype "unspecified"))
    )
    (net (code "307") (name "/V1_7") (class "Default")
      (node (ref "U47") (pin "15") (pinfunction "Y2_15") (pintype "unspecified"))
    )
    (net (code "308") (name "/V2_2") (class "Default")
      (node (ref "U32") (pin "14") (pinfunction "Y1_14") (pintype "unspecified"))
    )
    (net (code "309") (name "/V2_3") (class "Default")
      (node (ref "U33") (pin "12") (pinfunction "Y3_12") (pintype "unspecified"))
    )
    (net (code "310") (name "/V2_4") (class "Default")
      (node (ref "U34") (pin "5") (pinfunction "Y5_5") (pintype "unspecified"))
    )
    (net (code "311") (name "/V2_5") (class "Default")
      (node (ref "U35") (pin "4") (pinfunction "Y7_4") (pintype "unspecified"))
    )
    (net (code "312") (name "/V2_6") (class "Default")
      (node (ref "U46") (pin "14") (pinfunction "Y1_14") (pintype "unspecified"))
    )
    (net (code "313") (name "/V2_7") (class "Default")
      (node (ref "U47") (pin "12") (pinfunction "Y3_12") (pintype "unspecified"))
    )
    (net (code "314") (name "/V3_2") (class "Default")
      (node (ref "U32") (pin "15") (pinfunction "Y2_15") (pintype "unspecified"))
    )
    (net (code "315") (name "/V3_3") (class "Default")
      (node (ref "U33") (pin "1") (pinfunction "Y4_1") (pintype "unspecified"))
    )
    (net (code "316") (name "/V3_4") (class "Default")
      (node (ref "U34") (pin "2") (pinfunction "Y6_2") (pintype "unspecified"))
    )
    (net (code "317") (name "/V3_5") (class "Default")
      (node (ref "U45") (pin "13") (pinfunction "Y0_13") (pintype "unspecified"))
    )
    (net (code "318") (name "/V3_6") (class "Default")
      (node (ref "U46") (pin "15") (pinfunction "Y2_15") (pintype "unspecified"))
    )
    (net (code "319") (name "/V3_7") (class "Default")
      (node (ref "U47") (pin "1") (pinfunction "Y4_1") (pintype "unspecified"))
    )
    (net (code "320") (name "/V4_2") (class "Default")
      (node (ref "U32") (pin "12") (pinfunction "Y3_12") (pintype "unspecified"))
    )
    (net (code "321") (name "/V4_3") (class "Default")
      (node (ref "U33") (pin "5") (pinfunction "Y5_5") (pintype "unspecified"))
    )
    (net (code "322") (name "/V4_4") (class "Default")
      (node (ref "U34") (pin "4") (pinfunction "Y7_4") (pintype "unspecified"))
    )
    (net (code "323") (name "/V4_5") (class "Default")
      (node (ref "U45") (pin "14") (pinfunction "Y1_14") (pintype "unspecified"))
    )
    (net (code "324") (name "/V4_6") (class "Default")
      (node (ref "U46") (pin "12") (pinfunction "Y3_12") (pintype "unspecified"))
    )
    (net (code "325") (name "/V4_7") (class "Default")
      (node (ref "U47") (pin "5") (pinfunction "Y5_5") (pintype "unspecified"))
    )
    (net (code "326") (name "/V5_2") (class "Default")
      (node (ref "U32") (pin "1") (pinfunction "Y4_1") (pintype "unspecified"))
    )
    (net (code "327") (name "/V5_3") (class "Default")
      (node (ref "U33") (pin "2") (pinfunction "Y6_2") (pintype "unspecified"))
    )
    (net (code "328") (name "/V5_4") (class "Default")
      (node (ref "U44") (pin "13") (pinfunction "Y0_13") (pintype "unspecified"))
    )
    (net (code "329") (name "/V5_5") (class "Default")
      (node (ref "U45") (pin "15") (pinfunction "Y2_15") (pintype "unspecified"))
    )
    (net (code "330") (name "/V5_6") (class "Default")
      (node (ref "U46") (pin "1") (pinfunction "Y4_1") (pintype "unspecified"))
    )
    (net (code "331") (name "/V5_7") (class "Default")
      (node (ref "U47") (pin "2") (pinfunction "Y6_2") (pintype "unspecified"))
    )
    (net (code "332") (name "/V6_2") (class "Default")
      (node (ref "U32") (pin "5") (pinfunction "Y5_5") (pintype "unspecified"))
    )
    (net (code "333") (name "/V6_3") (class "Default")
      (node (ref "U33") (pin "4") (pinfunction "Y7_4") (pintype "unspecified"))
    )
    (net (code "334") (name "/V6_4") (class "Default")
      (node (ref "U44") (pin "14") (pinfunction "Y1_14") (pintype "unspecified"))
    )
    (net (code "335") (name "/V6_5") (class "Default")
      (node (ref "U45") (pin "12") (pinfunction "Y3_12") (pintype "unspecified"))
    )
    (net (code "336") (name "/V6_6") (class "Default")
      (node (ref "U46") (pin "5") (pinfunction "Y5_5") (pintype "unspecified"))
    )
    (net (code "337") (name "/V6_7") (class "Default")
      (node (ref "U47") (pin "4") (pinfunction "Y7_4") (pintype "unspecified"))
    )
    (net (code "338") (name "/V7_2") (class "Default")
      (node (ref "U32") (pin "2") (pinfunction "Y6_2") (pintype "unspecified"))
    )
    (net (code "339") (name "/V7_3") (class "Default")
      (node (ref "U43") (pin "13") (pinfunction "Y0_13") (pintype "unspecified"))
    )
    (net (code "340") (name "/V7_4") (class "Default")
      (node (ref "U44") (pin "15") (pinfunction "Y2_15") (pintype "unspecified"))
    )
    (net (code "341") (name "/V7_5") (class "Default")
      (node (ref "U45") (pin "1") (pinfunction "Y4_1") (pintype "unspecified"))
    )
    (net (code "342") (name "/V7_6") (class "Default")
      (node (ref "U46") (pin "2") (pinfunction "Y6_2") (pintype "unspecified"))
    )
    (net (code "343") (name "/V7_7") (class "Default")
      (node (ref "U38") (pin "13") (pinfunction "Y0_13") (pintype "unspecified"))
    )
    (net (code "344") (name "/V8_2") (class "Default")
      (node (ref "U32") (pin "4") (pinfunction "Y7_4") (pintype "unspecified"))
    )
    (net (code "345") (name "/V8_3") (class "Default")
      (node (ref "U43") (pin "14") (pinfunction "Y1_14") (pintype "unspecified"))
    )
    (net (code "346") (name "/V8_4") (class "Default")
      (node (ref "U44") (pin "12") (pinfunction "Y3_12") (pintype "unspecified"))
    )
    (net (code "347") (name "/V8_5") (class "Default")
      (node (ref "U45") (pin "5") (pinfunction "Y5_5") (pintype "unspecified"))
    )
    (net (code "348") (name "/V8_6") (class "Default")
      (node (ref "U46") (pin "4") (pinfunction "Y7_4") (pintype "unspecified"))
    )
    (net (code "349") (name "/V8_7") (class "Default")
      (node (ref "U38") (pin "14") (pinfunction "Y1_14") (pintype "unspecified"))
    )
    (net (code "350") (name "/V9_2") (class "Default")
      (node (ref "U42") (pin "13") (pinfunction "Y0_13") (pintype "unspecified"))
    )
    (net (code "351") (name "/V9_3") (class "Default")
      (node (ref "U43") (pin "15") (pinfunction "Y2_15") (pintype "unspecified"))
    )
    (net (code "352") (name "/V9_4") (class "Default")
      (node (ref "U44") (pin "1") (pinfunction "Y4_1") (pintype "unspecified"))
    )
    (net (code "353") (name "/V9_5") (class "Default")
      (node (ref "U45") (pin "2") (pinfunction "Y6_2") (pintype "unspecified"))
    )
    (net (code "354") (name "/V9_6") (class "Default")
      (node (ref "U37") (pin "13") (pinfunction "Y0_13") (pintype "unspecified"))
    )
    (net (code "355") (name "/V9_7") (class "Default")
      (node (ref "U38") (pin "15") (pinfunction "Y2_15") (pintype "unspecified"))
    )
    (net (code "356") (name "/V10_2") (class "Default")
      (node (ref "U42") (pin "14") (pinfunction "Y1_14") (pintype "unspecified"))
    )
    (net (code "357") (name "/V10_3") (class "Default")
      (node (ref "U43") (pin "12") (pinfunction "Y3_12") (pintype "unspecified"))
    )
    (net (code "358") (name "/V10_4") (class "Default")
      (node (ref "U44") (pin "5") (pinfunction "Y5_5") (pintype "unspecified"))
    )
    (net (code "359") (name "/V10_5") (class "Default")
      (node (ref "U45") (pin "4") (pinfunction "Y7_4") (pintype "unspecified"))
    )
    (net (code "360") (name "/V10_6") (class "Default")
      (node (ref "U37") (pin "14") (pinfunction "Y1_14") (pintype "unspecified"))
    )
    (net (code "361") (name "/V10_7") (class "Default")
      (node (ref "U38") (pin "12") (pinfunction "Y3_12") (pintype "unspecified"))
    )
    (net (code "362") (name "/V11_2") (class "Default")
      (node (ref "U42") (pin "15") (pinfunction "Y2_15") (pintype "unspecified"))
    )
    (net (code "363") (name "/V11_3") (class "Default")
      (node (ref "U43") (pin "1") (pinfunction "Y4_1") (pintype "unspecified"))
    )
    (net (code "364") (name "/V11_4") (class "Default")
      (node (ref "U44") (pin "2") (pinfunction "Y6_2") (pintype "unspecified"))
    )
    (net (code "365") (name "/V11_5") (class "Default")
      (node (ref "U36") (pin "13") (pinfunction "Y0_13") (pintype "unspecified"))
    )
    (net (code "366") (name "/V11_6") (class "Default")
      (node (ref "U37") (pin "15") (pinfunction "Y2_15") (pintype "unspecified"))
    )
    (net (code "367") (name "/V11_7") (class "Default")
      (node (ref "U38") (pin "1") (pinfunction "Y4_1") (pintype "unspecified"))
    )
    (net (code "368") (name "/V12_2") (class "Default")
      (node (ref "U42") (pin "12") (pinfunction "Y3_12") (pintype "unspecified"))
    )
    (net (code "369") (name "/V12_3") (class "Default")
      (node (ref "U43") (pin "5") (pinfunction "Y5_5") (pintype "unspecified"))
    )
    (net (code "370") (name "/V12_4") (class "Default")
      (node (ref "U44") (pin "4") (pinfunction "Y7_4") (pintype "unspecified"))
    )
    (net (code "371") (name "/V12_5") (class "Default")
      (node (ref "U36") (pin "14") (pinfunction "Y1_14") (pintype "unspecified"))
    )
    (net (code "372") (name "/V12_6") (class "Default")
      (node (ref "U37") (pin "12") (pinfunction "Y3_12") (pintype "unspecified"))
    )
    (net (code "373") (name "/V12_7") (class "Default")
      (node (ref "U38") (pin "5") (pinfunction "Y5_5") (pintype "unspecified"))
    )
    (net (code "374") (name "/V13_2") (class "Default")
      (node (ref "U42") (pin "1") (pinfunction "Y4_1") (pintype "unspecified"))
    )
    (net (code "375") (name "/V13_3") (class "Default")
      (node (ref "U43") (pin "2") (pinfunction "Y6_2") (pintype "unspecified"))
    )
    (net (code "376") (name "/V13_4") (class "Default")
      (node (ref "U35") (pin "13") (pinfunction "Y0_13") (pintype "unspecified"))
    )
    (net (code "377") (name "/V13_5") (class "Default")
      (node (ref "U36") (pin "15") (pinfunction "Y2_15") (pintype "unspecified"))
    )
    (net (code "378") (name "/V13_6") (class "Default")
      (node (ref "U37") (pin "1") (pinfunction "Y4_1") (pintype "unspecified"))
    )
    (net (code "379") (name "/V13_7") (class "Default")
      (node (ref "U38") (pin "2") (pinfunction "Y6_2") (pintype "unspecified"))
    )
    (net (code "380") (name "/V14_2") (class "Default")
      (node (ref "U42") (pin "5") (pinfunction "Y5_5") (pintype "unspecified"))
    )
    (net (code "381") (name "/V14_3") (class "Default")
      (node (ref "U43") (pin "4") (pinfunction "Y7_4") (pintype "unspecified"))
    )
    (net (code "382") (name "/V14_4") (class "Default")
      (node (ref "U35") (pin "14") (pinfunction "Y1_14") (pintype "unspecified"))
    )
    (net (code "383") (name "/V14_5") (class "Default")
      (node (ref "U36") (pin "12") (pinfunction "Y3_12") (pintype "unspecified"))
    )
    (net (code "384") (name "/V14_6") (class "Default")
      (node (ref "U37") (pin "5") (pinfunction "Y5_5") (pintype "unspecified"))
    )
    (net (code "385") (name "/V14_7") (class "Default")
      (node (ref "U38") (pin "4") (pinfunction "Y7_4") (pintype "unspecified"))
    )
    (net (code "386") (name "/V15_2") (class "Default")
      (node (ref "U42") (pin "2") (pinfunction "Y6_2") (pintype "unspecified"))
    )
    (net (code "387") (name "/V15_3") (class "Default")
      (node (ref "U34") (pin "13") (pinfunction "Y0_13") (pintype "unspecified"))
    )
    (net (code "388") (name "/V15_4") (class "Default")
      (node (ref "U35") (pin "15") (pinfunction "Y2_15") (pintype "unspecified"))
    )
    (net (code "389") (name "/V15_5") (class "Default")
      (node (ref "U36") (pin "1") (pinfunction "Y4_1") (pintype "unspecified"))
    )
    (net (code "390") (name "/V15_6") (class "Default")
      (node (ref "U37") (pin "2") (pinfunction "Y6_2") (pintype "unspecified"))
    )
    (net (code "391") (name "/V15_7") (class "Default")
      (node (ref "U48") (pin "13") (pinfunction "Y0_13") (pintype "unspecified"))
    )
    (net (code "392") (name "/V16_2") (class "Default")
      (node (ref "U42") (pin "4") (pinfunction "Y7_4") (pintype "unspecified"))
    )
    (net (code "393") (name "/V16_3") (class "Default")
      (node (ref "U34") (pin "14") (pinfunction "Y1_14") (pintype "unspecified"))
    )
    (net (code "394") (name "/V16_4") (class "Default")
      (node (ref "U35") (pin "12") (pinfunction "Y3_12") (pintype "unspecified"))
    )
    (net (code "395") (name "/V16_5") (class "Default")
      (node (ref "U36") (pin "5") (pinfunction "Y5_5") (pintype "unspecified"))
    )
    (net (code "396") (name "/V16_6") (class "Default")
      (node (ref "U37") (pin "4") (pinfunction "Y7_4") (pintype "unspecified"))
    )
    (net (code "397") (name "/V16_7") (class "Default")
      (node (ref "U48") (pin "14") (pinfunction "Y1_14") (pintype "unspecified"))
    )
    (net (code "398") (name "/V17_2") (class "Default")
      (node (ref "U33") (pin "13") (pinfunction "Y0_13") (pintype "unspecified"))
    )
    (net (code "399") (name "/V17_3") (class "Default")
      (node (ref "U34") (pin "15") (pinfunction "Y2_15") (pintype "unspecified"))
    )
    (net (code "400") (name "/V17_4") (class "Default")
      (node (ref "U35") (pin "1") (pinfunction "Y4_1") (pintype "unspecified"))
    )
    (net (code "401") (name "/V17_5") (class "Default")
      (node (ref "U36") (pin "2") (pinfunction "Y6_2") (pintype "unspecified"))
    )
    (net (code "402") (name "/V17_6") (class "Default")
      (node (ref "U47") (pin "13") (pinfunction "Y0_13") (pintype "unspecified"))
    )
    (net (code "403") (name "/V17_7") (class "Default")
      (node (ref "U48") (pin "15") (pinfunction "Y2_15") (pintype "unspecified"))
    )
    (net (code "404") (name "/V18_2") (class "Default")
      (node (ref "U33") (pin "14") (pinfunction "Y1_14") (pintype "unspecified"))
    )
    (net (code "405") (name "/V18_3") (class "Default")
      (node (ref "U34") (pin "12") (pinfunction "Y3_12") (pintype "unspecified"))
    )
    (net (code "406") (name "/V18_4") (class "Default")
      (node (ref "U35") (pin "5") (pinfunction "Y5_5") (pintype "unspecified"))
    )
    (net (code "407") (name "/V18_5") (class "Default")
      (node (ref "U36") (pin "4") (pinfunction "Y7_4") (pintype "unspecified"))
    )
    (net (code "408") (name "/V18_6") (class "Default")
      (node (ref "U47") (pin "14") (pinfunction "Y1_14") (pintype "unspecified"))
    )
    (net (code "409") (name "/V18_7") (class "Default")
      (node (ref "U48") (pin "12") (pinfunction "Y3_12") (pintype "unspecified"))
    )
    (net (code "410") (name "/VCC_F_1") (class "Default")
      (node (ref "C22") (pin "1") (pinfunction "1_1") (pintype "unspecified"))
      (node (ref "U10") (pin "8") (pinfunction "VCC_8") (pintype "unspecified"))
    )
    (net (code "411") (name "/VCC_F_2") (class "Default")
      (node (ref "C24") (pin "1") (pinfunction "1_1") (pintype "unspecified"))
      (node (ref "U11") (pin "8") (pinfunction "VCC_8") (pintype "unspecified"))
    )
    (net (code "412") (name "/VCC_F_3") (class "Default")
      (node (ref "C26") (pin "1") (pinfunction "1_1") (pintype "unspecified"))
      (node (ref "U12") (pin "8") (pinfunction "VCC_8") (pintype "unspecified"))
    )
    (net (code "413") (name "/VCC_F_4") (class "Default")
      (node (ref "C28") (pin "1") (pinfunction "1_1") (pintype "unspecified"))
      (node (ref "U13") (pin "8") (pinfunction "VCC_8") (pintype "unspecified"))
    )
    (net (code "414") (name "/VCC_F_5") (class "Default")
      (node (ref "C30") (pin "1") (pinfunction "1_1") (pintype "unspecified"))
      (node (ref "U14") (pin "8") (pinfunction "VCC_8") (pintype "unspecified"))
    )
    (net (code "415") (name "/VCC_F_6") (class "Default")
      (node (ref "C32") (pin "1") (pinfunction "1_1") (pintype "unspecified"))
      (node (ref "U15") (pin "8") (pinfunction "VCC_8") (pintype "unspecified"))
    )
    (net (code "416") (name "/VCC_F_7") (class "Default")
      (node (ref "C34") (pin "1") (pinfunction "1_1") (pintype "unspecified"))
      (node (ref "U16") (pin "8") (pinfunction "VCC_8") (pintype "unspecified"))
    )
    (net (code "417") (name "/VCC_F_8") (class "Default")
      (node (ref "C36") (pin "1") (pinfunction "1_1") (pintype "unspecified"))
      (node (ref "U17") (pin "8") (pinfunction "VCC_8") (pintype "unspecified"))
    )
    (net (code "418") (name "/VCC_F_9") (class "Default")
      (node (ref "C38") (pin "1") (pinfunction "1_1") (pintype "unspecified"))
      (node (ref "U18") (pin "8") (pinfunction "VCC_8") (pintype "unspecified"))
    )
    (net (code "419") (name "/VCC_F_10") (class "Default")
      (node (ref "C40") (pin "1") (pinfunction "1_1") (pintype "unspecified"))
      (node (ref "U19") (pin "8") (pinfunction "VCC_8") (pintype "unspecified"))
    )
    (net (code "420") (name "/VCC_F_11") (class "Default")
      (node (ref "C42") (pin "1") (pinfunction "1_1") (pintype "unspecified"))
      (node (ref "U20") (pin "8") (pinfunction "VCC_8") (pintype "unspecified"))
    )
    (net (code "421") (name "/VCC_F_12") (class "Default")
      (node (ref "C44") (pin "1") (pinfunction "1_1") (pintype "unspecified"))
      (node (ref "U21") (pin "8") (pinfunction "VCC_8") (pintype "unspecified"))
    )
    (net (code "422") (name "/VCC_F_13") (class "Default")
      (node (ref "C46") (pin "1") (pinfunction "1_1") (pintype "unspecified"))
      (node (ref "U22") (pin "8") (pinfunction "VCC_8") (pintype "unspecified"))
    )
    (net (code "423") (name "/VCC_F_14") (class "Default")
      (node (ref "C48") (pin "1") (pinfunction "1_1") (pintype "unspecified"))
      (node (ref "U23") (pin "8") (pinfunction "VCC_8") (pintype "unspecified"))
    )
    (net (code "424") (name "/VCC_F_15") (class "Default")
      (node (ref "C50") (pin "1") (pinfunction "1_1") (pintype "unspecified"))
      (node (ref "U24") (pin "8") (pinfunction "VCC_8") (pintype "unspecified"))
    )
    (net (code "425") (name "/VCC_F_16") (class "Default")
      (node (ref "C52") (pin "1") (pinfunction "1_1") (pintype "unspecified"))
      (node (ref "U25") (pin "8") (pinfunction "VCC_8") (pintype "unspecified"))
    )
    (net (code "426") (name "/VCC_F_17") (class "Default")
      (node (ref "C54") (pin "1") (pinfunction "1_1") (pintype "unspecified"))
      (node (ref "U26") (pin "8") (pinfunction "VCC_8") (pintype "unspecified"))
    )
    (net (code "427") (name "/VCC_F_18") (class "Default")
      (node (ref "C56") (pin "1") (pinfunction "1_1") (pintype "unspecified"))
      (node (ref "U27") (pin "8") (pinfunction "VCC_8") (pintype "unspecified"))
    )
    (net (code "428") (name "/V_CAP") (class "Default")
      (node (ref "C124") (pin "2") (pinfunction "2_2") (pintype "unspecified"))
      (node (ref "U60") (pin "22") (pinfunction "VCAP-1_22") (pintype "unspecified"))
    )
    (net (code "429") (name "/charger_block") (class "Default")
      (node (ref "C18") (pin "1") (pinfunction "1_1") (pintype "unspecified"))
      (node (ref "R67") (pin "2") (pinfunction "2_2") (pintype "unspecified"))
      (node (ref "RSH1") (pin "1") (pinfunction "1_1") (pintype "unspecified"))
    )
    (net (code "430") (name "/f1_node") (class "Default")
      (node (ref "D19") (pin "2") (pinfunction "A_2") (pintype "unspecified"))
      (node (ref "F1") (pin "1") (pinfunction "1_1") (pintype "unspecified"))
      (node (ref "Q1") (pin "3") (pinfunction "D_3") (pintype "unspecified"))
    )
    (net (code "431") (name "/fl_node") (class "Default")
      (node (ref "C12") (pin "1") (pinfunction "1_1") (pintype "input"))
      (node (ref "D20") (pin "2") (pinfunction "A_2") (pintype "unspecified"))
      (node (ref "D21") (pin "2") (pinfunction "A_2") (pintype "unspecified"))
      (node (ref "D22") (pin "2") (pinfunction "A_2") (pintype "unspecified"))
      (node (ref "D23") (pin "2") (pinfunction "A_2") (pintype "unspecified"))
      (node (ref "D24") (pin "2") (pinfunction "A_2") (pintype "unspecified"))
      (node (ref "D25") (pin "2") (pinfunction "A_2") (pintype "unspecified"))
      (node (ref "D26") (pin "2") (pinfunction "A_2") (pintype "unspecified"))
      (node (ref "D27") (pin "2") (pinfunction "A_2") (pintype "unspecified"))
      (node (ref "D28") (pin "2") (pinfunction "A_2") (pintype "unspecified"))
      (node (ref "D29") (pin "2") (pinfunction "A_2") (pintype "unspecified"))
      (node (ref "D30") (pin "2") (pinfunction "A_2") (pintype "unspecified"))
      (node (ref "D31") (pin "2") (pinfunction "A_2") (pintype "unspecified"))
      (node (ref "D32") (pin "2") (pinfunction "A_2") (pintype "unspecified"))
      (node (ref "D33") (pin "2") (pinfunction "A_2") (pintype "unspecified"))
      (node (ref "D34") (pin "2") (pinfunction "A_2") (pintype "unspecified"))
      (node (ref "D35") (pin "2") (pinfunction "A_2") (pintype "unspecified"))
      (node (ref "D36") (pin "2") (pinfunction "A_2") (pintype "unspecified"))
      (node (ref "Q10") (pin "3") (pinfunction "D_3") (pintype "unspecified"))
      (node (ref "Q11") (pin "3") (pinfunction "D_3") (pintype "unspecified"))
      (node (ref "Q12") (pin "3") (pinfunction "D_3") (pintype "unspecified"))
      (node (ref "Q13") (pin "3") (pinfunction "D_3") (pintype "unspecified"))
      (node (ref "Q14") (pin "3") (pinfunction "D_3") (pintype "unspecified"))
      (node (ref "Q15") (pin "3") (pinfunction "D_3") (pintype "unspecified"))
      (node (ref "Q16") (pin "3") (pinfunction "D_3") (pintype "unspecified"))
      (node (ref "Q17") (pin "3") (pinfunction "D_3") (pintype "unspecified"))
      (node (ref "Q18") (pin "3") (pinfunction "D_3") (pintype "unspecified"))
      (node (ref "Q2") (pin "3") (pinfunction "D_3") (pintype "unspecified"))
      (node (ref "Q3") (pin "3") (pinfunction "D_3") (pintype "unspecified"))
      (node (ref "Q4") (pin "3") (pinfunction "D_3") (pintype "unspecified"))
      (node (ref "Q5") (pin "3") (pinfunction "D_3") (pintype "unspecified"))
      (node (ref "Q6") (pin "3") (pinfunction "D_3") (pintype "unspecified"))
      (node (ref "Q7") (pin "3") (pinfunction "D_3") (pintype "unspecified"))
      (node (ref "Q8") (pin "3") (pinfunction "D_3") (pintype "unspecified"))
      (node (ref "Q9") (pin "3") (pinfunction "D_3") (pintype "unspecified"))
      (node (ref "U28") (pin "1") (pinfunction "VIN_1") (pintype "unspecified"))
    )
    (net (code "432") (name "/im_e") (class "Default")
      (node (ref "R13") (pin "2") (pinfunction "2_2") (pintype "input"))
      (node (ref "U59") (pin "29") (pinfunction "P30_29") (pintype "unspecified"))
      (node (ref "U7") (pin "19") (pinfunction "EOC_19") (pintype "unspecified"))
      (node (ref "U8") (pin "19") (pinfunction "EOC_19") (pintype "unspecified"))
    )
    (net (code "433") (name "/ind_1") (class "Default")
      (node (ref "U59") (pin "19") (pinfunction "P22_19") (pintype "unspecified"))
      (node (ref "U9") (pin "11") (pinfunction "SHCP_11") (pintype "unspecified"))
    )
    (net (code "434") (name "/ind_2") (class "Default")
      (node (ref "U59") (pin "20") (pinfunction "P23_20") (pintype "unspecified"))
      (node (ref "U9") (pin "12") (pinfunction "STCP_12") (pintype "unspecified"))
    )
    (net (code "435") (name "/ind_3") (class "Default")
      (node (ref "U59") (pin "21") (pinfunction "P24_21") (pintype "unspecified"))
      (node (ref "U9") (pin "14") (pinfunction "DS_14") (pintype "unspecified"))
    )
    (net (code "436") (name "/p1_en") (class "Default")
      (node (ref "D1") (pin "2") (pinfunction "A_2") (pintype "unspecified"))
      (node (ref "R14") (pin "2") (pinfunction "2_2") (pintype "unspecified"))
      (node (ref "U56") (pin "23") (pinfunction "P26_23") (pintype "unspecified"))
    )
    (net (code "437") (name "/p2_en") (class "Default")
      (node (ref "D2") (pin "2") (pinfunction "A_2") (pintype "unspecified"))
      (node (ref "R15") (pin "2") (pinfunction "2_2") (pintype "unspecified"))
      (node (ref "U56") (pin "24") (pinfunction "P27_24") (pintype "unspecified"))
    )
    (net (code "438") (name "/p3_en") (class "Default")
      (node (ref "D3") (pin "2") (pinfunction "A_2") (pintype "unspecified"))
      (node (ref "R16") (pin "2") (pinfunction "2_2") (pintype "unspecified"))
      (node (ref "U56") (pin "25") (pinfunction "P28_25") (pintype "unspecified"))
    )
    (net (code "439") (name "/p4_en") (class "Default")
      (node (ref "D4") (pin "2") (pinfunction "A_2") (pintype "unspecified"))
      (node (ref "R17") (pin "2") (pinfunction "2_2") (pintype "unspecified"))
      (node (ref "U56") (pin "27") (pinfunction "P29_27") (pintype "unspecified"))
    )
    (net (code "440") (name "/p5_en") (class "Default")
      (node (ref "D5") (pin "2") (pinfunction "A_2") (pintype "unspecified"))
      (node (ref "R18") (pin "2") (pinfunction "2_2") (pintype "unspecified"))
      (node (ref "U56") (pin "29") (pinfunction "P30_29") (pintype "unspecified"))
    )
    (net (code "441") (name "/p6_en") (class "Default")
      (node (ref "D6") (pin "2") (pinfunction "A_2") (pintype "unspecified"))
      (node (ref "R19") (pin "2") (pinfunction "2_2") (pintype "unspecified"))
      (node (ref "U56") (pin "31") (pinfunction "P31_31") (pintype "unspecified"))
    )
    (net (code "442") (name "/p7_en") (class "Default")
      (node (ref "D7") (pin "2") (pinfunction "A_2") (pintype "unspecified"))
      (node (ref "R20") (pin "2") (pinfunction "2_2") (pintype "unspecified"))
      (node (ref "U59") (pin "32") (pinfunction "P4_32") (pintype "unspecified"))
    )
    (net (code "443") (name "/p8_en") (class "Default")
      (node (ref "D8") (pin "2") (pinfunction "A_2") (pintype "unspecified"))
      (node (ref "R21") (pin "2") (pinfunction "2_2") (pintype "unspecified"))
      (node (ref "U59") (pin "30") (pinfunction "P5_30") (pintype "unspecified"))
    )
    (net (code "444") (name "/p9_en") (class "Default")
      (node (ref "D9") (pin "2") (pinfunction "A_2") (pintype "unspecified"))
      (node (ref "R22") (pin "2") (pinfunction "2_2") (pintype "unspecified"))
      (node (ref "U59") (pin "28") (pinfunction "P6_28") (pintype "unspecified"))
    )
    (net (code "445") (name "/p10_en") (class "Default")
      (node (ref "D10") (pin "2") (pinfunction "A_2") (pintype "unspecified"))
      (node (ref "R23") (pin "2") (pinfunction "2_2") (pintype "unspecified"))
      (node (ref "U59") (pin "26") (pinfunction "P7_26") (pintype "unspecified"))
    )
    (net (code "446") (name "/p11_en") (class "Default")
      (node (ref "D11") (pin "2") (pinfunction "A_2") (pintype "unspecified"))
      (node (ref "R24") (pin "2") (pinfunction "2_2") (pintype "unspecified"))
      (node (ref "U59") (pin "5") (pinfunction "P8_5") (pintype "unspecified"))
    )
    (net (code "447") (name "/p12_en") (class "Default")
      (node (ref "D12") (pin "2") (pinfunction "A_2") (pintype "unspecified"))
      (node (ref "R25") (pin "2") (pinfunction "2_2") (pintype "unspecified"))
      (node (ref "U59") (pin "7") (pinfunction "P9_7") (pintype "unspecified"))
    )
    (net (code "448") (name "/p13_en") (class "Default")
      (node (ref "D13") (pin "2") (pinfunction "A_2") (pintype "unspecified"))
      (node (ref "R26") (pin "2") (pinfunction "2_2") (pintype "unspecified"))
      (node (ref "U59") (pin "9") (pinfunction "P10_9") (pintype "unspecified"))
    )
    (net (code "449") (name "/p14_en") (class "Default")
      (node (ref "D14") (pin "2") (pinfunction "A_2") (pintype "unspecified"))
      (node (ref "R27") (pin "2") (pinfunction "2_2") (pintype "unspecified"))
      (node (ref "U59") (pin "11") (pinfunction "P11_11") (pintype "unspecified"))
    )
    (net (code "450") (name "/p15_en") (class "Default")
      (node (ref "D15") (pin "2") (pinfunction "A_2") (pintype "unspecified"))
      (node (ref "R28") (pin "2") (pinfunction "2_2") (pintype "unspecified"))
      (node (ref "U59") (pin "6") (pinfunction "P12_6") (pintype "unspecified"))
    )
    (net (code "451") (name "/p16_en") (class "Default")
      (node (ref "D16") (pin "2") (pinfunction "A_2") (pintype "unspecified"))
      (node (ref "R29") (pin "2") (pinfunction "2_2") (pintype "unspecified"))
      (node (ref "U59") (pin "8") (pinfunction "P13_8") (pintype "unspecified"))
    )
    (net (code "452") (name "/p17_en") (class "Default")
      (node (ref "D17") (pin "2") (pinfunction "A_2") (pintype "unspecified"))
      (node (ref "R30") (pin "2") (pinfunction "2_2") (pintype "unspecified"))
      (node (ref "U59") (pin "10") (pinfunction "P14_10") (pintype "unspecified"))
    )
    (net (code "453") (name "/p18_en") (class "Default")
      (node (ref "D18") (pin "2") (pinfunction "A_2") (pintype "unspecified"))
      (node (ref "R31") (pin "2") (pinfunction "2_2") (pintype "unspecified"))
      (node (ref "U59") (pin "12") (pinfunction "P15_12") (pintype "unspecified"))
    )
    (net (code "454") (name "/power_switch") (class "Default")
      (node (ref "C18") (pin "2") (pinfunction "2_2") (pintype "unspecified"))
      (node (ref "C98") (pin "2") (pinfunction "2_2") (pintype "unspecified"))
      (node (ref "D49") (pin "2") (pinfunction "A_2") (pintype "unspecified"))
      (node (ref "Q24") (pin "3") (pinfunction "S_3") (pintype "unspecified"))
      (node (ref "R66") (pin "2") (pinfunction "2_2") (pintype "unspecified"))
      (node (ref "RSH1") (pin "2") (pinfunction "2_2") (pintype "unspecified"))
      (node (ref "U29") (pin "8") (pinfunction "VBUS_8") (pintype "unspecified"))
    )
    (net (code "455") (name "/ps") (class "Default")
      (node (ref "R71") (pin "1") (pinfunction "1_1") (pintype "unspecified"))
      (node (ref "U59") (pin "25") (pinfunction "P28_25") (pintype "unspecified"))
    )
    (net (code "456") (name "/psB") (class "Default")
      (node (ref "U31") (pin "6") (pinfunction "S_6") (pintype "unspecified"))
      (node (ref "U59") (pin "22") (pinfunction "P25_22") (pintype "unspecified"))
    )
    (net (code "457") (name "/t1") (class "Default")
      (node (ref "C7") (pin "1") (pinfunction "1_1") (pintype "input"))
      (node (ref "R1") (pin "2") (pinfunction "2_2") (pintype "unspecified"))
      (node (ref "R8") (pin "1") (pinfunction "1_1") (pintype "unspecified"))
      (node (ref "U1") (pin "1") (pinfunction "1_1") (pintype "unspecified"))
      (node (ref "U5") (pin "2") (pinfunction "CH0_2") (pintype "unspecified"))
    )
    (net (code "458") (name "/t2") (class "Default")
      (node (ref "C8") (pin "1") (pinfunction "1_1") (pintype "input"))
      (node (ref "R2") (pin "2") (pinfunction "2_2") (pintype "unspecified"))
      (node (ref "R9") (pin "1") (pinfunction "1_1") (pintype "unspecified"))
      (node (ref "U2") (pin "1") (pinfunction "1_1") (pintype "unspecified"))
      (node (ref "U5") (pin "3") (pinfunction "CH1_3") (pintype "unspecified"))
    )
    (net (code "459") (name "/t3") (class "Default")
      (node (ref "C9") (pin "1") (pinfunction "1_1") (pintype "input"))
      (node (ref "R10") (pin "1") (pinfunction "1_1") (pintype "unspecified"))
      (node (ref "R3") (pin "2") (pinfunction "2_2") (pintype "unspecified"))
      (node (ref "U3") (pin "1") (pinfunction "1_1") (pintype "unspecified"))
      (node (ref "U5") (pin "4") (pinfunction "CH2_4") (pintype "unspecified"))
    )
    (net (code "460") (name "/t4") (class "Default")
      (node (ref "C10") (pin "1") (pinfunction "1_1") (pintype "input"))
      (node (ref "R11") (pin "1") (pinfunction "1_1") (pintype "unspecified"))
      (node (ref "R4") (pin "2") (pinfunction "2_2") (pintype "unspecified"))
      (node (ref "U4") (pin "1") (pinfunction "1_1") (pintype "unspecified"))
      (node (ref "U5") (pin "5") (pinfunction "CH3_5") (pintype "unspecified"))
    )
    (net (code "461") (name "/tm_busy") (class "Default")
      (node (ref "R12") (pin "1") (pinfunction "1_1") (pintype "input"))
      (node (ref "U5") (pin "13") (pinfunction "BUSY_13") (pintype "unspecified"))
    )
    (net (code "462") (name "/tm_busy_R") (class "Default")
      (node (ref "R12") (pin "2") (pinfunction "2_2") (pintype "input"))
      (node (ref "U59") (pin "27") (pinfunction "P29_27") (pintype "unspecified"))
    )
    (net (code "463") (name "/tm_e") (class "Default")
      (node (ref "R13") (pin "1") (pinfunction "1_1") (pintype "input"))
      (node (ref "U5") (pin "7") (pinfunction "SHDN_7") (pintype "unspecified"))
    )
    (net (code "464") (name "/v1_1") (class "Default")
      (node (ref "CN1") (pin "2") (pinfunction "2_2") (pintype "unspecified"))
      (node (ref "CN1") (pin "4") (pinfunction "4_4") (pintype "unspecified"))
      (node (ref "CN1") (pin "6") (pinfunction "6_6") (pintype "unspecified"))
    )
    (net (code "465") (name "/v1_2") (class "Default")
      (node (ref "H4") (pin "1") (pinfunction "1_1") (pintype "unspecified"))
    )
    (net (code "466") (name "/v1_3") (class "Default")
      (node (ref "H4") (pin "3") (pinfunction "3_3") (pintype "unspecified"))
    )
    (net (code "467") (name "/v1_4") (class "Default")
      (node (ref "H4") (pin "5") (pinfunction "5_5") (pintype "unspecified"))
    )
    (net (code "468") (name "/v1_5") (class "Default")
      (node (ref "H4") (pin "7") (pinfunction "7_7") (pintype "unspecified"))
    )
    (net (code "469") (name "/v1_6") (class "Default")
      (node (ref "H4") (pin "9") (pinfunction "9_9") (pintype "unspecified"))
    )
    (net (code "470") (name "/v1_7") (class "Default")
      (node (ref "H4") (pin "11") (pinfunction "11_11") (pintype "unspecified"))
    )
    (net (code "471") (name "/v2_2") (class "Default")
      (node (ref "H4") (pin "13") (pinfunction "13_13") (pintype "unspecified"))
    )
    (net (code "472") (name "/v2_3") (class "Default")
      (node (ref "H4") (pin "15") (pinfunction "15_15") (pintype "unspecified"))
    )
    (net (code "473") (name "/v2_4") (class "Default")
      (node (ref "H4") (pin "17") (pinfunction "17_17") (pintype "unspecified"))
    )
    (net (code "474") (name "/v2_5") (class "Default")
      (node (ref "H4") (pin "19") (pinfunction "19_19") (pintype "unspecified"))
    )
    (net (code "475") (name "/v2_6") (class "Default")
      (node (ref "H4") (pin "21") (pinfunction "21_21") (pintype "unspecified"))
    )
    (net (code "476") (name "/v2_7") (class "Default")
      (node (ref "H4") (pin "23") (pinfunction "23_23") (pintype "unspecified"))
    )
    (net (code "477") (name "/v3_2") (class "Default")
      (node (ref "H4") (pin "25") (pinfunction "25_25") (pintype "unspecified"))
    )
    (net (code "478") (name "/v3_3") (class "Default")
      (node (ref "H4") (pin "27") (pinfunction "27_27") (pintype "unspecified"))
    )
    (net (code "479") (name "/v3_4") (class "Default")
      (node (ref "H4") (pin "29") (pinfunction "29_29") (pintype "unspecified"))
    )
    (net (code "480") (name "/v3_5") (class "Default")
      (node (ref "H4") (pin "31") (pinfunction "31_31") (pintype "unspecified"))
    )
    (net (code "481") (name "/v3_6") (class "Default")
      (node (ref "H4") (pin "33") (pinfunction "33_33") (pintype "unspecified"))
    )
    (net (code "482") (name "/v3_7") (class "Default")
      (node (ref "H4") (pin "35") (pinfunction "35_35") (pintype "unspecified"))
    )
    (net (code "483") (name "/v4_2") (class "Default")
      (node (ref "H4") (pin "37") (pinfunction "37_37") (pintype "unspecified"))
    )
    (net (code "484") (name "/v4_3") (class "Default")
      (node (ref "H4") (pin "39") (pinfunction "39_39") (pintype "unspecified"))
    )
    (net (code "485") (name "/v4_4") (class "Default")
      (node (ref "H4") (pin "41") (pinfunction "41_41") (pintype "unspecified"))
    )
    (net (code "486") (name "/v4_5") (class "Default")
      (node (ref "H4") (pin "43") (pinfunction "43_43") (pintype "unspecified"))
    )
    (net (code "487") (name "/v4_6") (class "Default")
      (node (ref "H4") (pin "45") (pinfunction "45_45") (pintype "unspecified"))
    )
    (net (code "488") (name "/v4_7") (class "Default")
      (node (ref "H4") (pin "47") (pinfunction "47_47") (pintype "unspecified"))
    )
    (net (code "489") (name "/v5_2") (class "Default")
      (node (ref "H4") (pin "49") (pinfunction "49_49") (pintype "unspecified"))
    )
    (net (code "490") (name "/v5_3") (class "Default")
      (node (ref "H4") (pin "51") (pinfunction "51_51") (pintype "unspecified"))
    )
    (net (code "491") (name "/v5_4") (class "Default")
      (node (ref "H4") (pin "53") (pinfunction "53_53") (pintype "unspecified"))
    )
    (net (code "492") (name "/v5_5") (class "Default")
      (node (ref "H4") (pin "55") (pinfunction "55_55") (pintype "unspecified"))
    )
    (net (code "493") (name "/v5_6") (class "Default")
      (node (ref "H4") (pin "57") (pinfunction "57_57") (pintype "unspecified"))
    )
    (net (code "494") (name "/v5_7") (class "Default")
      (node (ref "H4") (pin "59") (pinfunction "59_59") (pintype "unspecified"))
    )
    (net (code "495") (name "/v6_2") (class "Default")
      (node (ref "H4") (pin "61") (pinfunction "61_61") (pintype "unspecified"))
    )
    (net (code "496") (name "/v6_3") (class "Default")
      (node (ref "H4") (pin "63") (pinfunction "63_63") (pintype "unspecified"))
    )
    (net (code "497") (name "/v6_4") (class "Default")
      (node (ref "H4") (pin "2") (pinfunction "2_2") (pintype "unspecified"))
    )
    (net (code "498") (name "/v6_5") (class "Default")
      (node (ref "H4") (pin "4") (pinfunction "4_4") (pintype "unspecified"))
    )
    (net (code "499") (name "/v6_6") (class "Default")
      (node (ref "H4") (pin "6") (pinfunction "6_6") (pintype "unspecified"))
    )
    (net (code "500") (name "/v6_7") (class "Default")
      (node (ref "H4") (pin "8") (pinfunction "8_8") (pintype "unspecified"))
    )
    (net (code "501") (name "/v7_2") (class "Default")
      (node (ref "H4") (pin "10") (pinfunction "10_10") (pintype "unspecified"))
    )
    (net (code "502") (name "/v7_3") (class "Default")
      (node (ref "H4") (pin "12") (pinfunction "12_12") (pintype "unspecified"))
    )
    (net (code "503") (name "/v7_4") (class "Default")
      (node (ref "H4") (pin "14") (pinfunction "14_14") (pintype "unspecified"))
    )
    (net (code "504") (name "/v7_5") (class "Default")
      (node (ref "H4") (pin "16") (pinfunction "16_16") (pintype "unspecified"))
    )
    (net (code "505") (name "/v7_6") (class "Default")
      (node (ref "H4") (pin "18") (pinfunction "18_18") (pintype "unspecified"))
    )
    (net (code "506") (name "/v7_7") (class "Default")
      (node (ref "H4") (pin "20") (pinfunction "20_20") (pintype "unspecified"))
    )
    (net (code "507") (name "/v8_2") (class "Default")
      (node (ref "H4") (pin "22") (pinfunction "22_22") (pintype "unspecified"))
    )
    (net (code "508") (name "/v8_3") (class "Default")
      (node (ref "H4") (pin "24") (pinfunction "24_24") (pintype "unspecified"))
    )
    (net (code "509") (name "/v8_4") (class "Default")
      (node (ref "H4") (pin "26") (pinfunction "26_26") (pintype "unspecified"))
    )
    (net (code "510") (name "/v8_5") (class "Default")
      (node (ref "H4") (pin "28") (pinfunction "28_28") (pintype "unspecified"))
    )
    (net (code "511") (name "/v8_6") (class "Default")
      (node (ref "H4") (pin "30") (pinfunction "30_30") (pintype "unspecified"))
    )
    (net (code "512") (name "/v8_7") (class "Default")
      (node (ref "H4") (pin "32") (pinfunction "32_32") (pintype "unspecified"))
    )
    (net (code "513") (name "/v9_2") (class "Default")
      (node (ref "H4") (pin "34") (pinfunction "34_34") (pintype "unspecified"))
    )
    (net (code "514") (name "/v9_3") (class "Default")
      (node (ref "H4") (pin "36") (pinfunction "36_36") (pintype "unspecified"))
    )
    (net (code "515") (name "/v9_4") (class "Default")
      (node (ref "H4") (pin "38") (pinfunction "38_38") (pintype "unspecified"))
    )
    (net (code "516") (name "/v9_5") (class "Default")
      (node (ref "H4") (pin "40") (pinfunction "40_40") (pintype "unspecified"))
    )
    (net (code "517") (name "/v9_6") (class "Default")
      (node (ref "H4") (pin "42") (pinfunction "42_42") (pintype "unspecified"))
    )
    (net (code "518") (name "/v9_7") (class "Default")
      (node (ref "H4") (pin "44") (pinfunction "44_44") (pintype "unspecified"))
    )
    (net (code "519") (name "/v10_2") (class "Default")
      (node (ref "H4") (pin "46") (pinfunction "46_46") (pintype "unspecified"))
    )
    (net (code "520") (name "/v10_3") (class "Default")
      (node (ref "H4") (pin "48") (pinfunction "48_48") (pintype "unspecified"))
    )
    (net (code "521") (name "/v10_4") (class "Default")
      (node (ref "H4") (pin "50") (pinfunction "50_50") (pintype "unspecified"))
    )
    (net (code "522") (name "/v10_5") (class "Default")
      (node (ref "H4") (pin "52") (pinfunction "52_52") (pintype "unspecified"))
    )
    (net (code "523") (name "/v10_6") (class "Default")
      (node (ref "H4") (pin "54") (pinfunction "54_54") (pintype "unspecified"))
    )
    (net (code "524") (name "/v10_7") (class "Default")
      (node (ref "H4") (pin "56") (pinfunction "56_56") (pintype "unspecified"))
    )
    (net (code "525") (name "/v11_2") (class "Default")
      (node (ref "H5") (pin "63") (pinfunction "63_63") (pintype "unspecified"))
    )
    (net (code "526") (name "/v11_3") (class "Default")
      (node (ref "H5") (pin "61") (pinfunction "61_61") (pintype "unspecified"))
    )
    (net (code "527") (name "/v11_4") (class "Default")
      (node (ref "H5") (pin "59") (pinfunction "59_59") (pintype "unspecified"))
    )
    (net (code "528") (name "/v11_5") (class "Default")
      (node (ref "H5") (pin "57") (pinfunction "57_57") (pintype "unspecified"))
    )
    (net (code "529") (name "/v11_6") (class "Default")
      (node (ref "H5") (pin "55") (pinfunction "55_55") (pintype "unspecified"))
    )
    (net (code "530") (name "/v11_7") (class "Default")
      (node (ref "H5") (pin "53") (pinfunction "53_53") (pintype "unspecified"))
    )
    (net (code "531") (name "/v12_2") (class "Default")
      (node (ref "H5") (pin "51") (pinfunction "51_51") (pintype "unspecified"))
    )
    (net (code "532") (name "/v12_3") (class "Default")
      (node (ref "H5") (pin "49") (pinfunction "49_49") (pintype "unspecified"))
    )
    (net (code "533") (name "/v12_4") (class "Default")
      (node (ref "H5") (pin "47") (pinfunction "47_47") (pintype "unspecified"))
    )
    (net (code "534") (name "/v12_5") (class "Default")
      (node (ref "H5") (pin "45") (pinfunction "45_45") (pintype "unspecified"))
    )
    (net (code "535") (name "/v12_6") (class "Default")
      (node (ref "H5") (pin "43") (pinfunction "43_43") (pintype "unspecified"))
    )
    (net (code "536") (name "/v12_7") (class "Default")
      (node (ref "H5") (pin "41") (pinfunction "41_41") (pintype "unspecified"))
    )
    (net (code "537") (name "/v13_2") (class "Default")
      (node (ref "H5") (pin "39") (pinfunction "39_39") (pintype "unspecified"))
    )
    (net (code "538") (name "/v13_3") (class "Default")
      (node (ref "H5") (pin "37") (pinfunction "37_37") (pintype "unspecified"))
    )
    (net (code "539") (name "/v13_4") (class "Default")
      (node (ref "H5") (pin "35") (pinfunction "35_35") (pintype "unspecified"))
    )
    (net (code "540") (name "/v13_5") (class "Default")
      (node (ref "H5") (pin "33") (pinfunction "33_33") (pintype "unspecified"))
    )
    (net (code "541") (name "/v13_6") (class "Default")
      (node (ref "H5") (pin "31") (pinfunction "31_31") (pintype "unspecified"))
    )
    (net (code "542") (name "/v13_7") (class "Default")
      (node (ref "H5") (pin "29") (pinfunction "29_29") (pintype "unspecified"))
    )
    (net (code "543") (name "/v14_2") (class "Default")
      (node (ref "H5") (pin "27") (pinfunction "27_27") (pintype "unspecified"))
    )
    (net (code "544") (name "/v14_3") (class "Default")
      (node (ref "H5") (pin "25") (pinfunction "25_25") (pintype "unspecified"))
    )
    (net (code "545") (name "/v14_4") (class "Default")
      (node (ref "H5") (pin "23") (pinfunction "23_23") (pintype "unspecified"))
    )
    (net (code "546") (name "/v14_5") (class "Default")
      (node (ref "H5") (pin "21") (pinfunction "21_21") (pintype "unspecified"))
    )
    (net (code "547") (name "/v14_6") (class "Default")
      (node (ref "H5") (pin "19") (pinfunction "19_19") (pintype "unspecified"))
    )
    (net (code "548") (name "/v14_7") (class "Default")
      (node (ref "H5") (pin "17") (pinfunction "17_17") (pintype "unspecified"))
    )
    (net (code "549") (name "/v15_2") (class "Default")
      (node (ref "H5") (pin "15") (pinfunction "15_15") (pintype "unspecified"))
    )
    (net (code "550") (name "/v15_3") (class "Default")
      (node (ref "H5") (pin "13") (pinfunction "13_13") (pintype "unspecified"))
    )
    (net (code "551") (name "/v15_4") (class "Default")
      (node (ref "H5") (pin "11") (pinfunction "11_11") (pintype "unspecified"))
    )
    (net (code "552") (name "/v15_5") (class "Default")
      (node (ref "H5") (pin "9") (pinfunction "9_9") (pintype "unspecified"))
    )
    (net (code "553") (name "/v15_6") (class "Default")
      (node (ref "H5") (pin "7") (pinfunction "7_7") (pintype "unspecified"))
    )
    (net (code "554") (name "/v15_7") (class "Default")
      (node (ref "H5") (pin "5") (pinfunction "5_5") (pintype "unspecified"))
    )
    (net (code "555") (name "/v16_2") (class "Default")
      (node (ref "H5") (pin "3") (pinfunction "3_3") (pintype "unspecified"))
    )
    (net (code "556") (name "/v16_3") (class "Default")
      (node (ref "H5") (pin "1") (pinfunction "1_1") (pintype "unspecified"))
    )
    (net (code "557") (name "/v16_4") (class "Default")
      (node (ref "H5") (pin "34") (pinfunction "34_34") (pintype "unspecified"))
    )
    (net (code "558") (name "/v16_5") (class "Default")
      (node (ref "H5") (pin "64") (pinfunction "64_64") (pintype "unspecified"))
    )
    (net (code "559") (name "/v16_6") (class "Default")
      (node (ref "H5") (pin "62") (pinfunction "62_62") (pintype "unspecified"))
    )
    (net (code "560") (name "/v16_7") (class "Default")
      (node (ref "H5") (pin "60") (pinfunction "60_60") (pintype "unspecified"))
    )
    (net (code "561") (name "/v17_2") (class "Default")
      (node (ref "H5") (pin "58") (pinfunction "58_58") (pintype "unspecified"))
    )
    (net (code "562") (name "/v17_3") (class "Default")
      (node (ref "H5") (pin "56") (pinfunction "56_56") (pintype "unspecified"))
    )
    (net (code "563") (name "/v17_4") (class "Default")
      (node (ref "H5") (pin "54") (pinfunction "54_54") (pintype "unspecified"))
    )
    (net (code "564") (name "/v17_5") (class "Default")
      (node (ref "H5") (pin "52") (pinfunction "52_52") (pintype "unspecified"))
    )
    (net (code "565") (name "/v17_6") (class "Default")
      (node (ref "H5") (pin "50") (pinfunction "50_50") (pintype "unspecified"))
    )
    (net (code "566") (name "/v17_7") (class "Default")
      (node (ref "H5") (pin "48") (pinfunction "48_48") (pintype "unspecified"))
    )
    (net (code "567") (name "/v18_2") (class "Default")
      (node (ref "H5") (pin "46") (pinfunction "46_46") (pintype "unspecified"))
    )
    (net (code "568") (name "/v18_3") (class "Default")
      (node (ref "H5") (pin "44") (pinfunction "44_44") (pintype "unspecified"))
    )
    (net (code "569") (name "/v18_4") (class "Default")
      (node (ref "H5") (pin "42") (pinfunction "42_42") (pintype "unspecified"))
    )
    (net (code "570") (name "/v18_5") (class "Default")
      (node (ref "H5") (pin "40") (pinfunction "40_40") (pintype "unspecified"))
    )
    (net (code "571") (name "/v18_6") (class "Default")
      (node (ref "H5") (pin "38") (pinfunction "38_38") (pintype "unspecified"))
    )
    (net (code "572") (name "/v18_7") (class "Default")
      (node (ref "H5") (pin "36") (pinfunction "36_36") (pintype "unspecified"))
    )
    (net (code "573") (name "/v_msr_to_ADC") (class "Default")
      (node (ref "U52") (pin "5") (pinfunction "AIN_5") (pintype "unspecified"))
      (node (ref "U54") (pin "6") (pinfunction "OUT_6") (pintype "unspecified"))
    )
    (net (code "574") (name "/v_stab") (class "Default")
      (node (ref "C112") (pin "1") (pinfunction "1_1") (pintype "unspecified"))
      (node (ref "C116") (pin "2") (pinfunction "2_2") (pintype "unspecified"))
      (node (ref "R97") (pin "1") (pinfunction "1_1") (pintype "unspecified"))
      (node (ref "U54") (pin "7") (pinfunction "+VS_7") (pintype "unspecified"))
    )
    (net (code "575") (name "AGND") (class "Default")
      (node (ref "BT1") (pin "2") (pinfunction "-_2") (pintype "passive"))
      (node (ref "C1") (pin "2") (pinfunction "2_2") (pintype "input"))
      (node (ref "C10") (pin "2") (pinfunction "2_2") (pintype "input"))
      (node (ref "C100") (pin "2") (pinfunction "2_2") (pintype "unspecified"))
      (node (ref "C103") (pin "2") (pinfunction "2_2") (pintype "unspecified"))
      (node (ref "C105") (pin "2") (pinfunction "2_2") (pintype "unspecified"))
      (node (ref "C106") (pin "1") (pinfunction "1_1") (pintype "unspecified"))
      (node (ref "C107") (pin "2") (pinfunction "2_2") (pintype "unspecified"))
      (node (ref "C108") (pin "1") (pinfunction "1_1") (pintype "unspecified"))
      (node (ref "C11") (pin "2") (pinfunction "2_2") (pintype "unspecified"))
      (node (ref "C112") (pin "2") (pinfunction "2_2") (pintype "unspecified"))
      (node (ref "C116") (pin "1") (pinfunction "1_1") (pintype "unspecified"))
      (node (ref "C12") (pin "2") (pinfunction "2_2") (pintype "input"))
      (node (ref "C131") (pin "2") (pinfunction "2_2") (pintype "unspecified"))
      (node (ref "C132") (pin "2") (pinfunction "2_2") (pintype "unspecified"))
      (node (ref "C139") (pin "2") (pinfunction "2_2") (pintype "unspecified"))
      (node (ref "C140") (pin "2") (pinfunction "2_2") (pintype "unspecified"))
      (node (ref "C141") (pin "1") (pinfunction "1_1") (pintype "unspecified"))
      (node (ref "C19") (pin "2") (pinfunction "2_2") (pintype "input"))
      (node (ref "C2") (pin "2") (pinfunction "2_2") (pintype "input"))
      (node (ref "C20") (pin "1") (pinfunction "1_1") (pintype "unspecified"))
      (node (ref "C21") (pin "2") (pinfunction "2_2") (pintype "unspecified"))
      (node (ref "C22") (pin "2") (pinfunction "2_2") (pintype "unspecified"))
      (node (ref "C23") (pin "2") (pinfunction "2_2") (pintype "unspecified"))
      (node (ref "C24") (pin "2") (pinfunction "2_2") (pintype "unspecified"))
      (node (ref "C25") (pin "2") (pinfunction "2_2") (pintype "unspecified"))
      (node (ref "C26") (pin "2") (pinfunction "2_2") (pintype "unspecified"))
      (node (ref "C27") (pin "2") (pinfunction "2_2") (pintype "unspecified"))
      (node (ref "C28") (pin "2") (pinfunction "2_2") (pintype "unspecified"))
      (node (ref "C29") (pin "2") (pinfunction "2_2") (pintype "unspecified"))
      (node (ref "C3") (pin "2") (pinfunction "2_2") (pintype "input"))
      (node (ref "C30") (pin "2") (pinfunction "2_2") (pintype "unspecified"))
      (node (ref "C31") (pin "2") (pinfunction "2_2") (pintype "unspecified"))
      (node (ref "C32") (pin "2") (pinfunction "2_2") (pintype "unspecified"))
      (node (ref "C33") (pin "2") (pinfunction "2_2") (pintype "unspecified"))
      (node (ref "C34") (pin "2") (pinfunction "2_2") (pintype "unspecified"))
      (node (ref "C35") (pin "2") (pinfunction "2_2") (pintype "unspecified"))
      (node (ref "C36") (pin "2") (pinfunction "2_2") (pintype "unspecified"))
      (node (ref "C37") (pin "2") (pinfunction "2_2") (pintype "unspecified"))
      (node (ref "C38") (pin "2") (pinfunction "2_2") (pintype "unspecified"))
      (node (ref "C39") (pin "2") (pinfunction "2_2") (pintype "unspecified"))
      (node (ref "C4") (pin "2") (pinfunction "2_2") (pintype "input"))
      (node (ref "C40") (pin "2") (pinfunction "2_2") (pintype "unspecified"))
      (node (ref "C41") (pin "2") (pinfunction "2_2") (pintype "unspecified"))
      (node (ref "C42") (pin "2") (pinfunction "2_2") (pintype "unspecified"))
      (node (ref "C43") (pin "2") (pinfunction "2_2") (pintype "unspecified"))
      (node (ref "C44") (pin "2") (pinfunction "2_2") (pintype "unspecified"))
      (node (ref "C45") (pin "2") (pinfunction "2_2") (pintype "unspecified"))
      (node (ref "C46") (pin "2") (pinfunction "2_2") (pintype "unspecified"))
      (node (ref "C47") (pin "2") (pinfunction "2_2") (pintype "unspecified"))
      (node (ref "C48") (pin "2") (pinfunction "2_2") (pintype "unspecified"))
      (node (ref "C49") (pin "2") (pinfunction "2_2") (pintype "unspecified"))
      (node (ref "C5") (pin "2") (pinfunction "2_2") (pintype "unspecified"))
      (node (ref "C50") (pin "2") (pinfunction "2_2") (pintype "unspecified"))
      (node (ref "C51") (pin "2") (pinfunction "2_2") (pintype "unspecified"))
      (node (ref "C52") (pin "2") (pinfunction "2_2") (pintype "unspecified"))
      (node (ref "C53") (pin "2") (pinfunction "2_2") (pintype "unspecified"))
      (node (ref "C54") (pin "2") (pinfunction "2_2") (pintype "unspecified"))
      (node (ref "C55") (pin "2") (pinfunction "2_2") (pintype "unspecified"))
      (node (ref "C56") (pin "2") (pinfunction "2_2") (pintype "unspecified"))
      (node (ref "C57") (pin "2") (pinfunction "2_2") (pintype "unspecified"))
      (node (ref "C58") (pin "1") (pinfunction "1_1") (pintype "input"))
      (node (ref "C59") (pin "1") (pinfunction "1_1") (pintype "unspecified"))
      (node (ref "C6") (pin "2") (pinfunction "2_2") (pintype "unspecified"))
      (node (ref "C7") (pin "2") (pinfunction "2_2") (pintype "input"))
      (node (ref "C76") (pin "2") (pinfunction "2_2") (pintype "input"))
      (node (ref "C8") (pin "2") (pinfunction "2_2") (pintype "input"))
      (node (ref "C9") (pin "2") (pinfunction "2_2") (pintype "input"))
      (node (ref "C95") (pin "2") (pinfunction "2_2") (pintype "unspecified"))
      (node (ref "C96") (pin "2") (pinfunction "2_2") (pintype "unspecified"))
      (node (ref "C98") (pin "1") (pinfunction "1_1") (pintype "unspecified"))
      (node (ref "C99") (pin "1") (pinfunction "1_1") (pintype "unspecified"))
      (node (ref "CN1") (pin "1") (pinfunction "1_1") (pintype "unspecified"))
      (node (ref "CN1") (pin "3") (pinfunction "3_3") (pintype "unspecified"))
      (node (ref "CN1") (pin "5") (pinfunction "5_5") (pintype "unspecified"))
      (node (ref "D1") (pin "1") (pinfunction "K_1") (pintype "unspecified"))
      (node (ref "D10") (pin "1") (pinfunction "K_1") (pintype "unspecified"))
      (node (ref "D11") (pin "1") (pinfunction "K_1") (pintype "unspecified"))
      (node (ref "D12") (pin "1") (pinfunction "K_1") (pintype "unspecified"))
      (node (ref "D13") (pin "1") (pinfunction "K_1") (pintype "unspecified"))
      (node (ref "D14") (pin "1") (pinfunction "K_1") (pintype "unspecified"))
      (node (ref "D15") (pin "1") (pinfunction "K_1") (pintype "unspecified"))
      (node (ref "D16") (pin "1") (pinfunction "K_1") (pintype "unspecified"))
      (node (ref "D17") (pin "1") (pinfunction "K_1") (pintype "unspecified"))
      (node (ref "D18") (pin "1") (pinfunction "K_1") (pintype "unspecified"))
      (node (ref "D2") (pin "1") (pinfunction "K_1") (pintype "unspecified"))
      (node (ref "D3") (pin "1") (pinfunction "K_1") (pintype "unspecified"))
      (node (ref "D37") (pin "2") (pinfunction "A_2") (pintype "unspecified"))
      (node (ref "D38") (pin "2") (pinfunction "A_2") (pintype "unspecified"))
      (node (ref "D4") (pin "1") (pinfunction "K_1") (pintype "unspecified"))
      (node (ref "D42") (pin "2") (pinfunction "2_2") (pintype "unspecified"))
      (node (ref "D47") (pin "2") (pinfunction "A_2") (pintype "unspecified"))
      (node (ref "D48") (pin "1") (pinfunction "1_1") (pintype "unspecified"))
      (node (ref "D5") (pin "1") (pinfunction "K_1") (pintype "unspecified"))
      (node (ref "D50") (pin "2") (pinfunction "A_2") (pintype "unspecified"))
      (node (ref "D6") (pin "1") (pinfunction "K_1") (pintype "unspecified"))
      (node (ref "D7") (pin "1") (pinfunction "K_1") (pintype "unspecified"))
      (node (ref "D8") (pin "1") (pinfunction "K_1") (pintype "unspecified"))
      (node (ref "D9") (pin "1") (pinfunction "K_1") (pintype "unspecified"))
      (node (ref "FPC1") (pin "15") (pinfunction "15_15") (pintype "unspecified"))
      (node (ref "FPC1") (pin "16") (pinfunction "16_16") (pintype "unspecified"))
      (node (ref "FPC1") (pin "2") (pinfunction "2_2") (pintype "unspecified"))
      (node (ref "H2") (pin "5") (pinfunction "5_5") (pintype "unspecified"))
      (node (ref "H3") (pin "2") (pinfunction "2_2") (pintype "unspecified"))
      (node (ref "H3") (pin "4") (pinfunction "4_4") (pintype "unspecified"))
      (node (ref "KEY1") (pin "1") (pinfunction "1_1") (pintype "unspecified"))
      (node (ref "KEY2") (pin "1") (pinfunction "1_1") (pintype "unspecified"))
      (node (ref "LED1") (pin "2") (pinfunction "2_2") (pintype "unspecified"))
      (node (ref "LED2") (pin "2") (pinfunction "2_2") (pintype "unspecified"))
      (node (ref "LED3") (pin "2") (pinfunction "2_2") (pintype "unspecified"))
      (node (ref "LED4") (pin "2") (pinfunction "2_2") (pintype "unspecified"))
      (node (ref "LED5") (pin "2") (pinfunction "2_2") (pintype "unspecified"))
      (node (ref "LED6") (pin "2") (pinfunction "2_2") (pintype "unspecified"))
      (node (ref "LED7") (pin "2") (pinfunction "2_2") (pintype "unspecified"))
      (node (ref "Q23") (pin "2") (pinfunction "S_2") (pintype "unspecified"))
      (node (ref "R1") (pin "1") (pinfunction "1_1") (pintype "unspecified"))
      (node (ref "R100") (pin "1") (pinfunction "1_1") (pintype "unspecified"))
      (node (ref "R102") (pin "1") (pinfunction "1_1") (pintype "unspecified"))
      (node (ref "R103") (pin "1") (pinfunction "1_1") (pintype "unspecified"))
      (node (ref "R104") (pin "1") (pinfunction "1_1") (pintype "unspecified"))
      (node (ref "R2") (pin "1") (pinfunction "1_1") (pintype "unspecified"))
      (node (ref "R3") (pin "1") (pinfunction "1_1") (pintype "unspecified"))
      (node (ref "R32") (pin "2") (pinfunction "2_2") (pintype "unspecified"))
      (node (ref "R33") (pin "2") (pinfunction "2_2") (pintype "unspecified"))
      (node (ref "R34") (pin "2") (pinfunction "2_2") (pintype "unspecified"))
      (node (ref "R35") (pin "2") (pinfunction "2_2") (pintype "unspecified"))
      (node (ref "R36") (pin "2") (pinfunction "2_2") (pintype "unspecified"))
      (node (ref "R37") (pin "2") (pinfunction "2_2") (pintype "unspecified"))
      (node (ref "R38") (pin "2") (pinfunction "2_2") (pintype "unspecified"))
      (node (ref "R39") (pin "2") (pinfunction "2_2") (pintype "unspecified"))
      (node (ref "R4") (pin "1") (pinfunction "1_1") (pintype "unspecified"))
      (node (ref "R40") (pin "2") (pinfunction "2_2") (pintype "unspecified"))
      (node (ref "R41") (pin "2") (pinfunction "2_2") (pintype "unspecified"))
      (node (ref "R42") (pin "2") (pinfunction "2_2") (pintype "unspecified"))
      (node (ref "R43") (pin "2") (pinfunction "2_2") (pintype "unspecified"))
      (node (ref "R44") (pin "2") (pinfunction "2_2") (pintype "unspecified"))
      (node (ref "R45") (pin "2") (pinfunction "2_2") (pintype "unspecified"))
      (node (ref "R46") (pin "2") (pinfunction "2_2") (pintype "unspecified"))
      (node (ref "R47") (pin "2") (pinfunction "2_2") (pintype "unspecified"))
      (node (ref "R48") (pin "2") (pinfunction "2_2") (pintype "unspecified"))
      (node (ref "R49") (pin "2") (pinfunction "2_2") (pintype "unspecified"))
      (node (ref "R72") (pin "1") (pinfunction "1_1") (pintype "unspecified"))
      (node (ref "R96") (pin "2") (pinfunction "2_2") (pintype "unspecified"))
      (node (ref "R98") (pin "1") (pinfunction "1_1") (pintype "unspecified"))
      (node (ref "R99") (pin "2") (pinfunction "2_2") (pintype "input"))
      (node (ref "U10") (pin "5") (pinfunction "GND_5") (pintype "unspecified"))
      (node (ref "U11") (pin "5") (pinfunction "GND_5") (pintype "unspecified"))
      (node (ref "U12") (pin "5") (pinfunction "GND_5") (pintype "unspecified"))
      (node (ref "U13") (pin "5") (pinfunction "GND_5") (pintype "unspecified"))
      (node (ref "U14") (pin "5") (pinfunction "GND_5") (pintype "unspecified"))
      (node (ref "U15") (pin "5") (pinfunction "GND_5") (pintype "unspecified"))
      (node (ref "U16") (pin "5") (pinfunction "GND_5") (pintype "unspecified"))
      (node (ref "U17") (pin "5") (pinfunction "GND_5") (pintype "unspecified"))
      (node (ref "U18") (pin "5") (pinfunction "GND_5") (pintype "unspecified"))
      (node (ref "U19") (pin "5") (pinfunction "GND_5") (pintype "unspecified"))
      (node (ref "U20") (pin "5") (pinfunction "GND_5") (pintype "unspecified"))
      (node (ref "U21") (pin "5") (pinfunction "GND_5") (pintype "unspecified"))
      (node (ref "U22") (pin "5") (pinfunction "GND_5") (pintype "unspecified"))
      (node (ref "U23") (pin "5") (pinfunction "GND_5") (pintype "unspecified"))
      (node (ref "U24") (pin "5") (pinfunction "GND_5") (pintype "unspecified"))
      (node (ref "U25") (pin "5") (pinfunction "GND_5") (pintype "unspecified"))
      (node (ref "U26") (pin "5") (pinfunction "GND_5") (pintype "unspecified"))
      (node (ref "U27") (pin "5") (pinfunction "GND_5") (pintype "unspecified"))
      (node (ref "U28") (pin "3") (pinfunction "GND_3") (pintype "unspecified"))
      (node (ref "U28") (pin "5") (pinfunction "ON/OFF_5") (pintype "unspecified"))
      (node (ref "U28") (pin "6") (pinfunction "PAD_6") (pintype "unspecified"))
      (node (ref "U39") (pin "1") (pinfunction "GND_1") (pintype "unspecified"))
      (node (ref "U40") (pin "3") (pinfunction "B0_3") (pintype "unspecified"))
      (node (ref "U41") (pin "3") (pinfunction "B0_3") (pintype "unspecified"))
      (node (ref "U5") (pin "11") (pinfunction "MODE_11") (pintype "unspecified"))
      (node (ref "U52") (pin "4") (pinfunction "AGND_4") (pintype "passive"))
      (node (ref "U52") (pin "8") (pinfunction "AGND_8") (pintype "passive"))
      (node (ref "U54") (pin "4") (pinfunction "-VS_4") (pintype "unspecified"))
      (node (ref "U6") (pin "4") (pinfunction "4_4") (pintype "unspecified"))
      (node (ref "U7") (pin "10") (pinfunction "GND_10") (pintype "unspecified"))
      (node (ref "U7") (pin "8") (pinfunction "AIN7_8") (pintype "unspecified"))
      (node (ref "U7") (pin "9") (pinfunction "AIN8_9") (pintype "unspecified"))
      (node (ref "U8") (pin "10") (pinfunction "GND_10") (pintype "unspecified"))
    )
    (net (code "576") (name "DGND") (class "Default")
      (node (ref "C101") (pin "1") (pinfunction "1_1") (pintype "unspecified"))
      (node (ref "C102") (pin "1") (pinfunction "1_1") (pintype "unspecified"))
      (node (ref "C104") (pin "1") (pinfunction "1_1") (pintype "unspecified"))
      (node (ref "C109") (pin "1") (pinfunction "1_1") (pintype "unspecified"))
      (node (ref "C110") (pin "1") (pinfunction "1_1") (pintype "unspecified"))
      (node (ref "C111") (pin "1") (pinfunction "1_1") (pintype "unspecified"))
      (node (ref "C113") (pin "1") (pinfunction "1_1") (pintype "unspecified"))
      (node (ref "C114") (pin "1") (pinfunction "1_1") (pintype "unspecified"))
      (node (ref "C115") (pin "1") (pinfunction "1_1") (pintype "unspecified"))
      (node (ref "C117") (pin "2") (pinfunction "2_2") (pintype "unspecified"))
      (node (ref "C118") (pin "2") (pinfunction "2_2") (pintype "unspecified"))
      (node (ref "C119") (pin "2") (pinfunction "2_2") (pintype "unspecified"))
      (node (ref "C120") (pin "1") (pinfunction "1_1") (pintype "unspecified"))
      (node (ref "C121") (pin "1") (pinfunction "1_1") (pintype "unspecified"))
      (node (ref "C122") (pin "1") (pinfunction "1_1") (pintype "unspecified"))
      (node (ref "C123") (pin "1") (pinfunction "1_1") (pintype "unspecified"))
      (node (ref "C124") (pin "1") (pinfunction "1_1") (pintype "unspecified"))
      (node (ref "C125") (pin "1") (pinfunction "1_1") (pintype "unspecified"))
      (node (ref "C126") (pin "1") (pinfunction "1_1") (pintype "unspecified"))
      (node (ref "C127") (pin "1") (pinfunction "1_1") (pintype "unspecified"))
      (node (ref "C128") (pin "2") (pinfunction "2_2") (pintype "unspecified"))
      (node (ref "C129") (pin "2") (pinfunction "2_2") (pintype "unspecified"))
      (node (ref "C130") (pin "2") (pinfunction "2_2") (pintype "unspecified"))
      (node (ref "C133") (pin "1") (pinfunction "1_1") (pintype "input"))
      (node (ref "C134") (pin "1") (pinfunction "1_1") (pintype "input"))
      (node (ref "C135") (pin "1") (pinfunction "1_1") (pintype "input"))
      (node (ref "C136") (pin "1") (pinfunction "1_1") (pintype "unspecified"))
      (node (ref "C138") (pin "1") (pinfunction "1_1") (pintype "unspecified"))
      (node (ref "C142") (pin "1") (pinfunction "1_1") (pintype "unspecified"))
      (node (ref "C16") (pin "1") (pinfunction "1_1") (pintype "unspecified"))
      (node (ref "C17") (pin "1") (pinfunction "1_1") (pintype "unspecified"))
      (node (ref "C60") (pin "2") (pinfunction "2_2") (pintype "unspecified"))
      (node (ref "C61") (pin "2") (pinfunction "2_2") (pintype "unspecified"))
      (node (ref "C62") (pin "2") (pinfunction "2_2") (pintype "unspecified"))
      (node (ref "C63") (pin "2") (pinfunction "2_2") (pintype "unspecified"))
      (node (ref "C64") (pin "2") (pinfunction "2_2") (pintype "unspecified"))
      (node (ref "C65") (pin "2") (pinfunction "2_2") (pintype "unspecified"))
      (node (ref "C66") (pin "2") (pinfunction "2_2") (pintype "unspecified"))
      (node (ref "C67") (pin "2") (pinfunction "2_2") (pintype "unspecified"))
      (node (ref "C68") (pin "2") (pinfunction "2_2") (pintype "unspecified"))
      (node (ref "C69") (pin "2") (pinfunction "2_2") (pintype "unspecified"))
      (node (ref "C70") (pin "2") (pinfunction "2_2") (pintype "unspecified"))
      (node (ref "C71") (pin "2") (pinfunction "2_2") (pintype "unspecified"))
      (node (ref "C72") (pin "2") (pinfunction "2_2") (pintype "unspecified"))
      (node (ref "C73") (pin "2") (pinfunction "2_2") (pintype "unspecified"))
      (node (ref "C74") (pin "2") (pinfunction "2_2") (pintype "unspecified"))
      (node (ref "C75") (pin "2") (pinfunction "2_2") (pintype "unspecified"))
      (node (ref "C79") (pin "1") (pinfunction "1_1") (pintype "unspecified"))
      (node (ref "C80") (pin "1") (pinfunction "1_1") (pintype "unspecified"))
      (node (ref "C81") (pin "1") (pinfunction "1_1") (pintype "unspecified"))
      (node (ref "C82") (pin "1") (pinfunction "1_1") (pintype "unspecified"))
      (node (ref "C83") (pin "1") (pinfunction "1_1") (pintype "unspecified"))
      (node (ref "C84") (pin "1") (pinfunction "1_1") (pintype "unspecified"))
      (node (ref "C85") (pin "1") (pinfunction "1_1") (pintype "unspecified"))
      (node (ref "C86") (pin "1") (pinfunction "1_1") (pintype "unspecified"))
      (node (ref "C87") (pin "1") (pinfunction "1_1") (pintype "unspecified"))
      (node (ref "C88") (pin "1") (pinfunction "1_1") (pintype "unspecified"))
      (node (ref "C89") (pin "1") (pinfunction "1_1") (pintype "unspecified"))
      (node (ref "C90") (pin "1") (pinfunction "1_1") (pintype "unspecified"))
      (node (ref "C91") (pin "1") (pinfunction "1_1") (pintype "unspecified"))
      (node (ref "C92") (pin "1") (pinfunction "1_1") (pintype "unspecified"))
      (node (ref "C93") (pin "1") (pinfunction "1_1") (pintype "unspecified"))
      (node (ref "C94") (pin "1") (pinfunction "1_1") (pintype "unspecified"))
      (node (ref "C97") (pin "2") (pinfunction "2_2") (pintype "input"))
      (node (ref "R50") (pin "2") (pinfunction "2_2") (pintype "input"))
      (node (ref "U29") (pin "7") (pinfunction "GND_7") (pintype "unspecified"))
      (node (ref "U31") (pin "2") (pinfunction "GND_2") (pintype "unspecified"))
      (node (ref "U31") (pin "3") (pinfunction "B0_3") (pintype "unspecified"))
      (node (ref "U32") (pin "8") (pinfunction "GND_8") (pintype "unspecified"))
      (node (ref "U33") (pin "8") (pinfunction "GND_8") (pintype "unspecified"))
      (node (ref "U34") (pin "8") (pinfunction "GND_8") (pintype "unspecified"))
      (node (ref "U35") (pin "8") (pinfunction "GND_8") (pintype "unspecified"))
      (node (ref "U36") (pin "8") (pinfunction "GND_8") (pintype "unspecified"))
      (node (ref "U37") (pin "8") (pinfunction "GND_8") (pintype "unspecified"))
      (node (ref "U38") (pin "8") (pinfunction "GND_8") (pintype "unspecified"))
      (node (ref "U40") (pin "2") (pinfunction "GND_2") (pintype "unspecified"))
      (node (ref "U41") (pin "2") (pinfunction "GND_2") (pintype "unspecified"))
      (node (ref "U42") (pin "8") (pinfunction "GND_8") (pintype "unspecified"))
      (node (ref "U43") (pin "8") (pinfunction "GND_8") (pintype "unspecified"))
      (node (ref "U44") (pin "8") (pinfunction "GND_8") (pintype "unspecified"))
      (node (ref "U45") (pin "8") (pinfunction "GND_8") (pintype "unspecified"))
      (node (ref "U46") (pin "8") (pinfunction "GND_8") (pintype "unspecified"))
      (node (ref "U47") (pin "8") (pinfunction "GND_8") (pintype "unspecified"))
      (node (ref "U48") (pin "2") (pinfunction "Y6_2") (pintype "unspecified"))
      (node (ref "U48") (pin "4") (pinfunction "Y7_4") (pintype "unspecified"))
      (node (ref "U48") (pin "5") (pinfunction "Y5_5") (pintype "unspecified"))
      (node (ref "U48") (pin "8") (pinfunction "GND_8") (pintype "unspecified"))
      (node (ref "U49") (pin "12") (pinfunction "GND_12") (pintype "unspecified"))
      (node (ref "U49") (pin "27") (pinfunction "VSS_27") (pintype "unspecified"))
      (node (ref "U5") (pin "10") (pinfunction "GND_10") (pintype "passive"))
      (node (ref "U5") (pin "6") (pinfunction "COM_6") (pintype "passive"))
      (node (ref "U50") (pin "9") (pinfunction "GND_9") (pintype "passive"))
      (node (ref "U51") (pin "9") (pinfunction "GND_9") (pintype "passive"))
      (node (ref "U52") (pin "2") (pinfunction "DGND_2") (pintype "passive"))
      (node (ref "U53") (pin "12") (pinfunction "GND_12") (pintype "unspecified"))
      (node (ref "U53") (pin "27") (pinfunction "VSS_27") (pintype "unspecified"))
      (node (ref "U55") (pin "9") (pinfunction "GND_9") (pintype "passive"))
      (node (ref "U56") (pin "2") (pinfunction "GND_2") (pintype "unspecified"))
      (node (ref "U56") (pin "3") (pinfunction "GND_3") (pintype "unspecified"))
      (node (ref "U57") (pin "2") (pinfunction "GND_2") (pintype "unspecified"))
      (node (ref "U57") (pin "3") (pinfunction "GND_3") (pintype "unspecified"))
      (node (ref "U58") (pin "2") (pinfunction "GND_2") (pintype "unspecified"))
      (node (ref "U58") (pin "3") (pinfunction "GND_3") (pintype "unspecified"))
      (node (ref "U59") (pin "2") (pinfunction "GND_2") (pintype "unspecified"))
      (node (ref "U59") (pin "3") (pinfunction "GND_3") (pintype "unspecified"))
      (node (ref "U60") (pin "23") (pinfunction "VSS_23") (pintype "unspecified"))
      (node (ref "U60") (pin "35") (pinfunction "VSS_35") (pintype "unspecified"))
      (node (ref "U60") (pin "47") (pinfunction "VSS_47") (pintype "unspecified"))
      (node (ref "U60") (pin "49") (pinfunction "EP_49") (pintype "unspecified"))
      (node (ref "U60") (pin "8") (pinfunction "VSSA/VREF-_8") (pintype "unspecified"))
      (node (ref "U7") (pin "13") (pinfunction "REF-_13") (pintype "unspecified"))
      (node (ref "U8") (pin "13") (pinfunction "REF-_13") (pintype "unspecified"))
      (node (ref "U9") (pin "8") (pinfunction "GND_8") (pintype "unspecified"))
    )
    (net (code "577") (name "Net-(C20-Pad2)") (class "Default")
      (node (ref "C20") (pin "2") (pinfunction "2_2") (pintype "unspecified"))
      (node (ref "R68") (pin "1") (pinfunction "1_1") (pintype "input"))
    )
    (net (code "578") (name "Net-(C137-Pad1)") (class "Default")
      (node (ref "C137") (pin "1") (pinfunction "1_1") (pintype "unspecified"))
      (node (ref "R100") (pin "2") (pinfunction "2_2") (pintype "unspecified"))
    )
    (net (code "579") (name "Net-(D39-A)") (class "Default")
      (node (ref "D39") (pin "2") (pinfunction "A_2") (pintype "unspecified"))
      (node (ref "Q21") (pin "2") (pinfunction "S_2") (pintype "unspecified"))
      (node (ref "R63") (pin "2") (pinfunction "2_2") (pintype "unspecified"))
    )
    (net (code "580") (name "Net-(D43-A)") (class "Default")
      (node (ref "D43") (pin "2") (pinfunction "A_2") (pintype "unspecified"))
      (node (ref "D44") (pin "1") (pinfunction "C_1") (pintype "unspecified"))
      (node (ref "Q22") (pin "5") (pinfunction "D2_5") (pintype "unspecified"))
      (node (ref "Q22") (pin "6") (pinfunction "D2_6") (pintype "unspecified"))
      (node (ref "Q22") (pin "7") (pinfunction "D1_7") (pintype "unspecified"))
      (node (ref "Q22") (pin "8") (pinfunction "D1_8") (pintype "unspecified"))
      (node (ref "U30") (pin "2") (pinfunction "2_2") (pintype "unspecified"))
    )
    (net (code "581") (name "Net-(D45-A)") (class "Default")
      (node (ref "C77") (pin "2") (pinfunction "2_2") (pintype "unspecified"))
      (node (ref "D45") (pin "2") (pinfunction "A_2") (pintype "unspecified"))
      (node (ref "Q22") (pin "4") (pinfunction "G2_4") (pintype "unspecified"))
      (node (ref "R69") (pin "2") (pinfunction "2_2") (pintype "unspecified"))
    )
    (net (code "582") (name "Net-(D46-C)") (class "Default")
      (node (ref "C78") (pin "2") (pinfunction "2_2") (pintype "unspecified"))
      (node (ref "D46") (pin "1") (pinfunction "C_1") (pintype "unspecified"))
      (node (ref "Q22") (pin "2") (pinfunction "G1_2") (pintype "unspecified"))
      (node (ref "R70") (pin "2") (pinfunction "2_2") (pintype "unspecified"))
    )
    (net (code "583") (name "Net-(D47-C)") (class "Default")
      (node (ref "D47") (pin "1") (pinfunction "C_1") (pintype "unspecified"))
      (node (ref "D49") (pin "1") (pinfunction "C_1") (pintype "unspecified"))
      (node (ref "F1") (pin "2") (pinfunction "2_2") (pintype "unspecified"))
      (node (ref "Q24") (pin "2") (pinfunction "D_2") (pintype "unspecified"))
      (node (ref "R68") (pin "2") (pinfunction "2_2") (pintype "input"))
      (node (ref "R73") (pin "2") (pinfunction "2_2") (pintype "input"))
    )
    (net (code "584") (name "Net-(D50-C)") (class "Default")
      (node (ref "D50") (pin "1") (pinfunction "C_1") (pintype "unspecified"))
      (node (ref "Q23") (pin "3") (pinfunction "D_3") (pintype "unspecified"))
      (node (ref "R74") (pin "1") (pinfunction "1_1") (pintype "unspecified"))
    )
    (net (code "585") (name "Net-(L1-Pad2)") (class "Default")
      (node (ref "L1") (pin "2") (pinfunction "2_2") (pintype "unspecified"))
      (node (ref "R64") (pin "2") (pinfunction "2_2") (pintype "unspecified"))
      (node (ref "U30") (pin "1") (pinfunction "1_1") (pintype "unspecified"))
    )
    (net (code "586") (name "Net-(LED1-Pad1)") (class "Default")
      (node (ref "LED1") (pin "1") (pinfunction "1_1") (pintype "unspecified"))
      (node (ref "R51") (pin "2") (pinfunction "2_2") (pintype "input"))
    )
    (net (code "587") (name "Net-(LED2-Pad1)") (class "Default")
      (node (ref "LED2") (pin "1") (pinfunction "1_1") (pintype "unspecified"))
      (node (ref "R52") (pin "2") (pinfunction "2_2") (pintype "input"))
    )
    (net (code "588") (name "Net-(LED3-Pad1)") (class "Default")
      (node (ref "LED3") (pin "1") (pinfunction "1_1") (pintype "unspecified"))
      (node (ref "R53") (pin "2") (pinfunction "2_2") (pintype "input"))
    )
    (net (code "589") (name "Net-(LED4-Pad1)") (class "Default")
      (node (ref "LED4") (pin "1") (pinfunction "1_1") (pintype "unspecified"))
      (node (ref "R54") (pin "2") (pinfunction "2_2") (pintype "input"))
    )
    (net (code "590") (name "Net-(LED5-Pad1)") (class "Default")
      (node (ref "LED5") (pin "1") (pinfunction "1_1") (pintype "unspecified"))
      (node (ref "R55") (pin "2") (pinfunction "2_2") (pintype "input"))
    )
    (net (code "591") (name "Net-(LED6-Pad1)") (class "Default")
      (node (ref "LED6") (pin "1") (pinfunction "1_1") (pintype "unspecified"))
      (node (ref "R56") (pin "2") (pinfunction "2_2") (pintype "input"))
    )
    (net (code "592") (name "Net-(LED7-Pad1)") (class "Default")
      (node (ref "LED7") (pin "1") (pinfunction "1_1") (pintype "unspecified"))
      (node (ref "R57") (pin "2") (pinfunction "2_2") (pintype "input"))
    )
    (net (code "593") (name "Net-(Q1-G)") (class "Default")
      (node (ref "Q1") (pin "1") (pinfunction "G_1") (pintype "unspecified"))
      (node (ref "R14") (pin "1") (pinfunction "1_1") (pintype "unspecified"))
      (node (ref "R32") (pin "1") (pinfunction "1_1") (pintype "unspecified"))
    )
    (net (code "594") (name "Net-(Q2-G)") (class "Default")
      (node (ref "Q2") (pin "1") (pinfunction "G_1") (pintype "unspecified"))
      (node (ref "R15") (pin "1") (pinfunction "1_1") (pintype "unspecified"))
      (node (ref "R33") (pin "1") (pinfunction "1_1") (pintype "unspecified"))
    )
    (net (code "595") (name "Net-(Q3-G)") (class "Default")
      (node (ref "Q3") (pin "1") (pinfunction "G_1") (pintype "unspecified"))
      (node (ref "R16") (pin "1") (pinfunction "1_1") (pintype "unspecified"))
      (node (ref "R34") (pin "1") (pinfunction "1_1") (pintype "unspecified"))
    )
    (net (code "596") (name "Net-(Q4-G)") (class "Default")
      (node (ref "Q4") (pin "1") (pinfunction "G_1") (pintype "unspecified"))
      (node (ref "R17") (pin "1") (pinfunction "1_1") (pintype "unspecified"))
      (node (ref "R35") (pin "1") (pinfunction "1_1") (pintype "unspecified"))
    )
    (net (code "597") (name "Net-(Q5-G)") (class "Default")
      (node (ref "Q5") (pin "1") (pinfunction "G_1") (pintype "unspecified"))
      (node (ref "R18") (pin "1") (pinfunction "1_1") (pintype "unspecified"))
      (node (ref "R36") (pin "1") (pinfunction "1_1") (pintype "unspecified"))
    )
    (net (code "598") (name "Net-(Q6-G)") (class "Default")
      (node (ref "Q6") (pin "1") (pinfunction "G_1") (pintype "unspecified"))
      (node (ref "R19") (pin "1") (pinfunction "1_1") (pintype "unspecified"))
      (node (ref "R37") (pin "1") (pinfunction "1_1") (pintype "unspecified"))
    )
    (net (code "599") (name "Net-(Q7-G)") (class "Default")
      (node (ref "Q7") (pin "1") (pinfunction "G_1") (pintype "unspecified"))
      (node (ref "R20") (pin "1") (pinfunction "1_1") (pintype "unspecified"))
      (node (ref "R38") (pin "1") (pinfunction "1_1") (pintype "unspecified"))
    )
    (net (code "600") (name "Net-(Q8-G)") (class "Default")
      (node (ref "Q8") (pin "1") (pinfunction "G_1") (pintype "unspecified"))
      (node (ref "R21") (pin "1") (pinfunction "1_1") (pintype "unspecified"))
      (node (ref "R39") (pin "1") (pinfunction "1_1") (pintype "unspecified"))
    )
    (net (code "601") (name "Net-(Q9-G)") (class "Default")
      (node (ref "Q9") (pin "1") (pinfunction "G_1") (pintype "unspecified"))
      (node (ref "R22") (pin "1") (pinfunction "1_1") (pintype "unspecified"))
      (node (ref "R40") (pin "1") (pinfunction "1_1") (pintype "unspecified"))
    )
    (net (code "602") (name "Net-(Q10-G)") (class "Default")
      (node (ref "Q10") (pin "1") (pinfunction "G_1") (pintype "unspecified"))
      (node (ref "R23") (pin "1") (pinfunction "1_1") (pintype "unspecified"))
      (node (ref "R41") (pin "1") (pinfunction "1_1") (pintype "unspecified"))
    )
    (net (code "603") (name "Net-(Q11-G)") (class "Default")
      (node (ref "Q11") (pin "1") (pinfunction "G_1") (pintype "unspecified"))
      (node (ref "R24") (pin "1") (pinfunction "1_1") (pintype "unspecified"))
      (node (ref "R42") (pin "1") (pinfunction "1_1") (pintype "unspecified"))
    )
    (net (code "604") (name "Net-(Q12-G)") (class "Default")
      (node (ref "Q12") (pin "1") (pinfunction "G_1") (pintype "unspecified"))
      (node (ref "R25") (pin "1") (pinfunction "1_1") (pintype "unspecified"))
      (node (ref "R43") (pin "1") (pinfunction "1_1") (pintype "unspecified"))
    )
    (net (code "605") (name "Net-(Q13-G)") (class "Default")
      (node (ref "Q13") (pin "1") (pinfunction "G_1") (pintype "unspecified"))
      (node (ref "R26") (pin "1") (pinfunction "1_1") (pintype "unspecified"))
      (node (ref "R44") (pin "1") (pinfunction "1_1") (pintype "unspecified"))
    )
    (net (code "606") (name "Net-(Q14-G)") (class "Default")
      (node (ref "Q14") (pin "1") (pinfunction "G_1") (pintype "unspecified"))
      (node (ref "R27") (pin "1") (pinfunction "1_1") (pintype "unspecified"))
      (node (ref "R45") (pin "1") (pinfunction "1_1") (pintype "unspecified"))
    )
    (net (code "607") (name "Net-(Q15-G)") (class "Default")
      (node (ref "Q15") (pin "1") (pinfunction "G_1") (pintype "unspecified"))
      (node (ref "R28") (pin "1") (pinfunction "1_1") (pintype "unspecified"))
      (node (ref "R46") (pin "1") (pinfunction "1_1") (pintype "unspecified"))
    )
    (net (code "608") (name "Net-(Q16-G)") (class "Default")
      (node (ref "Q16") (pin "1") (pinfunction "G_1") (pintype "unspecified"))
      (node (ref "R29") (pin "1") (pinfunction "1_1") (pintype "unspecified"))
      (node (ref "R47") (pin "1") (pinfunction "1_1") (pintype "unspecified"))
    )
    (net (code "609") (name "Net-(Q17-G)") (class "Default")
      (node (ref "Q17") (pin "1") (pinfunction "G_1") (pintype "unspecified"))
      (node (ref "R30") (pin "1") (pinfunction "1_1") (pintype "unspecified"))
      (node (ref "R48") (pin "1") (pinfunction "1_1") (pintype "unspecified"))
    )
    (net (code "610") (name "Net-(Q18-G)") (class "Default")
      (node (ref "Q18") (pin "1") (pinfunction "G_1") (pintype "unspecified"))
      (node (ref "R31") (pin "1") (pinfunction "1_1") (pintype "unspecified"))
      (node (ref "R49") (pin "1") (pinfunction "1_1") (pintype "unspecified"))
    )
    (net (code "611") (name "Net-(Q19-G)") (class "Default")
      (node (ref "Q19") (pin "3") (pinfunction "G_3") (pintype "unspecified"))
      (node (ref "R59") (pin "1") (pinfunction "1_1") (pintype "unspecified"))
      (node (ref "R61") (pin "2") (pinfunction "2_2") (pintype "unspecified"))
    )
    (net (code "612") (name "Net-(Q20-G)") (class "Default")
      (node (ref "Q20") (pin "3") (pinfunction "G_3") (pintype "unspecified"))
      (node (ref "R60") (pin "1") (pinfunction "1_1") (pintype "unspecified"))
      (node (ref "R62") (pin "2") (pinfunction "2_2") (pintype "unspecified"))
    )
    (net (code "613") (name "Net-(Q21-G)") (class "Default")
      (node (ref "Q21") (pin "1") (pinfunction "G_1") (pintype "unspecified"))
      (node (ref "R65") (pin "1") (pinfunction "1_1") (pintype "unspecified"))
    )
    (net (code "614") (name "Net-(Q23-G)") (class "Default")
      (node (ref "D48") (pin "2") (pinfunction "2_2") (pintype "unspecified"))
      (node (ref "Q23") (pin "1") (pinfunction "G_1") (pintype "unspecified"))
      (node (ref "R71") (pin "2") (pinfunction "2_2") (pintype "unspecified"))
      (node (ref "R72") (pin "2") (pinfunction "2_2") (pintype "unspecified"))
    )
    (net (code "615") (name "Net-(Q24-G)") (class "Default")
      (node (ref "Q24") (pin "1") (pinfunction "G_1") (pintype "unspecified"))
      (node (ref "R73") (pin "1") (pinfunction "1_1") (pintype "input"))
      (node (ref "R74") (pin "2") (pinfunction "2_2") (pintype "unspecified"))
    )
    (net (code "616") (name "Net-(U9-Q1)") (class "Default")
      (node (ref "R57") (pin "1") (pinfunction "1_1") (pintype "input"))
      (node (ref "U9") (pin "1") (pinfunction "Q1_1") (pintype "unspecified"))
    )
    (net (code "617") (name "Net-(U9-Q2)") (class "Default")
      (node (ref "R56") (pin "1") (pinfunction "1_1") (pintype "input"))
      (node (ref "U9") (pin "2") (pinfunction "Q2_2") (pintype "unspecified"))
    )
    (net (code "618") (name "Net-(U9-Q3)") (class "Default")
      (node (ref "R55") (pin "1") (pinfunction "1_1") (pintype "input"))
      (node (ref "U9") (pin "3") (pinfunction "Q3_3") (pintype "unspecified"))
    )
    (net (code "619") (name "Net-(U9-Q4)") (class "Default")
      (node (ref "R54") (pin "1") (pinfunction "1_1") (pintype "input"))
      (node (ref "U9") (pin "4") (pinfunction "Q4_4") (pintype "unspecified"))
    )
    (net (code "620") (name "Net-(U9-Q5)") (class "Default")
      (node (ref "R53") (pin "1") (pinfunction "1_1") (pintype "input"))
      (node (ref "U9") (pin "5") (pinfunction "Q5_5") (pintype "unspecified"))
    )
    (net (code "621") (name "Net-(U9-Q6)") (class "Default")
      (node (ref "R52") (pin "1") (pinfunction "1_1") (pintype "input"))
      (node (ref "U9") (pin "6") (pinfunction "Q6_6") (pintype "unspecified"))
    )
    (net (code "622") (name "Net-(U9-Q7)") (class "Default")
      (node (ref "R51") (pin "1") (pinfunction "1_1") (pintype "input"))
      (node (ref "U9") (pin "7") (pinfunction "Q7_7") (pintype "unspecified"))
    )
    (net (code "623") (name "Net-(U28-VOUT)") (class "Default")
      (node (ref "D42") (pin "1") (pinfunction "1_1") (pintype "unspecified"))
      (node (ref "L2") (pin "1") (pinfunction "1_1") (pintype "unspecified"))
      (node (ref "U28") (pin "2") (pinfunction "VOUT_2") (pintype "unspecified"))
    )
    (net (code "624") (name "Net-(U29-IN+)") (class "Default")
      (node (ref "R66") (pin "1") (pinfunction "1_1") (pintype "unspecified"))
      (node (ref "U29") (pin "10") (pinfunction "IN+_10") (pintype "unspecified"))
    )
    (net (code "625") (name "Net-(U29-IN-)") (class "Default")
      (node (ref "R67") (pin "1") (pinfunction "1_1") (pintype "unspecified"))
      (node (ref "U29") (pin "9") (pinfunction "IN-_9") (pintype "unspecified"))
    )
    (net (code "626") (name "Net-(U29-VS)") (class "Default")
      (node (ref "C16") (pin "2") (pinfunction "2_2") (pintype "unspecified"))
      (node (ref "U29") (pin "6") (pinfunction "VS_6") (pintype "unspecified"))
    )
    (net (code "627") (name "Net-(U31-A)") (class "Default")
      (node (ref "R65") (pin "2") (pinfunction "2_2") (pintype "unspecified"))
      (node (ref "U31") (pin "4") (pinfunction "A_4") (pintype "unspecified"))
    )
    (net (code "628") (name "Net-(U40-A)") (class "Default")
      (node (ref "C77") (pin "1") (pinfunction "1_1") (pintype "unspecified"))
      (node (ref "U40") (pin "4") (pinfunction "A_4") (pintype "unspecified"))
    )
    (net (code "629") (name "Net-(U41-A)") (class "Default")
      (node (ref "C78") (pin "1") (pinfunction "1_1") (pintype "unspecified"))
      (node (ref "U41") (pin "4") (pinfunction "A_4") (pintype "unspecified"))
    )
    (net (code "630") (name "Net-(U52-REF)") (class "Default")
      (node (ref "C105") (pin "1") (pinfunction "1_1") (pintype "unspecified"))
      (node (ref "U52") (pin "6") (pinfunction "REF_6") (pintype "unspecified"))
    )
    (net (code "631") (name "Net-(U54-+IN)") (class "Default")
      (node (ref "C108") (pin "2") (pinfunction "2_2") (pintype "unspecified"))
      (node (ref "R95") (pin "2") (pinfunction "2_2") (pintype "unspecified"))
      (node (ref "U54") (pin "3") (pinfunction "+IN_3") (pintype "unspecified"))
    )
    (net (code "632") (name "Net-(U54--IN)") (class "Default")
      (node (ref "C107") (pin "1") (pinfunction "1_1") (pintype "unspecified"))
      (node (ref "R94") (pin "2") (pinfunction "2_2") (pintype "unspecified"))
      (node (ref "U54") (pin "2") (pinfunction "-IN_2") (pintype "unspecified"))
    )
    (net (code "633") (name "Net-(U54-REF)") (class "Default")
      (node (ref "R96") (pin "1") (pinfunction "1_1") (pintype "unspecified"))
      (node (ref "U54") (pin "1") (pinfunction "REF_1") (pintype "unspecified"))
    )
    (net (code "634") (name "Net-(U54-SENSE)") (class "Default")
      (node (ref "R97") (pin "2") (pinfunction "2_2") (pintype "unspecified"))
      (node (ref "U54") (pin "5") (pinfunction "SENSE_5") (pintype "unspecified"))
    )
    (net (code "635") (name "unconnected-(H4-Pad58)") (class "Default")
      (node (ref "H4") (pin "58") (pinfunction "58_58") (pintype "unspecified"))
    )
    (net (code "636") (name "unconnected-(H4-Pad60)") (class "Default")
      (node (ref "H4") (pin "60") (pinfunction "60_60") (pintype "unspecified"))
    )
    (net (code "637") (name "unconnected-(H4-Pad62)") (class "Default")
      (node (ref "H4") (pin "62") (pinfunction "62_62") (pintype "unspecified"))
    )
    (net (code "638") (name "unconnected-(H4-Pad64)") (class "Default")
      (node (ref "H4") (pin "64") (pinfunction "64_64") (pintype "unspecified"))
    )
    (net (code "639") (name "unconnected-(H5-Pad2)") (class "Default")
      (node (ref "H5") (pin "2") (pinfunction "2_2") (pintype "unspecified"))
    )
    (net (code "640") (name "unconnected-(H5-Pad4)") (class "Default")
      (node (ref "H5") (pin "4") (pinfunction "4_4") (pintype "unspecified"))
    )
    (net (code "641") (name "unconnected-(H5-Pad6)") (class "Default")
      (node (ref "H5") (pin "6") (pinfunction "6_6") (pintype "unspecified"))
    )
    (net (code "642") (name "unconnected-(H5-Pad8)") (class "Default")
      (node (ref "H5") (pin "8") (pinfunction "8_8") (pintype "unspecified"))
    )
    (net (code "643") (name "unconnected-(H5-Pad10)") (class "Default")
      (node (ref "H5") (pin "10") (pinfunction "10_10") (pintype "unspecified"))
    )
    (net (code "644") (name "unconnected-(H5-Pad12)") (class "Default")
      (node (ref "H5") (pin "12") (pinfunction "12_12") (pintype "unspecified"))
    )
    (net (code "645") (name "unconnected-(H5-Pad14)") (class "Default")
      (node (ref "H5") (pin "14") (pinfunction "14_14") (pintype "unspecified"))
    )
    (net (code "646") (name "unconnected-(H5-Pad16)") (class "Default")
      (node (ref "H5") (pin "16") (pinfunction "16_16") (pintype "unspecified"))
    )
    (net (code "647") (name "unconnected-(H5-Pad18)") (class "Default")
      (node (ref "H5") (pin "18") (pinfunction "18_18") (pintype "unspecified"))
    )
    (net (code "648") (name "unconnected-(H5-Pad20)") (class "Default")
      (node (ref "H5") (pin "20") (pinfunction "20_20") (pintype "unspecified"))
    )
    (net (code "649") (name "unconnected-(H5-Pad22)") (class "Default")
      (node (ref "H5") (pin "22") (pinfunction "22_22") (pintype "unspecified"))
    )
    (net (code "650") (name "unconnected-(H5-Pad24)") (class "Default")
      (node (ref "H5") (pin "24") (pinfunction "24_24") (pintype "unspecified"))
    )
    (net (code "651") (name "unconnected-(H5-Pad26)") (class "Default")
      (node (ref "H5") (pin "26") (pinfunction "26_26") (pintype "unspecified"))
    )
    (net (code "652") (name "unconnected-(H5-Pad28)") (class "Default")
      (node (ref "H5") (pin "28") (pinfunction "28_28") (pintype "unspecified"))
    )
    (net (code "653") (name "unconnected-(H5-Pad30)") (class "Default")
      (node (ref "H5") (pin "30") (pinfunction "30_30") (pintype "unspecified"))
    )
    (net (code "654") (name "unconnected-(H5-Pad32)") (class "Default")
      (node (ref "H5") (pin "32") (pinfunction "32_32") (pintype "unspecified"))
    )
    (net (code "655") (name "unconnected-(U7-AIN9-Pad11)") (class "Default")
      (node (ref "U7") (pin "11") (pinfunction "AIN9_11") (pintype "unspecified+no_connect"))
    )
    (net (code "656") (name "unconnected-(U7-AIN10-Pad12)") (class "Default")
      (node (ref "U7") (pin "12") (pinfunction "AIN10_12") (pintype "unspecified+no_connect"))
    )
    (net (code "657") (name "unconnected-(U9-Q0-Pad15)") (class "Default")
      (node (ref "U9") (pin "15") (pinfunction "Q0_15") (pintype "unspecified+no_connect"))
    )
    (net (code "658") (name "unconnected-(U9-Q7S-Pad9)") (class "Default")
      (node (ref "U9") (pin "9") (pinfunction "Q7S_9") (pintype "unspecified+no_connect"))
    )
    (net (code "659") (name "unconnected-(U32-NC-Pad7)") (class "Default")
      (node (ref "U32") (pin "7") (pinfunction "NC_7") (pintype "unspecified+no_connect"))
    )
    (net (code "660") (name "unconnected-(U33-NC-Pad7)") (class "Default")
      (node (ref "U33") (pin "7") (pinfunction "NC_7") (pintype "unspecified+no_connect"))
    )
    (net (code "661") (name "unconnected-(U34-NC-Pad7)") (class "Default")
      (node (ref "U34") (pin "7") (pinfunction "NC_7") (pintype "unspecified+no_connect"))
    )
    (net (code "662") (name "unconnected-(U35-NC-Pad7)") (class "Default")
      (node (ref "U35") (pin "7") (pinfunction "NC_7") (pintype "unspecified+no_connect"))
    )
    (net (code "663") (name "unconnected-(U36-NC-Pad7)") (class "Default")
      (node (ref "U36") (pin "7") (pinfunction "NC_7") (pintype "unspecified+no_connect"))
    )
    (net (code "664") (name "unconnected-(U37-NC-Pad7)") (class "Default")
      (node (ref "U37") (pin "7") (pinfunction "NC_7") (pintype "unspecified+no_connect"))
    )
    (net (code "665") (name "unconnected-(U38-NC-Pad7)") (class "Default")
      (node (ref "U38") (pin "7") (pinfunction "NC_7") (pintype "unspecified+no_connect"))
    )
    (net (code "666") (name "unconnected-(U42-NC-Pad7)") (class "Default")
      (node (ref "U42") (pin "7") (pinfunction "NC_7") (pintype "unspecified+no_connect"))
    )
    (net (code "667") (name "unconnected-(U43-NC-Pad7)") (class "Default")
      (node (ref "U43") (pin "7") (pinfunction "NC_7") (pintype "unspecified+no_connect"))
    )
    (net (code "668") (name "unconnected-(U44-NC-Pad7)") (class "Default")
      (node (ref "U44") (pin "7") (pinfunction "NC_7") (pintype "unspecified+no_connect"))
    )
    (net (code "669") (name "unconnected-(U45-NC-Pad7)") (class "Default")
      (node (ref "U45") (pin "7") (pinfunction "NC_7") (pintype "unspecified+no_connect"))
    )
    (net (code "670") (name "unconnected-(U46-NC-Pad7)") (class "Default")
      (node (ref "U46") (pin "7") (pinfunction "NC_7") (pintype "unspecified+no_connect"))
    )
    (net (code "671") (name "unconnected-(U47-NC-Pad7)") (class "Default")
      (node (ref "U47") (pin "7") (pinfunction "NC_7") (pintype "unspecified+no_connect"))
    )
    (net (code "672") (name "unconnected-(U48-NC-Pad7)") (class "Default")
      (node (ref "U48") (pin "7") (pinfunction "NC_7") (pintype "unspecified+no_connect"))
    )
    (net (code "673") (name "unconnected-(U49-NC-Pad2)") (class "Default")
      (node (ref "U49") (pin "2") (pinfunction "NC_2") (pintype "unspecified+no_connect"))
    )
    (net (code "674") (name "unconnected-(U49-NC-Pad3)") (class "Default")
      (node (ref "U49") (pin "3") (pinfunction "NC_3") (pintype "unspecified+no_connect"))
    )
    (net (code "675") (name "unconnected-(U49-NC-Pad13)") (class "Default")
      (node (ref "U49") (pin "13") (pinfunction "NC_13") (pintype "unspecified+no_connect"))
    )
    (net (code "676") (name "unconnected-(U50-NC-Pad12)") (class "Default")
      (node (ref "U50") (pin "12") (pinfunction "NC_12") (pintype "unspecified+no_connect"))
    )
    (net (code "677") (name "unconnected-(U50-NC-Pad13)") (class "Default")
      (node (ref "U50") (pin "13") (pinfunction "NC_13") (pintype "unspecified+no_connect"))
    )
    (net (code "678") (name "unconnected-(U50-NC-Pad26)") (class "Default")
      (node (ref "U50") (pin "26") (pinfunction "NC_26") (pintype "unspecified+no_connect"))
    )
    (net (code "679") (name "unconnected-(U50-NC-Pad27)") (class "Default")
      (node (ref "U50") (pin "27") (pinfunction "NC_27") (pintype "unspecified+no_connect"))
    )
    (net (code "680") (name "unconnected-(U50-NC-Pad28)") (class "Default")
      (node (ref "U50") (pin "28") (pinfunction "NC_28") (pintype "unspecified+no_connect"))
    )
    (net (code "681") (name "unconnected-(U50-NC-Pad30)") (class "Default")
      (node (ref "U50") (pin "30") (pinfunction "NC_30") (pintype "unspecified+no_connect"))
    )
    (net (code "682") (name "unconnected-(U50-NC-Pad32)") (class "Default")
      (node (ref "U50") (pin "32") (pinfunction "NC_32") (pintype "unspecified+no_connect"))
    )
    (net (code "683") (name "unconnected-(U51-NC-Pad12)") (class "Default")
      (node (ref "U51") (pin "12") (pinfunction "NC_12") (pintype "unspecified+no_connect"))
    )
    (net (code "684") (name "unconnected-(U51-NC-Pad13)") (class "Default")
      (node (ref "U51") (pin "13") (pinfunction "NC_13") (pintype "unspecified+no_connect"))
    )
    (net (code "685") (name "unconnected-(U51-NC-Pad26)") (class "Default")
      (node (ref "U51") (pin "26") (pinfunction "NC_26") (pintype "unspecified+no_connect"))
    )
    (net (code "686") (name "unconnected-(U51-NC-Pad27)") (class "Default")
      (node (ref "U51") (pin "27") (pinfunction "NC_27") (pintype "unspecified+no_connect"))
    )
    (net (code "687") (name "unconnected-(U51-NC-Pad28)") (class "Default")
      (node (ref "U51") (pin "28") (pinfunction "NC_28") (pintype "unspecified+no_connect"))
    )
    (net (code "688") (name "unconnected-(U51-NC-Pad30)") (class "Default")
      (node (ref "U51") (pin "30") (pinfunction "NC_30") (pintype "unspecified+no_connect"))
    )
    (net (code "689") (name "unconnected-(U51-NC-Pad32)") (class "Default")
      (node (ref "U51") (pin "32") (pinfunction "NC_32") (pintype "unspecified+no_connect"))
    )
    (net (code "690") (name "unconnected-(U53-NC-Pad2)") (class "Default")
      (node (ref "U53") (pin "2") (pinfunction "NC_2") (pintype "unspecified+no_connect"))
    )
    (net (code "691") (name "unconnected-(U53-NC-Pad3)") (class "Default")
      (node (ref "U53") (pin "3") (pinfunction "NC_3") (pintype "unspecified+no_connect"))
    )
    (net (code "692") (name "unconnected-(U53-NC-Pad13)") (class "Default")
      (node (ref "U53") (pin "13") (pinfunction "NC_13") (pintype "unspecified+no_connect"))
    )
    (net (code "693") (name "unconnected-(U54-NC-Pad8)") (class "Default")
      (node (ref "U54") (pin "8") (pinfunction "NC_8") (pintype "unspecified+no_connect"))
    )
    (net (code "694") (name "unconnected-(U55-NC-Pad12)") (class "Default")
      (node (ref "U55") (pin "12") (pinfunction "NC_12") (pintype "unspecified+no_connect"))
    )
    (net (code "695") (name "unconnected-(U55-NC-Pad13)") (class "Default")
      (node (ref "U55") (pin "13") (pinfunction "NC_13") (pintype "unspecified+no_connect"))
    )
    (net (code "696") (name "unconnected-(U55-NC-Pad26)") (class "Default")
      (node (ref "U55") (pin "26") (pinfunction "NC_26") (pintype "unspecified+no_connect"))
    )
    (net (code "697") (name "unconnected-(U55-NC-Pad27)") (class "Default")
      (node (ref "U55") (pin "27") (pinfunction "NC_27") (pintype "unspecified+no_connect"))
    )
    (net (code "698") (name "unconnected-(U55-NC-Pad28)") (class "Default")
      (node (ref "U55") (pin "28") (pinfunction "NC_28") (pintype "unspecified+no_connect"))
    )
    (net (code "699") (name "unconnected-(U55-NC-Pad30)") (class "Default")
      (node (ref "U55") (pin "30") (pinfunction "NC_30") (pintype "unspecified+no_connect"))
    )
    (net (code "700") (name "unconnected-(U55-NC-Pad32)") (class "Default")
      (node (ref "U55") (pin "32") (pinfunction "NC_32") (pintype "unspecified+no_connect"))
    )
  )
)
